# IoT4Bees-Ctrl_1V0.net
KiCad netlist of a schematic drawn in EAGLE
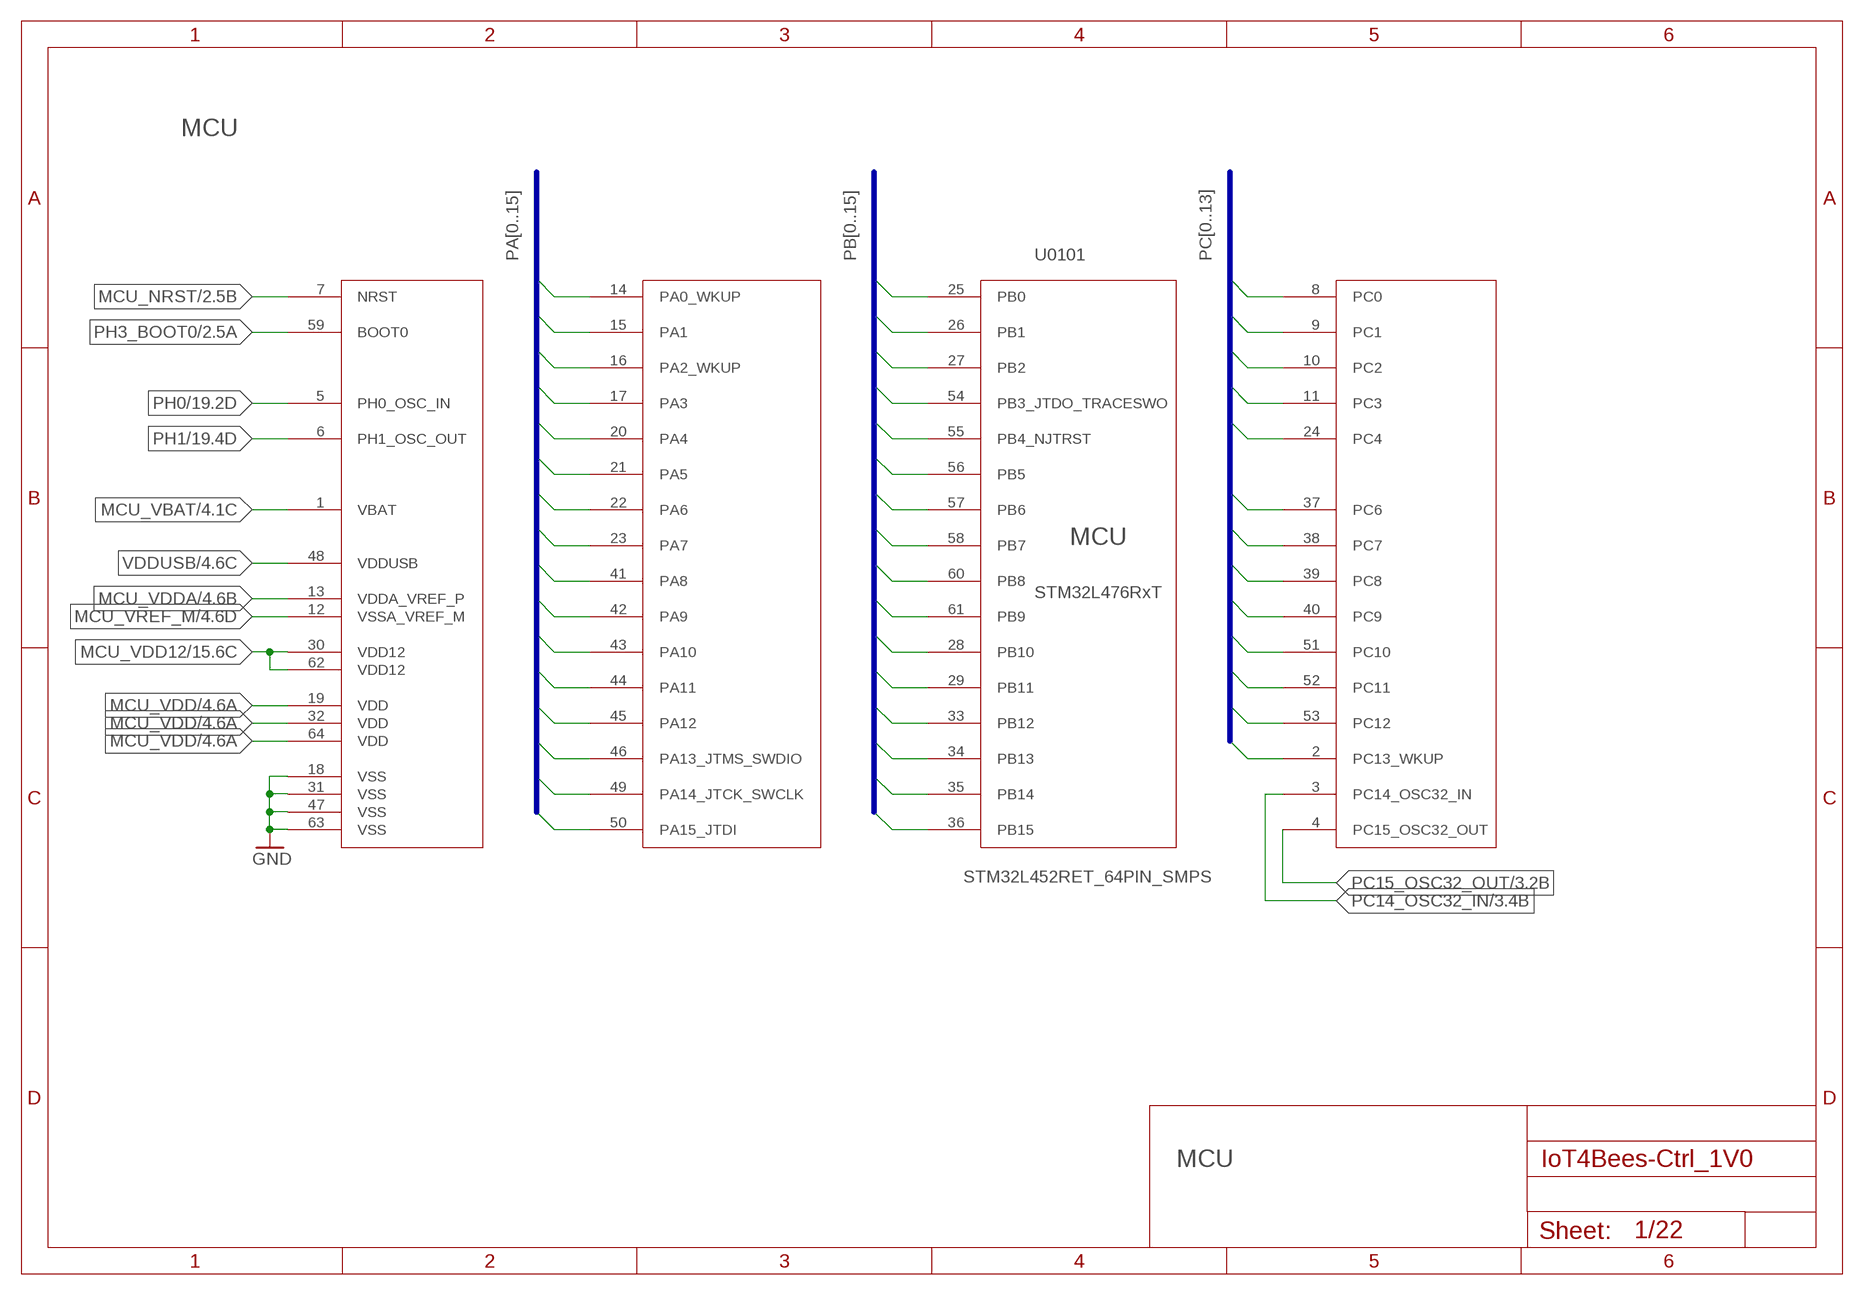
[diagram p0: schematic, sheet 1]
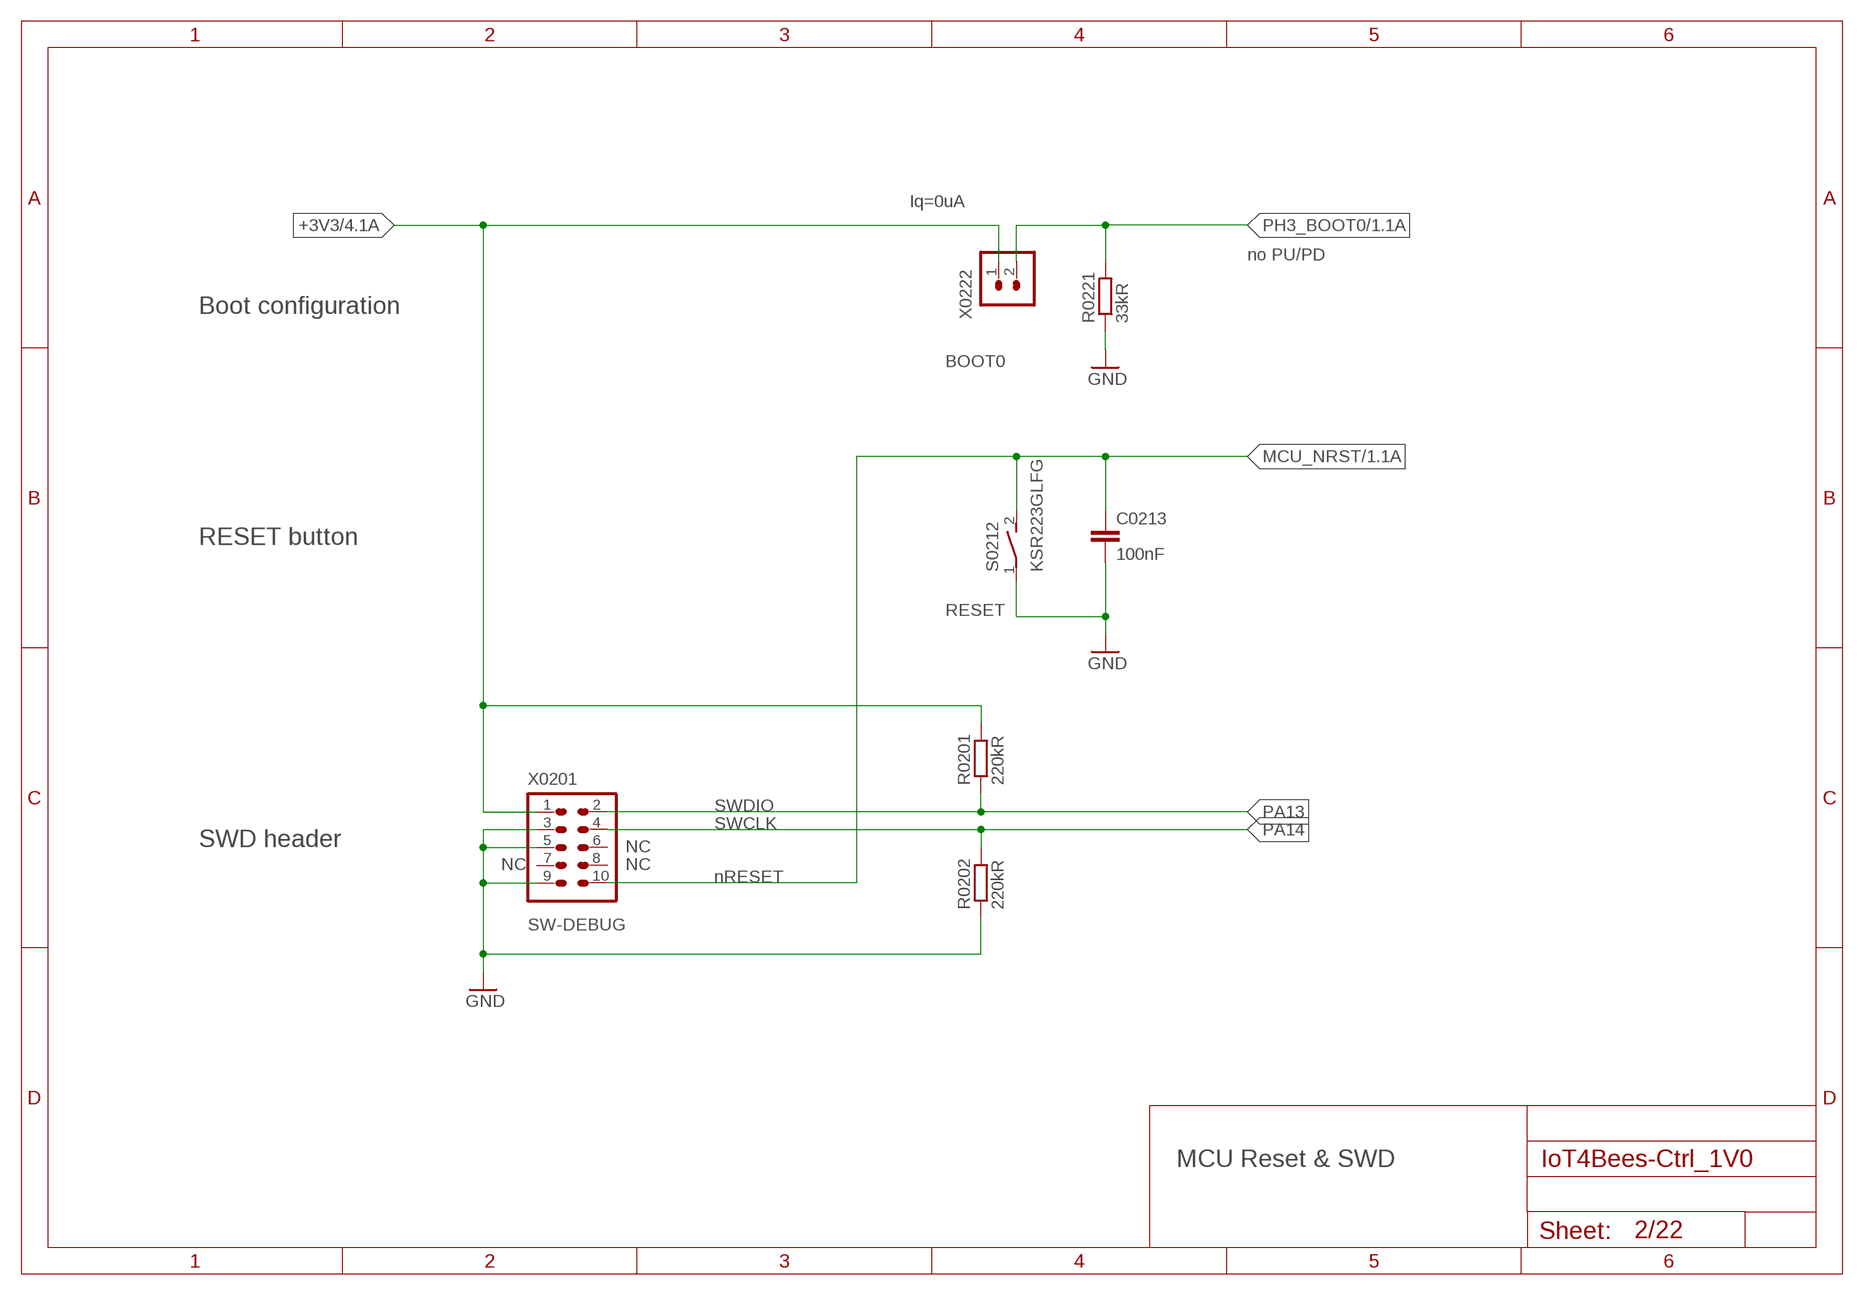
[diagram p1: schematic, sheet 2]
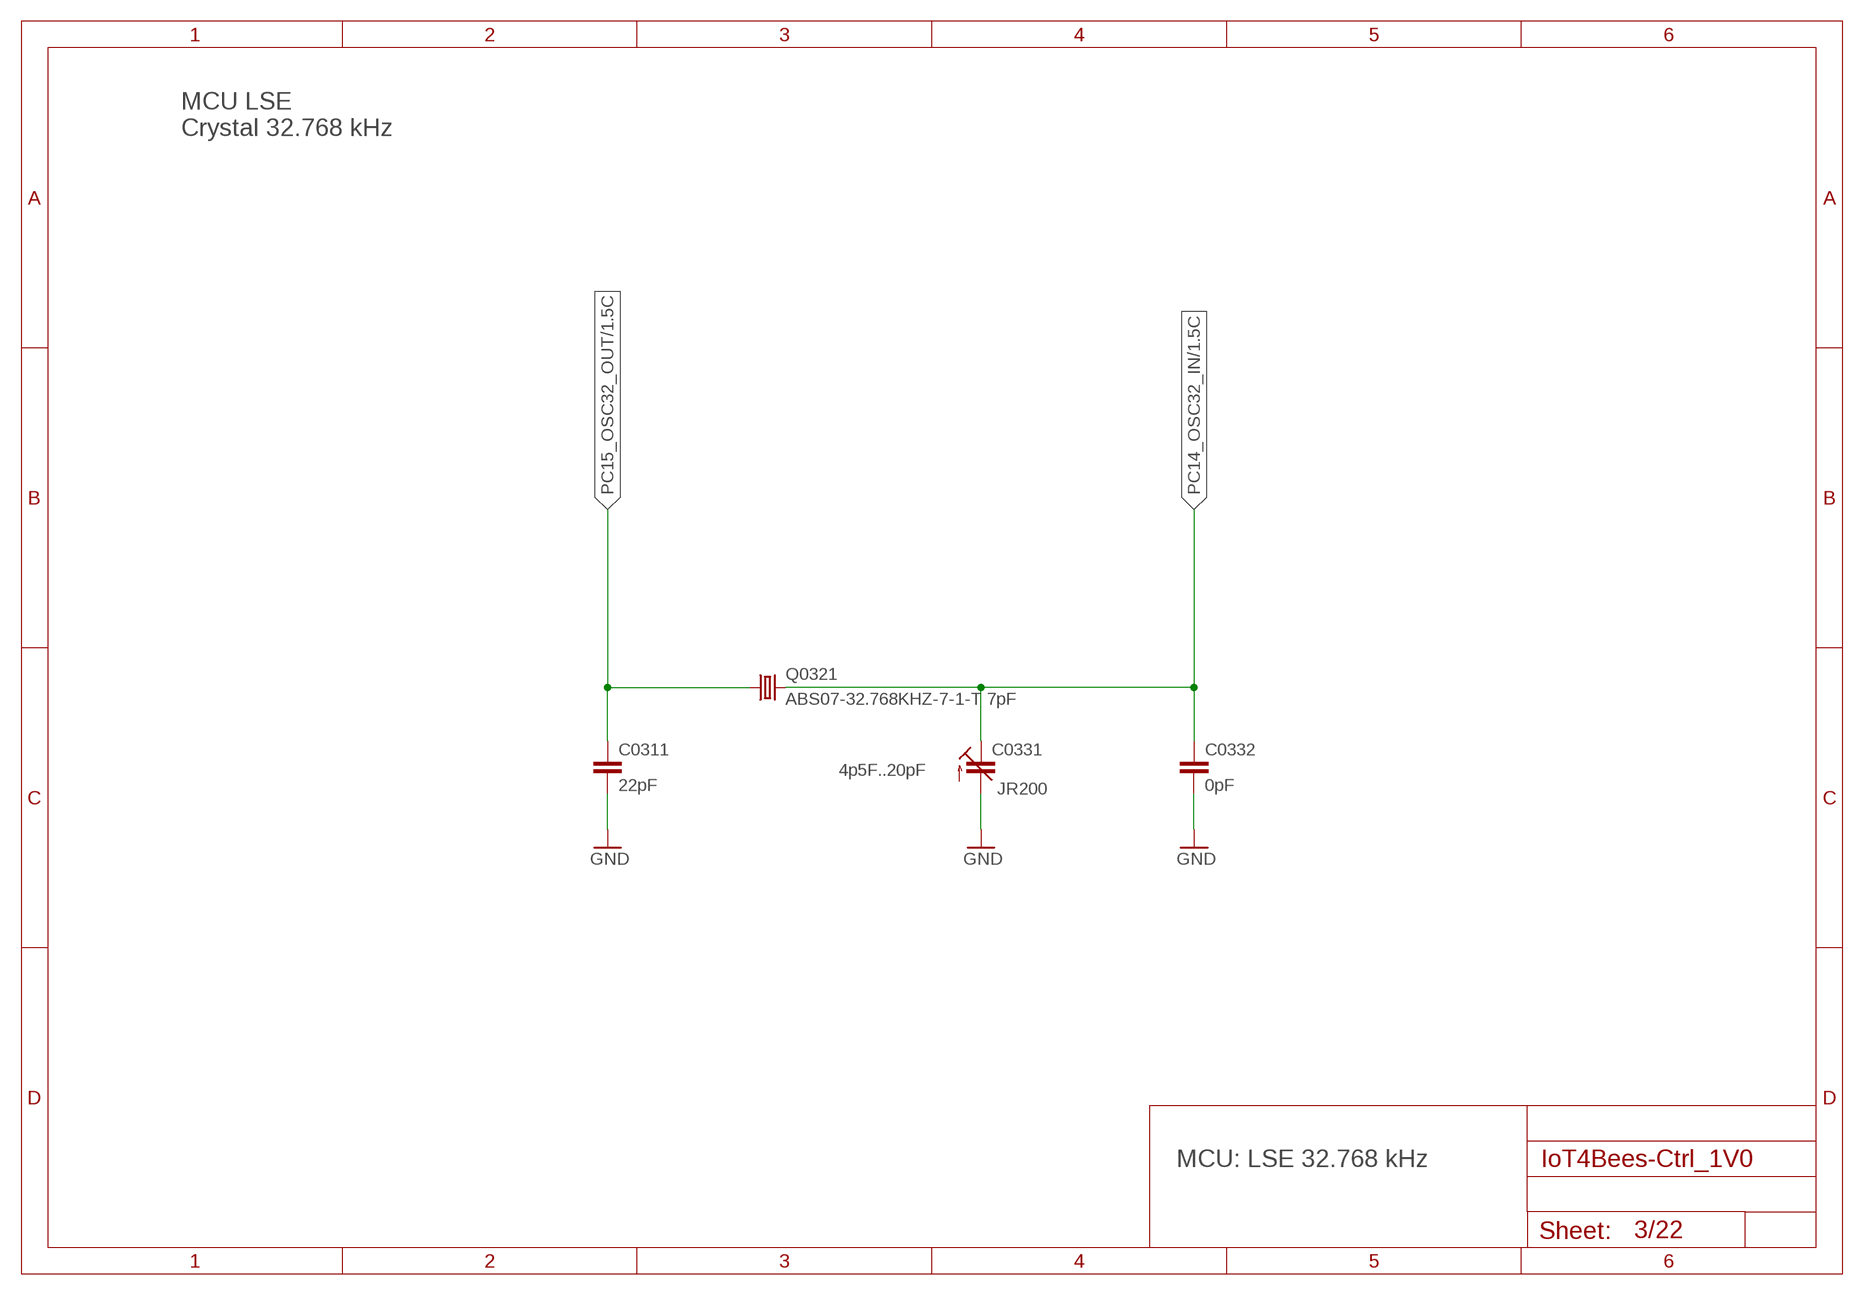
[diagram p2: schematic, sheet 3]
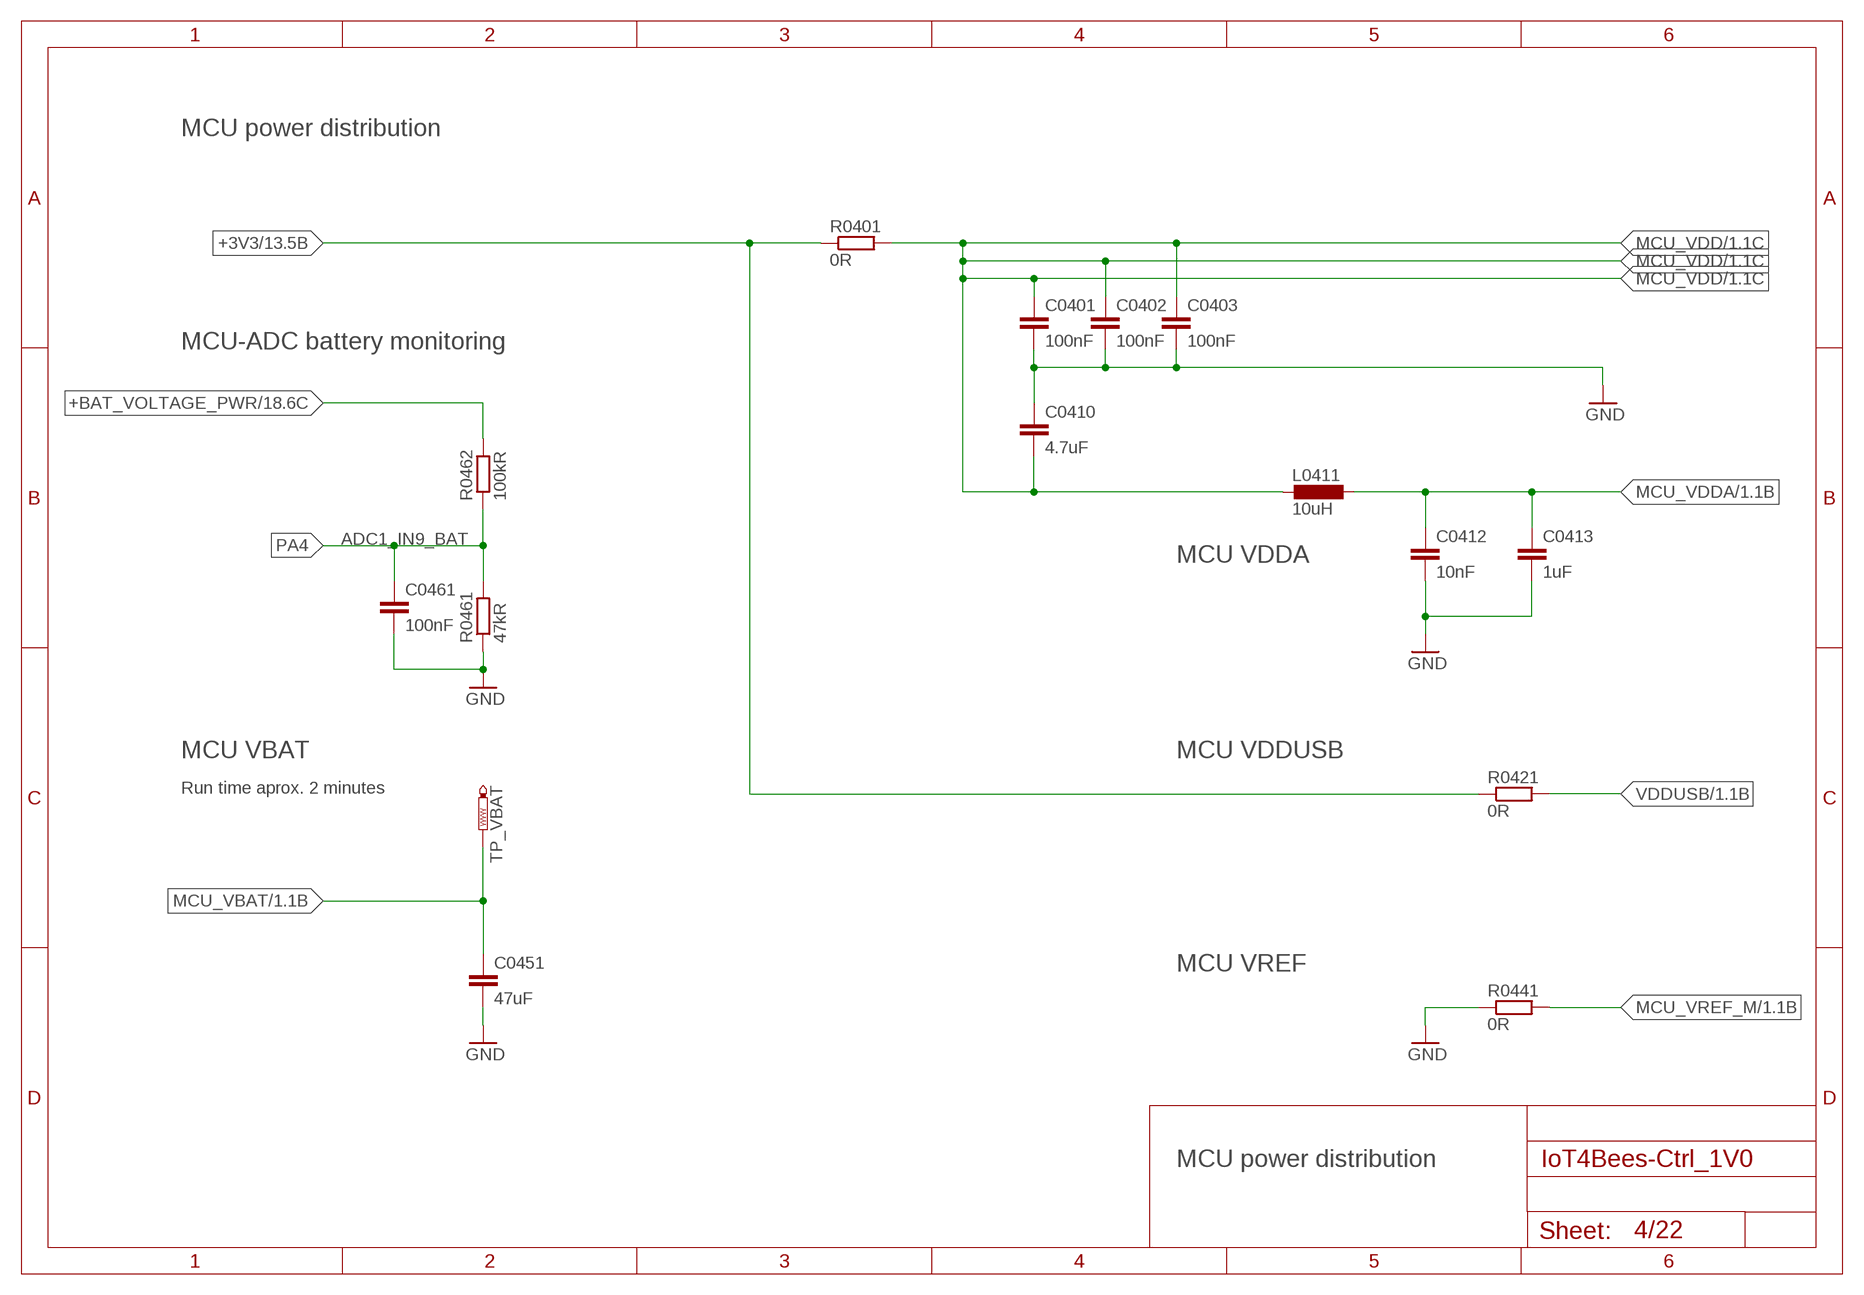
[diagram p3: schematic, sheet 4]
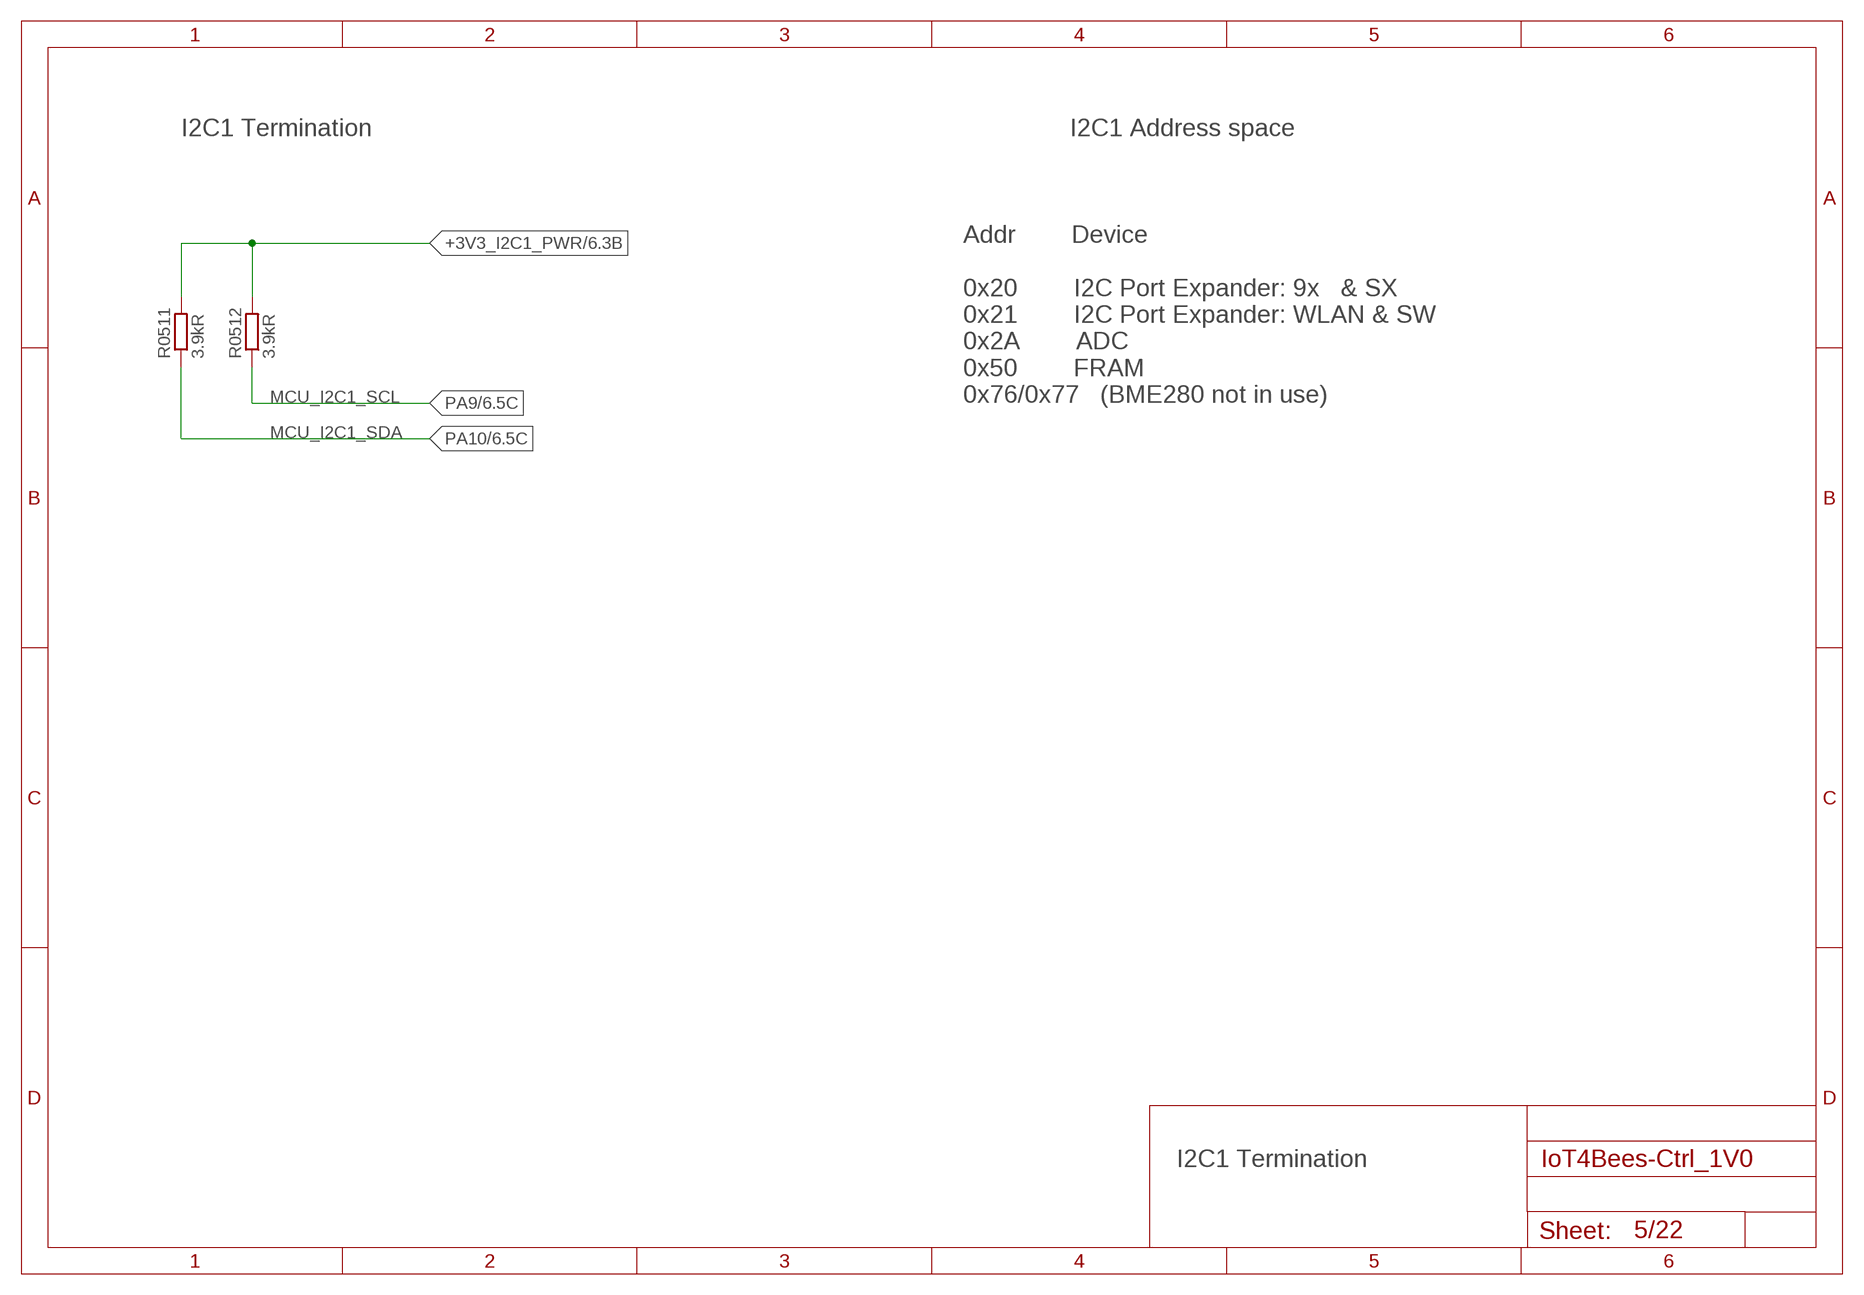
[diagram p4: schematic, sheet 5]
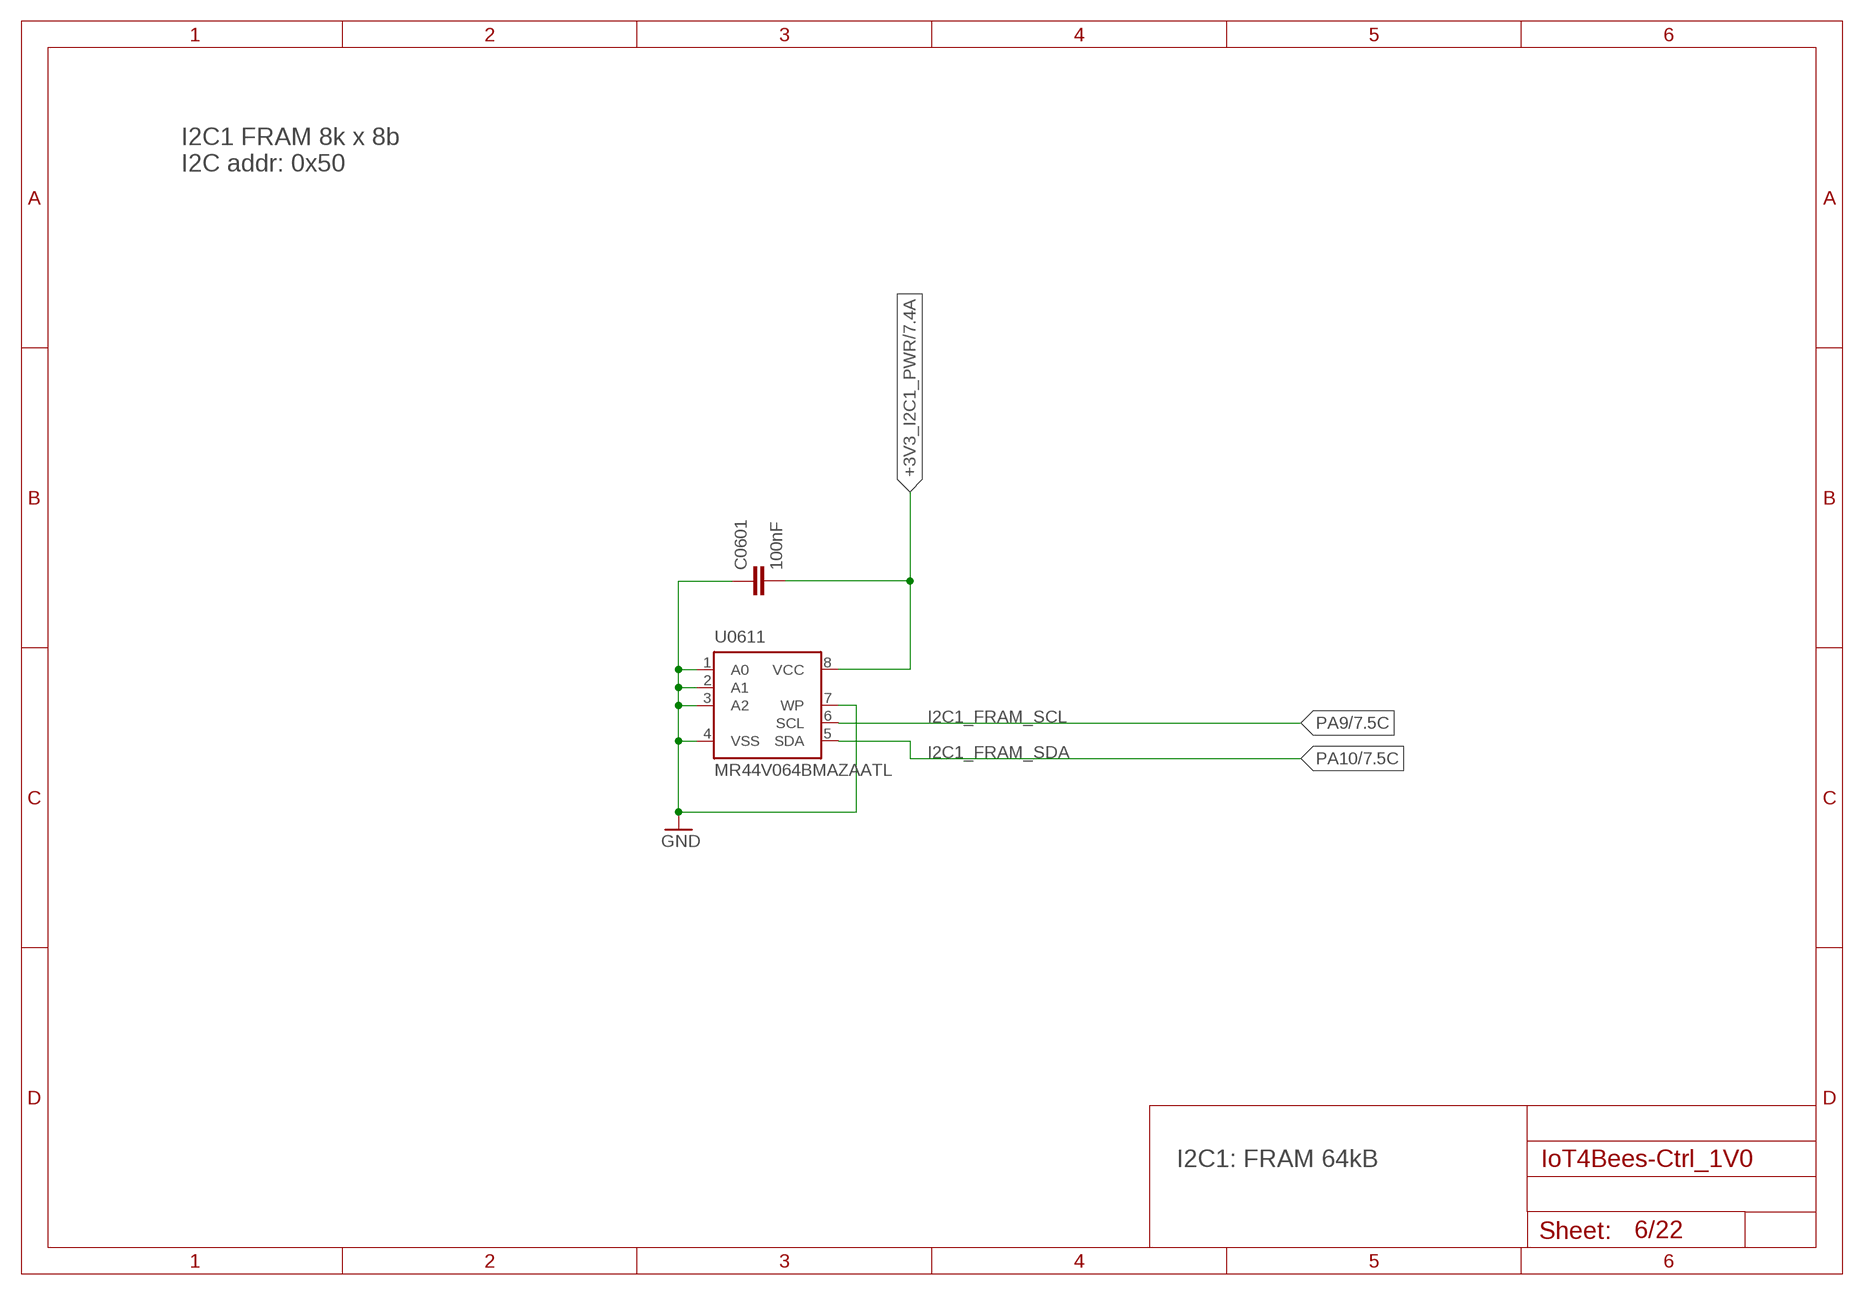
[diagram p5: schematic, sheet 6]
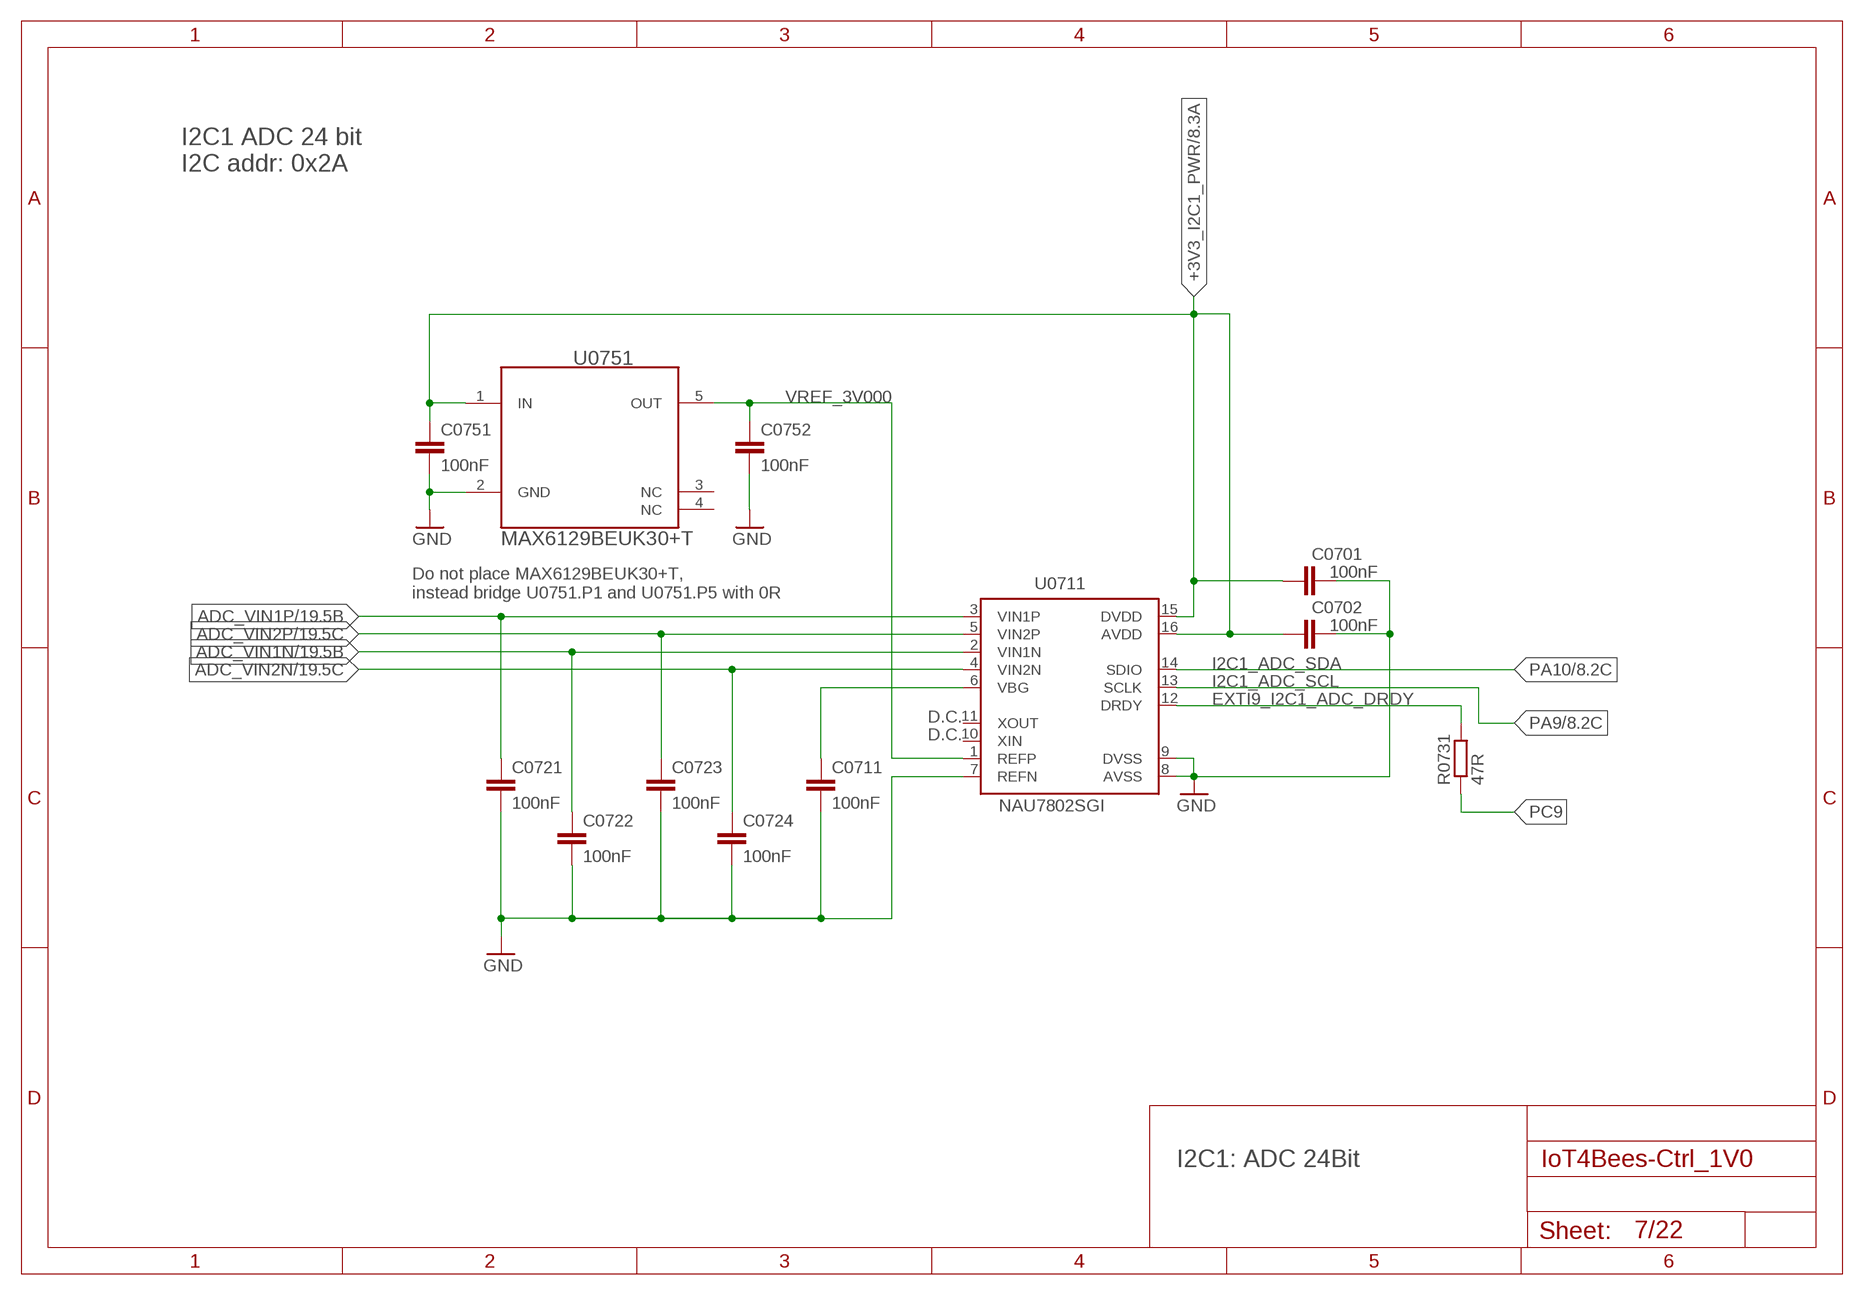
[diagram p6: schematic, sheet 7]
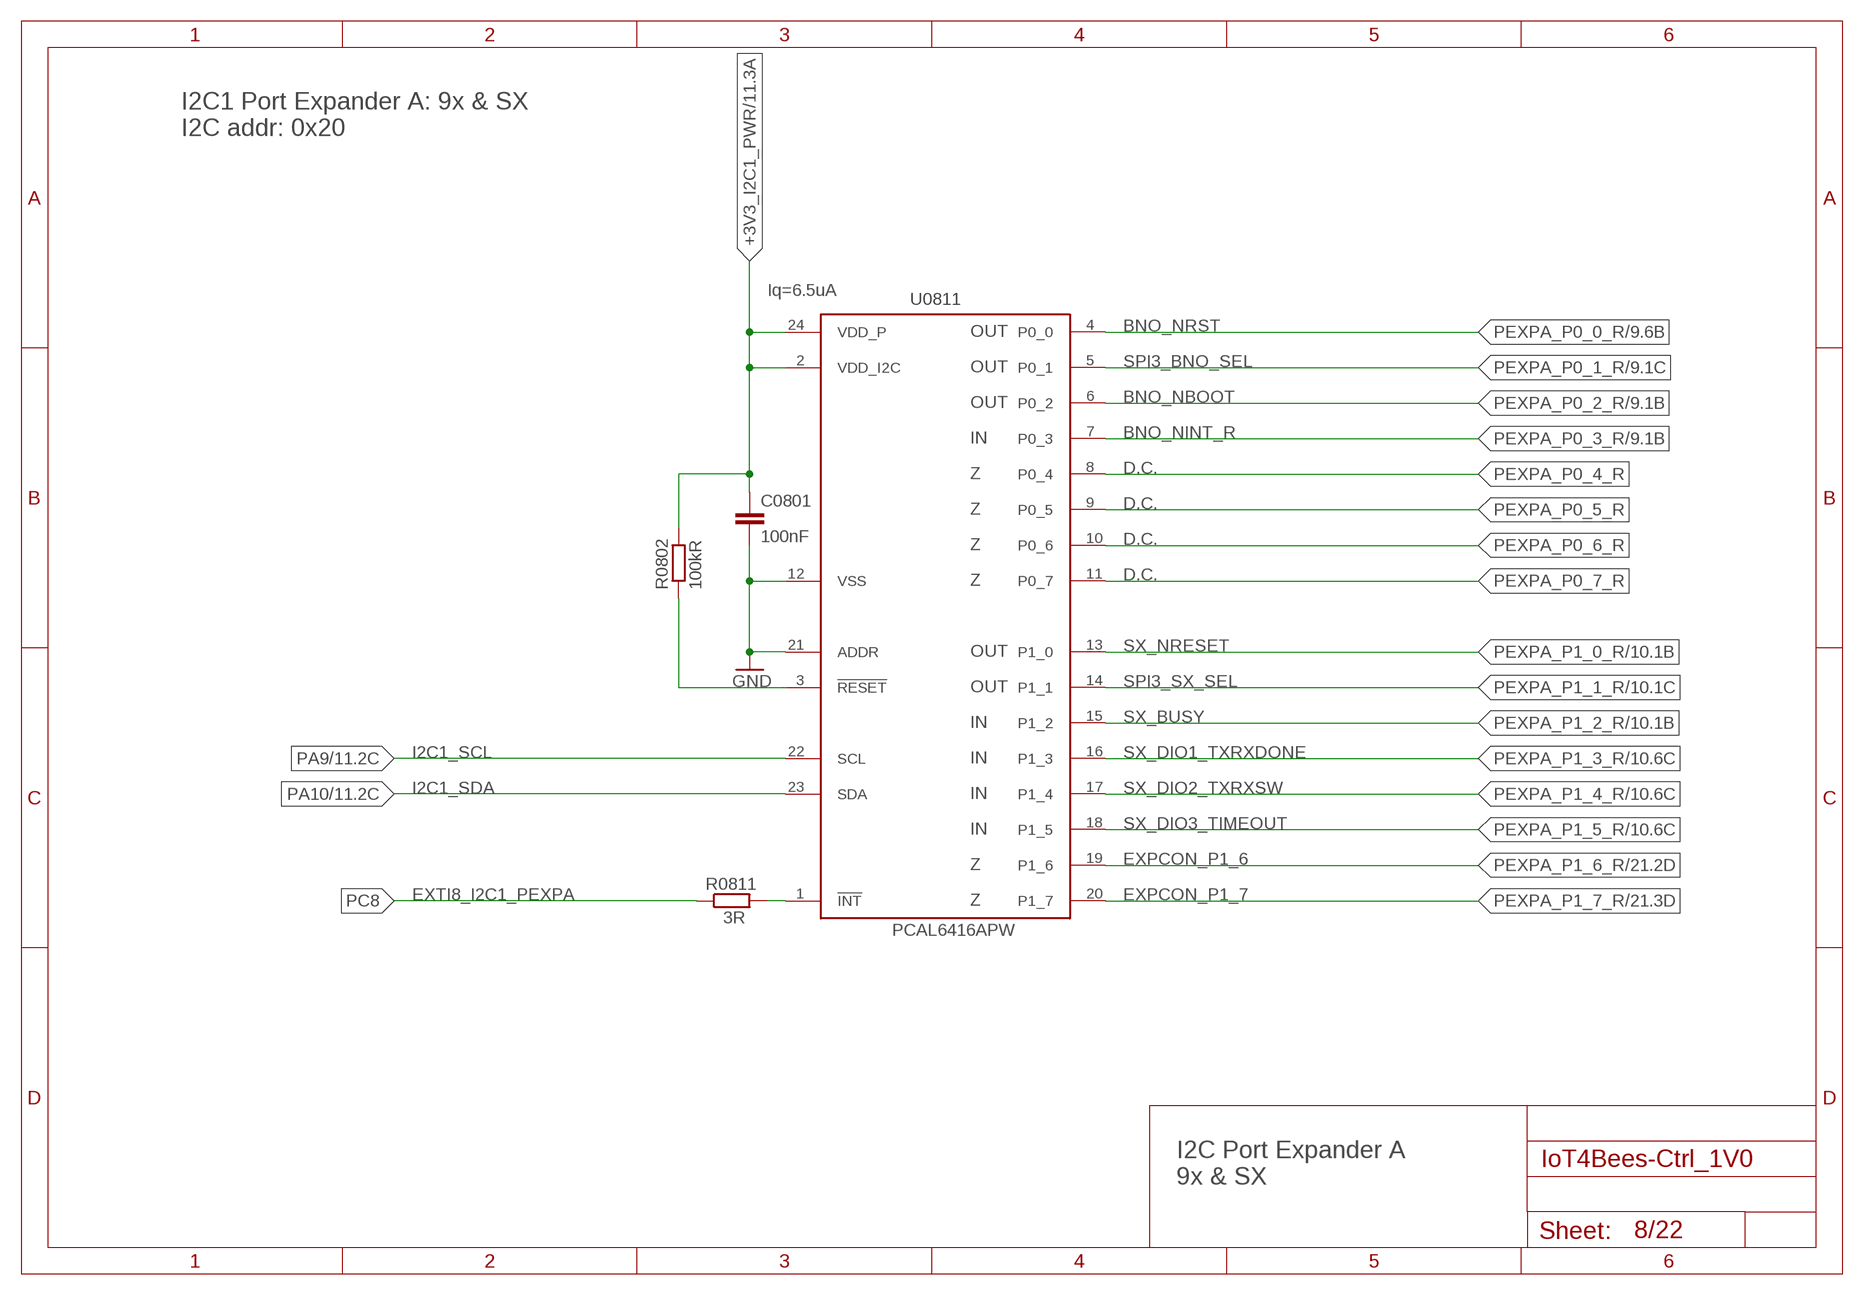
[diagram p7: schematic, sheet 8]
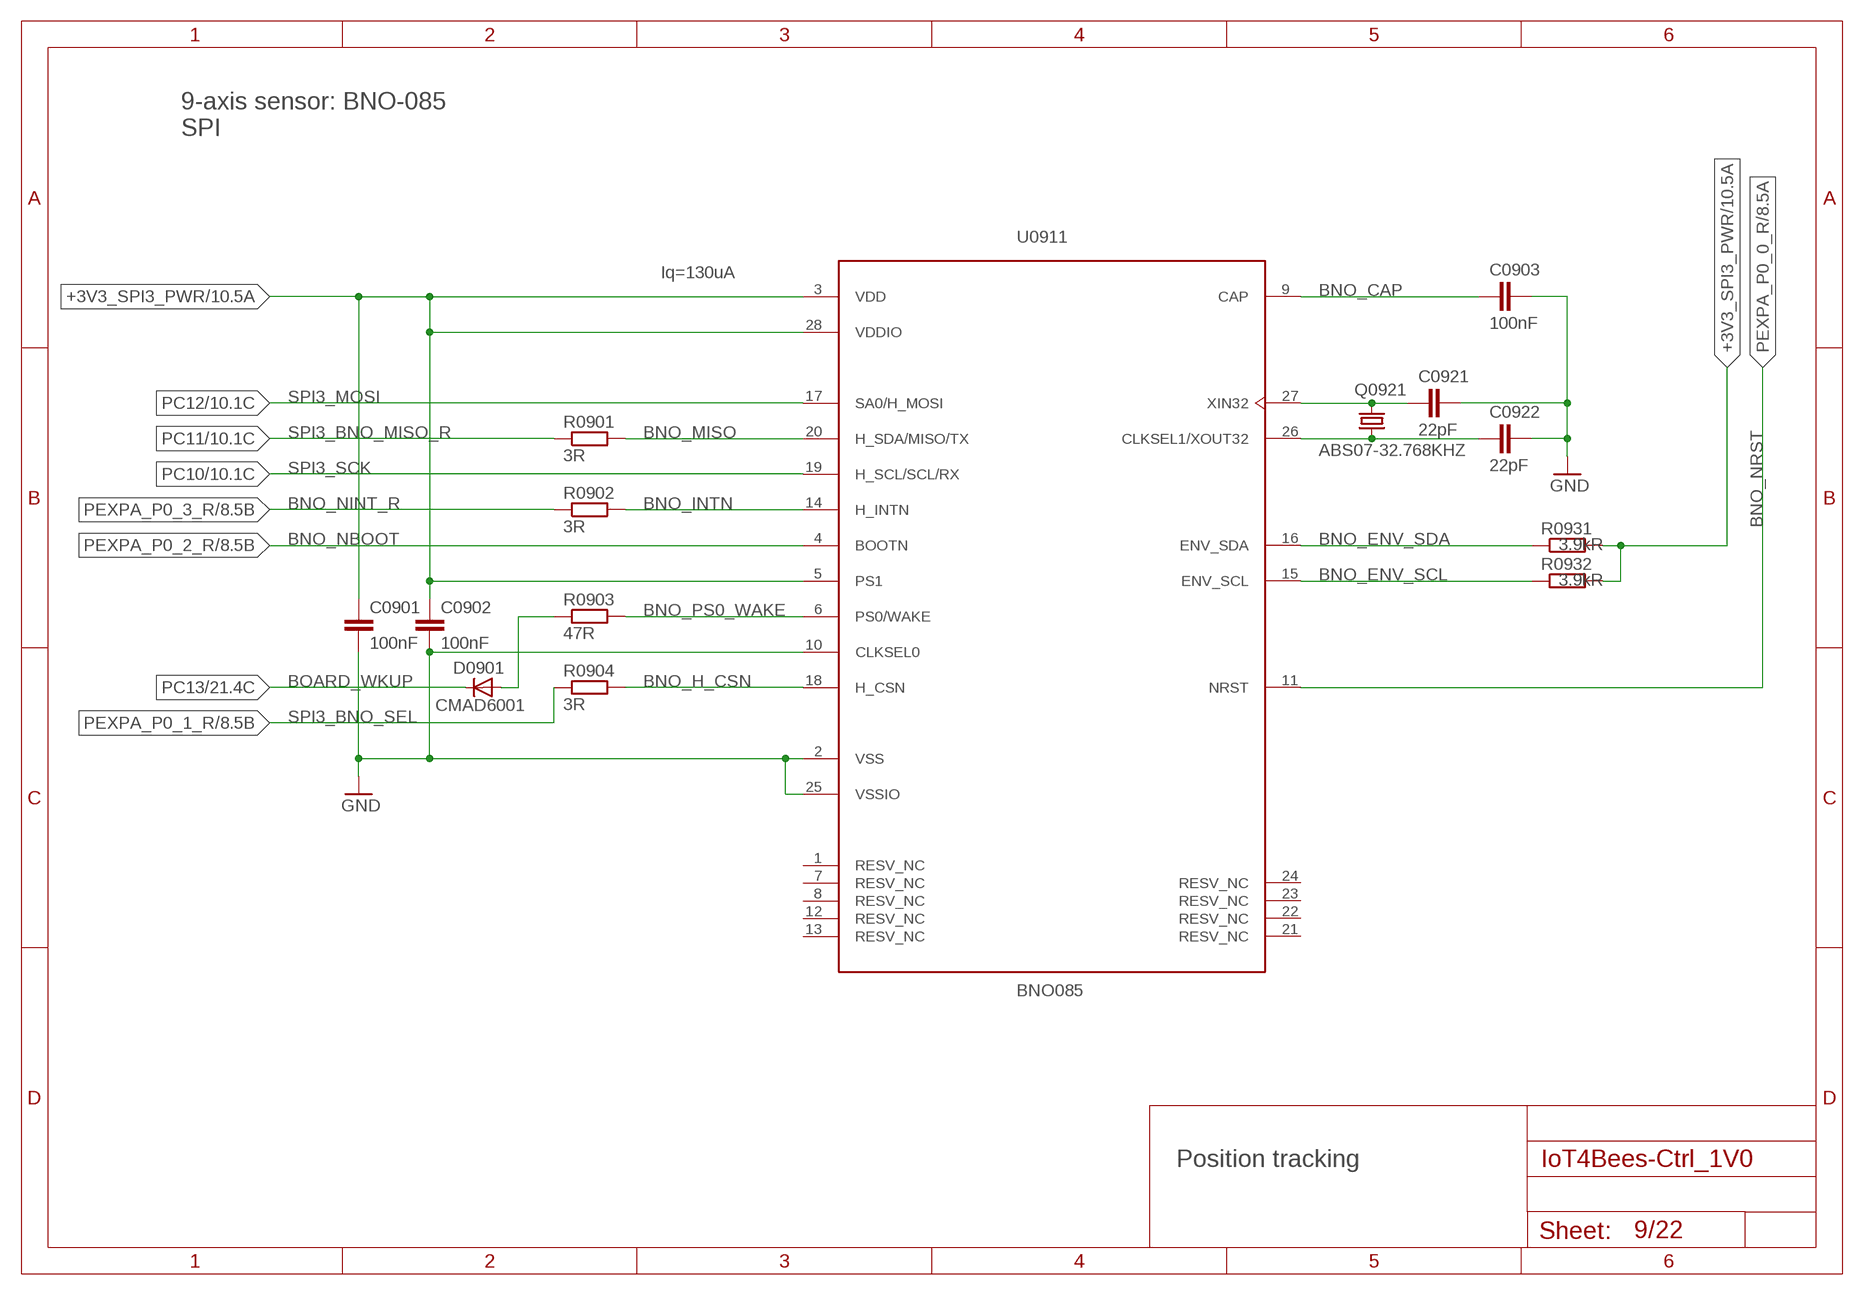
[diagram p8: schematic, sheet 9]
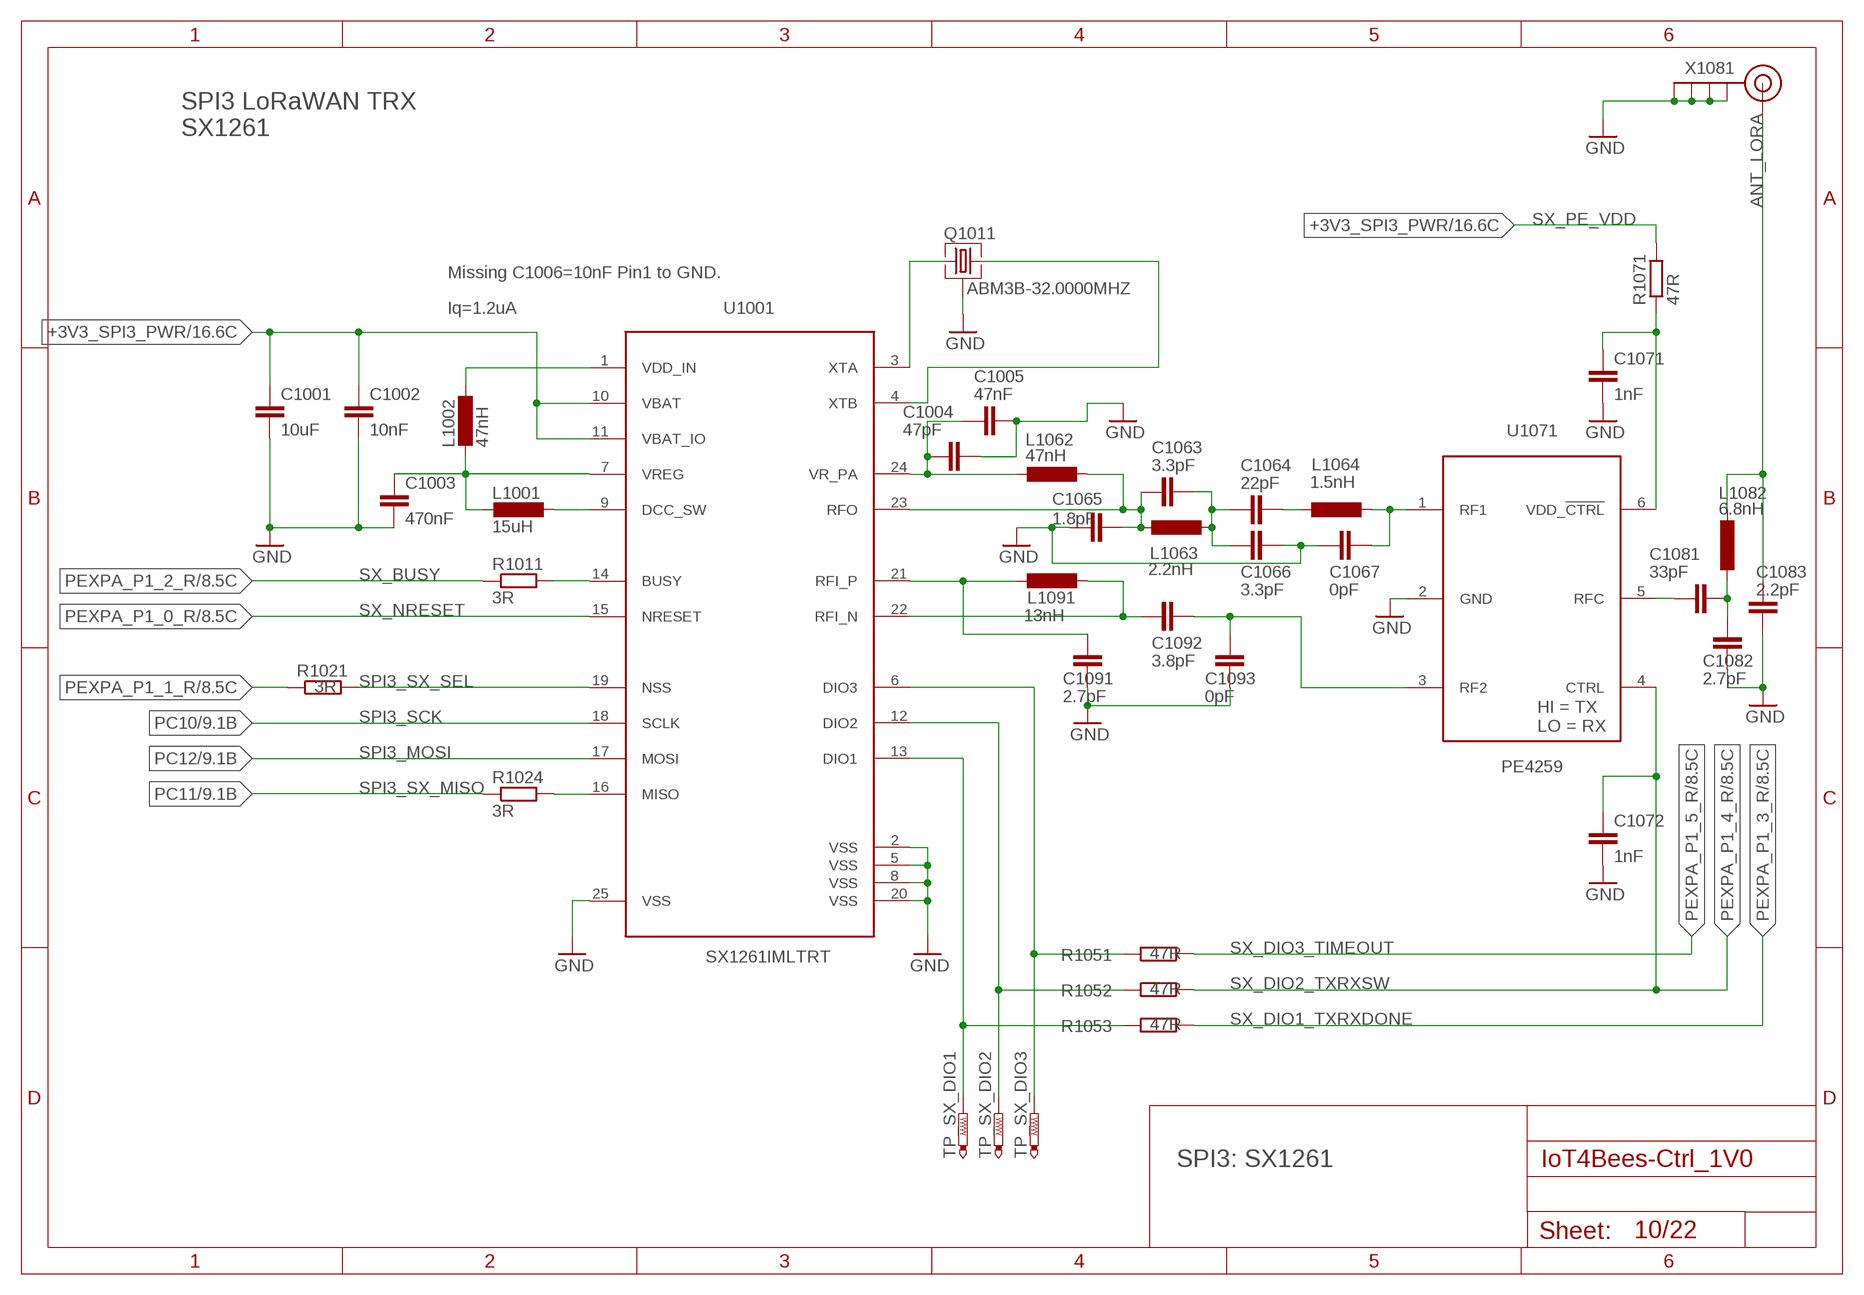
[diagram p9: schematic, sheet 10]
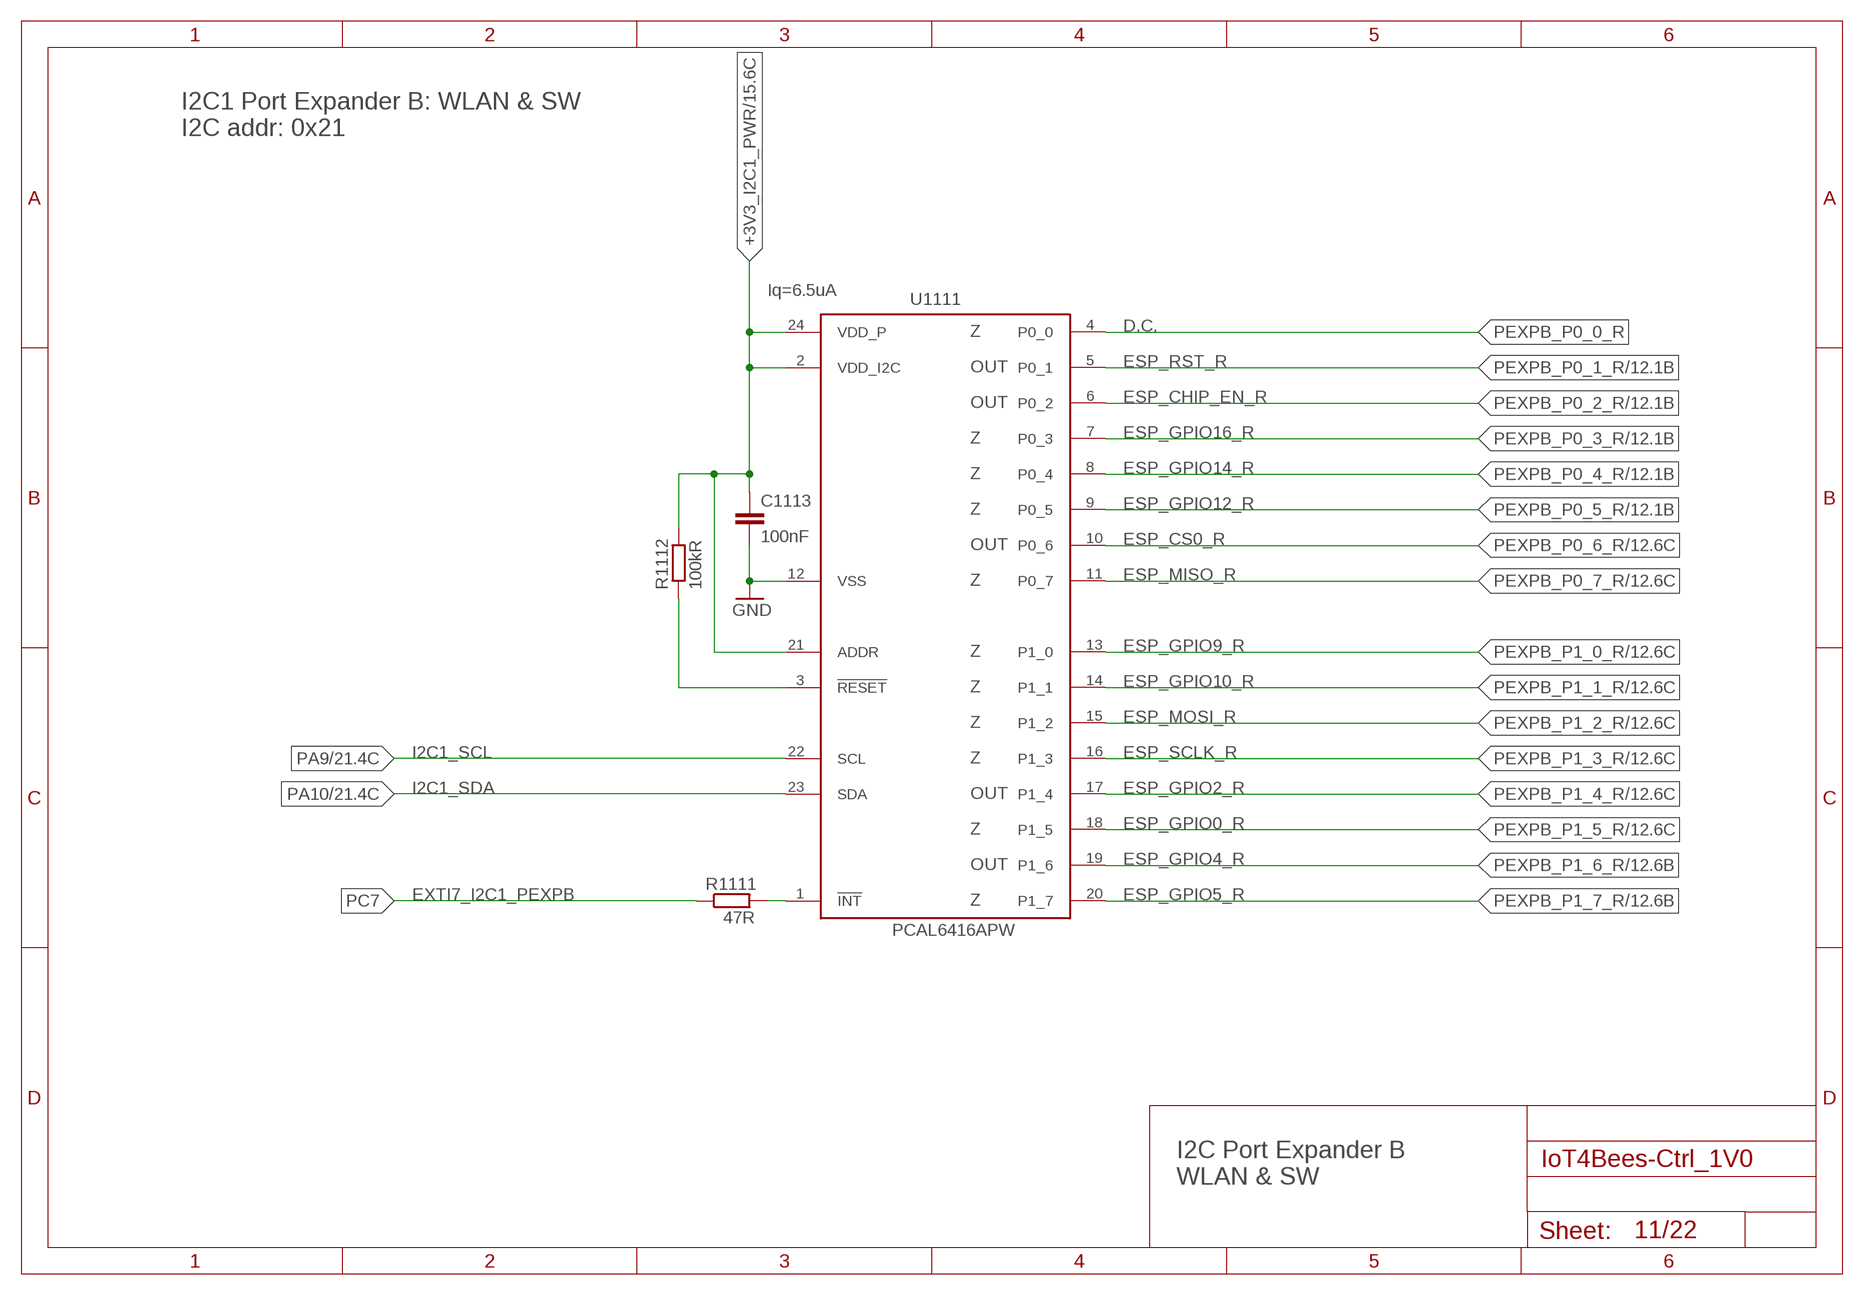
[diagram p10: schematic, sheet 11]
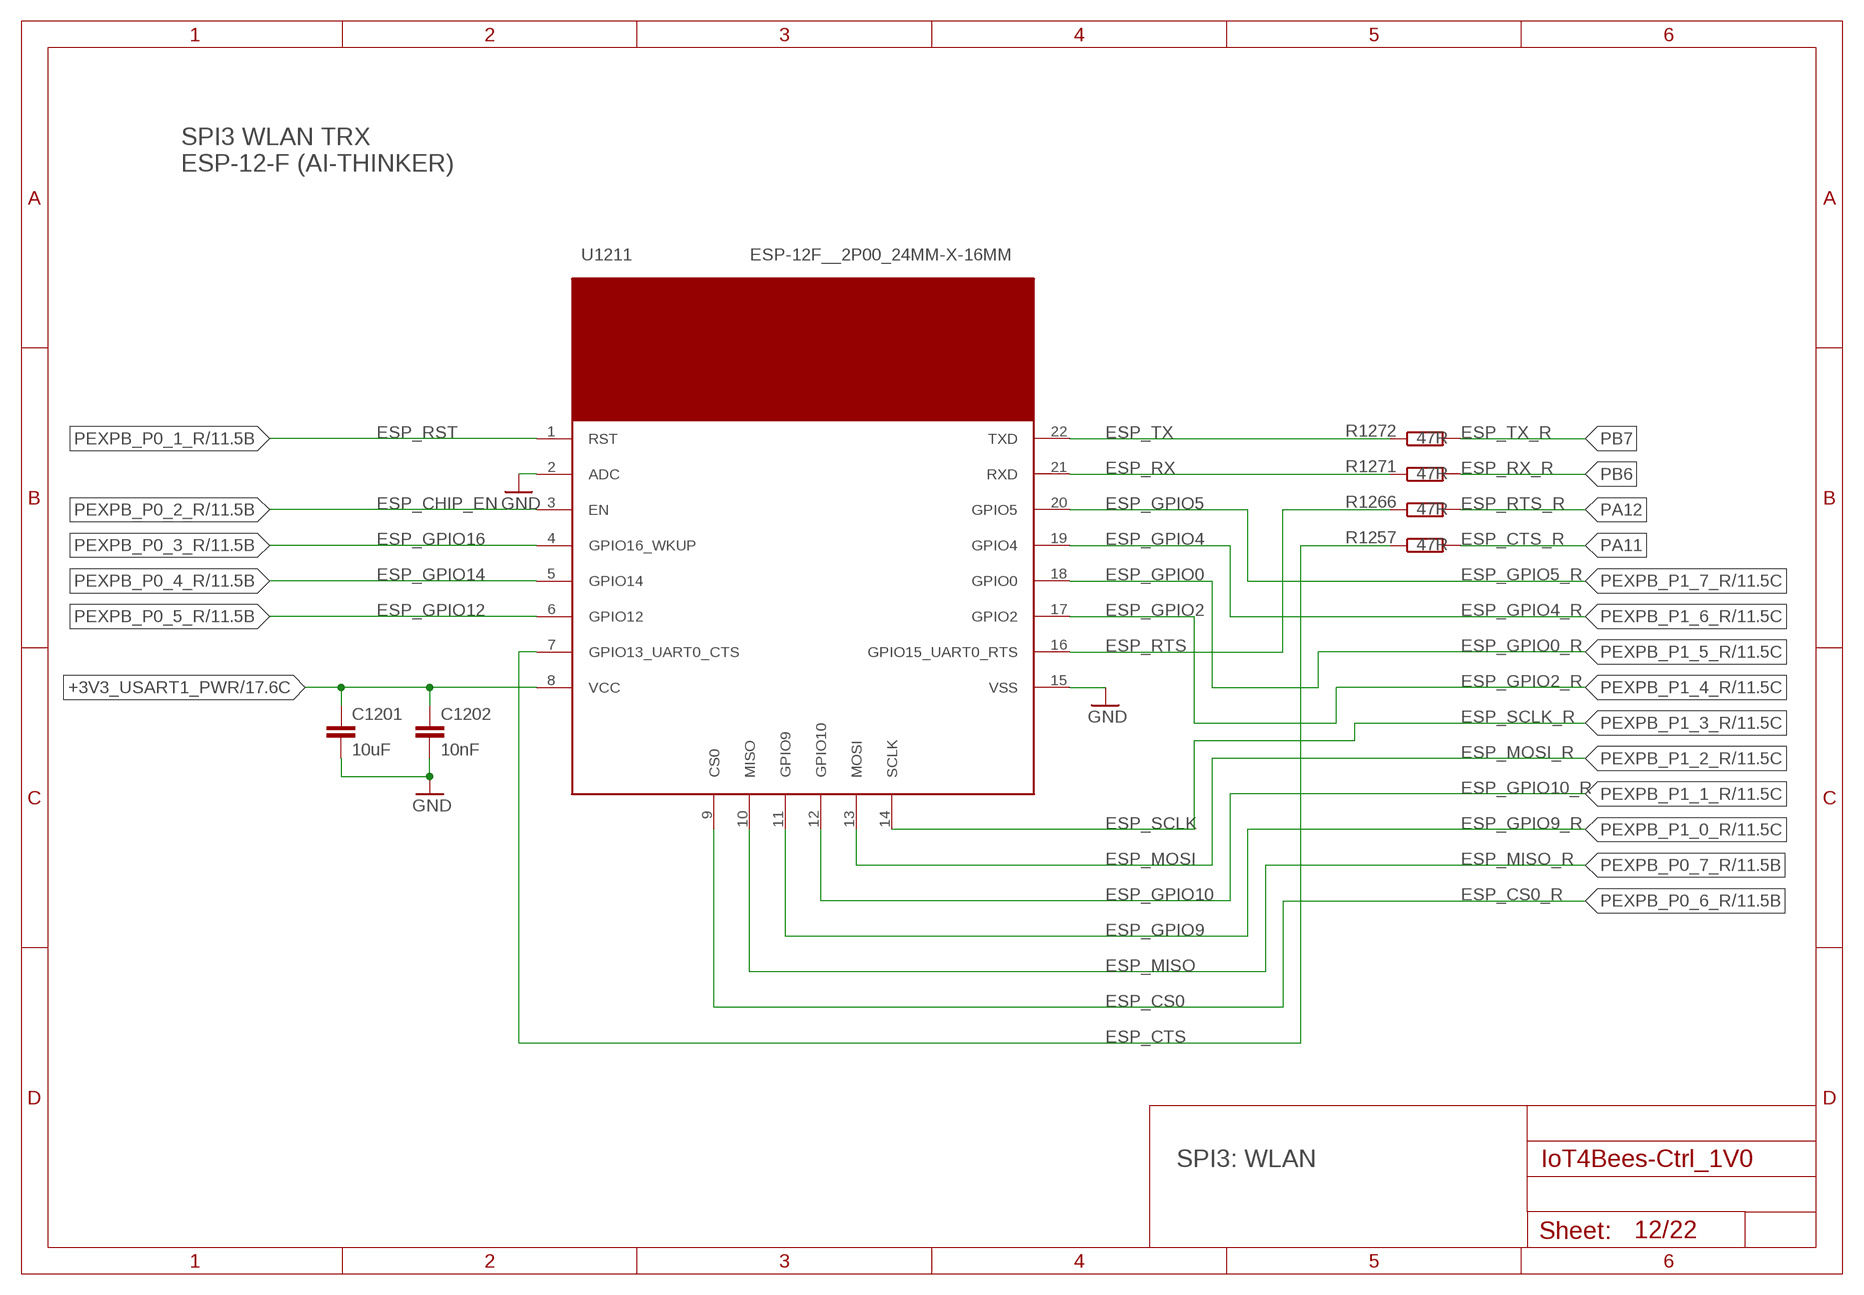
[diagram p11: schematic, sheet 12]
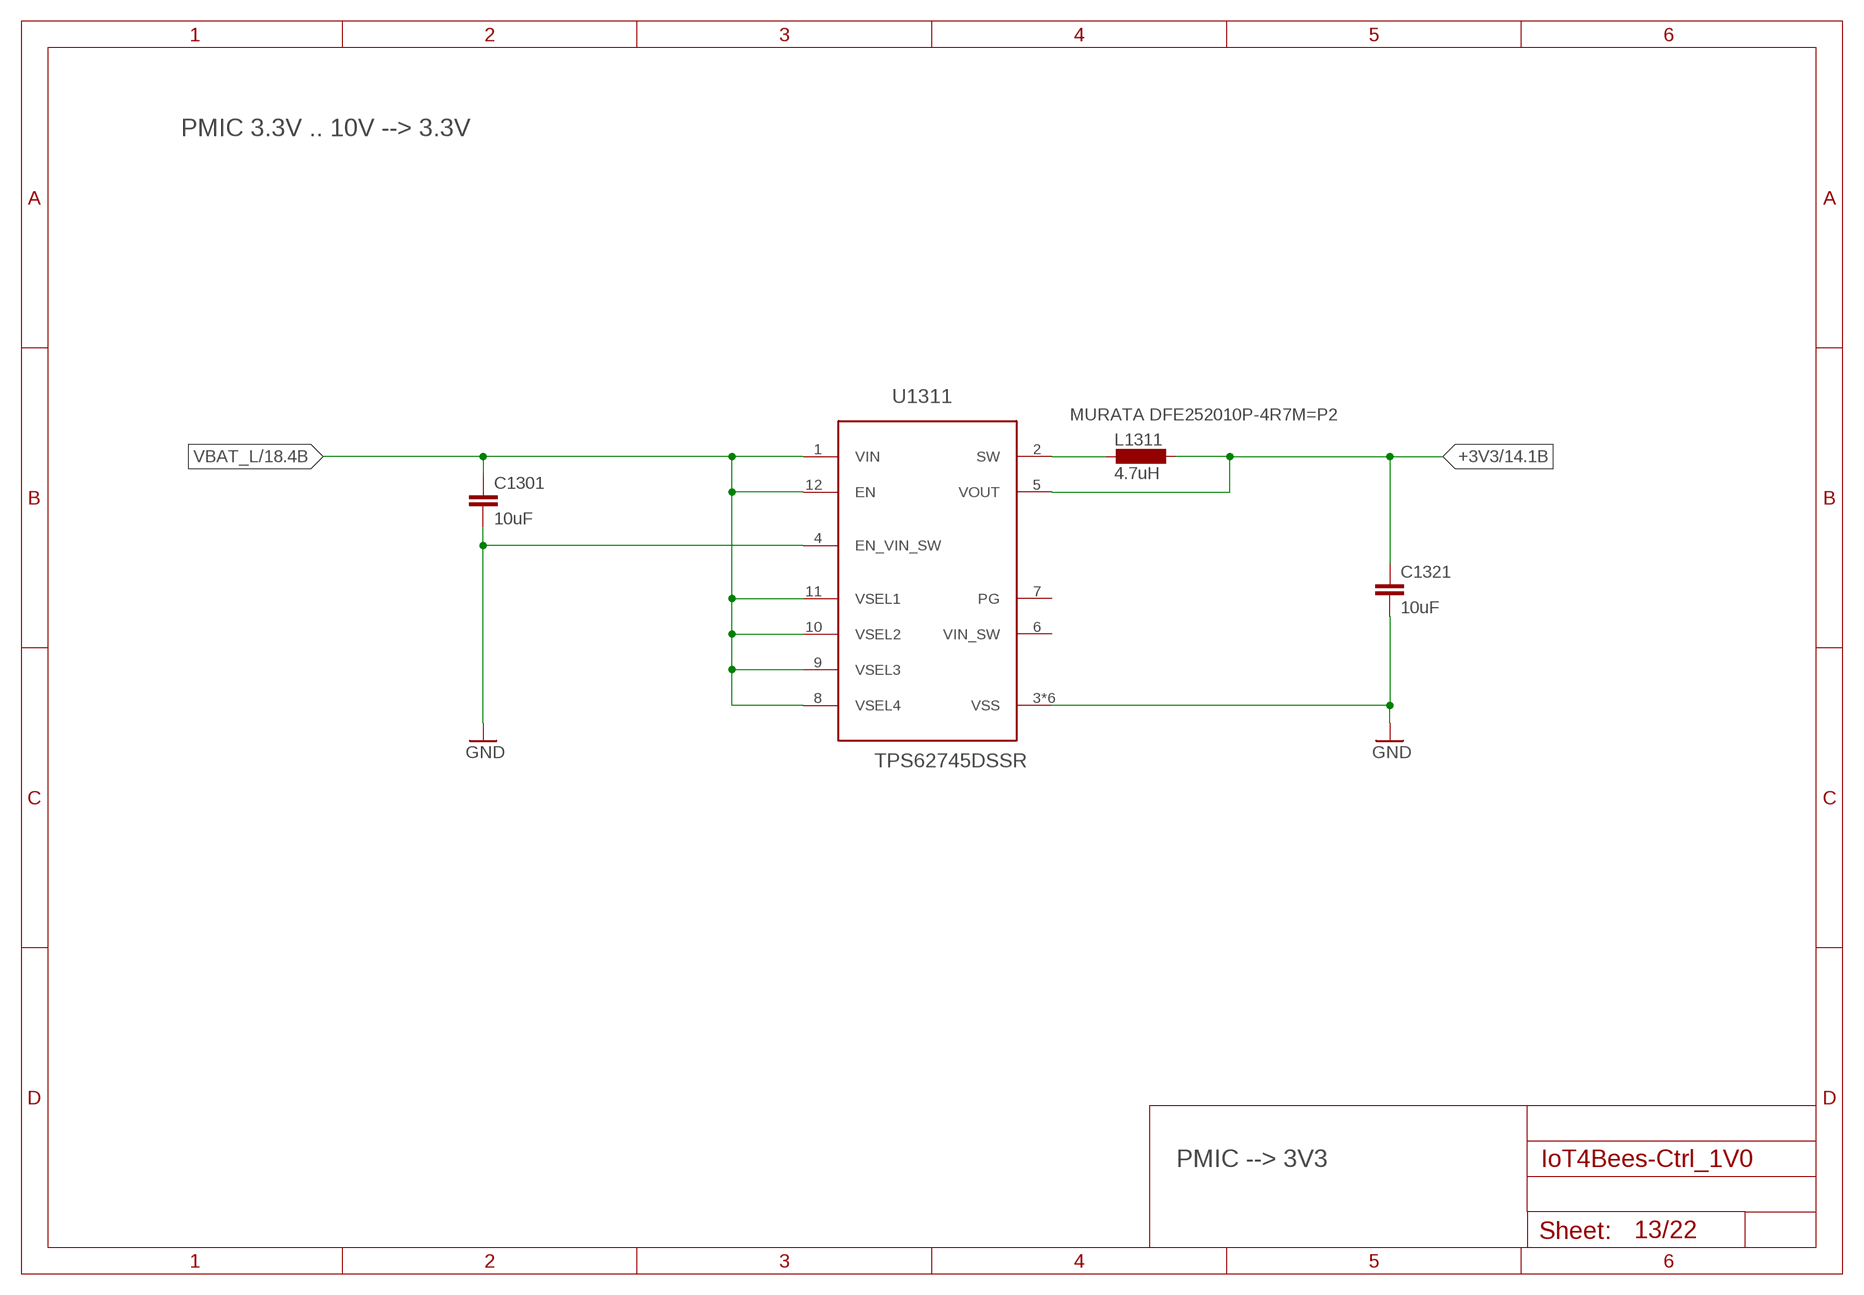
[diagram p12: schematic, sheet 13]
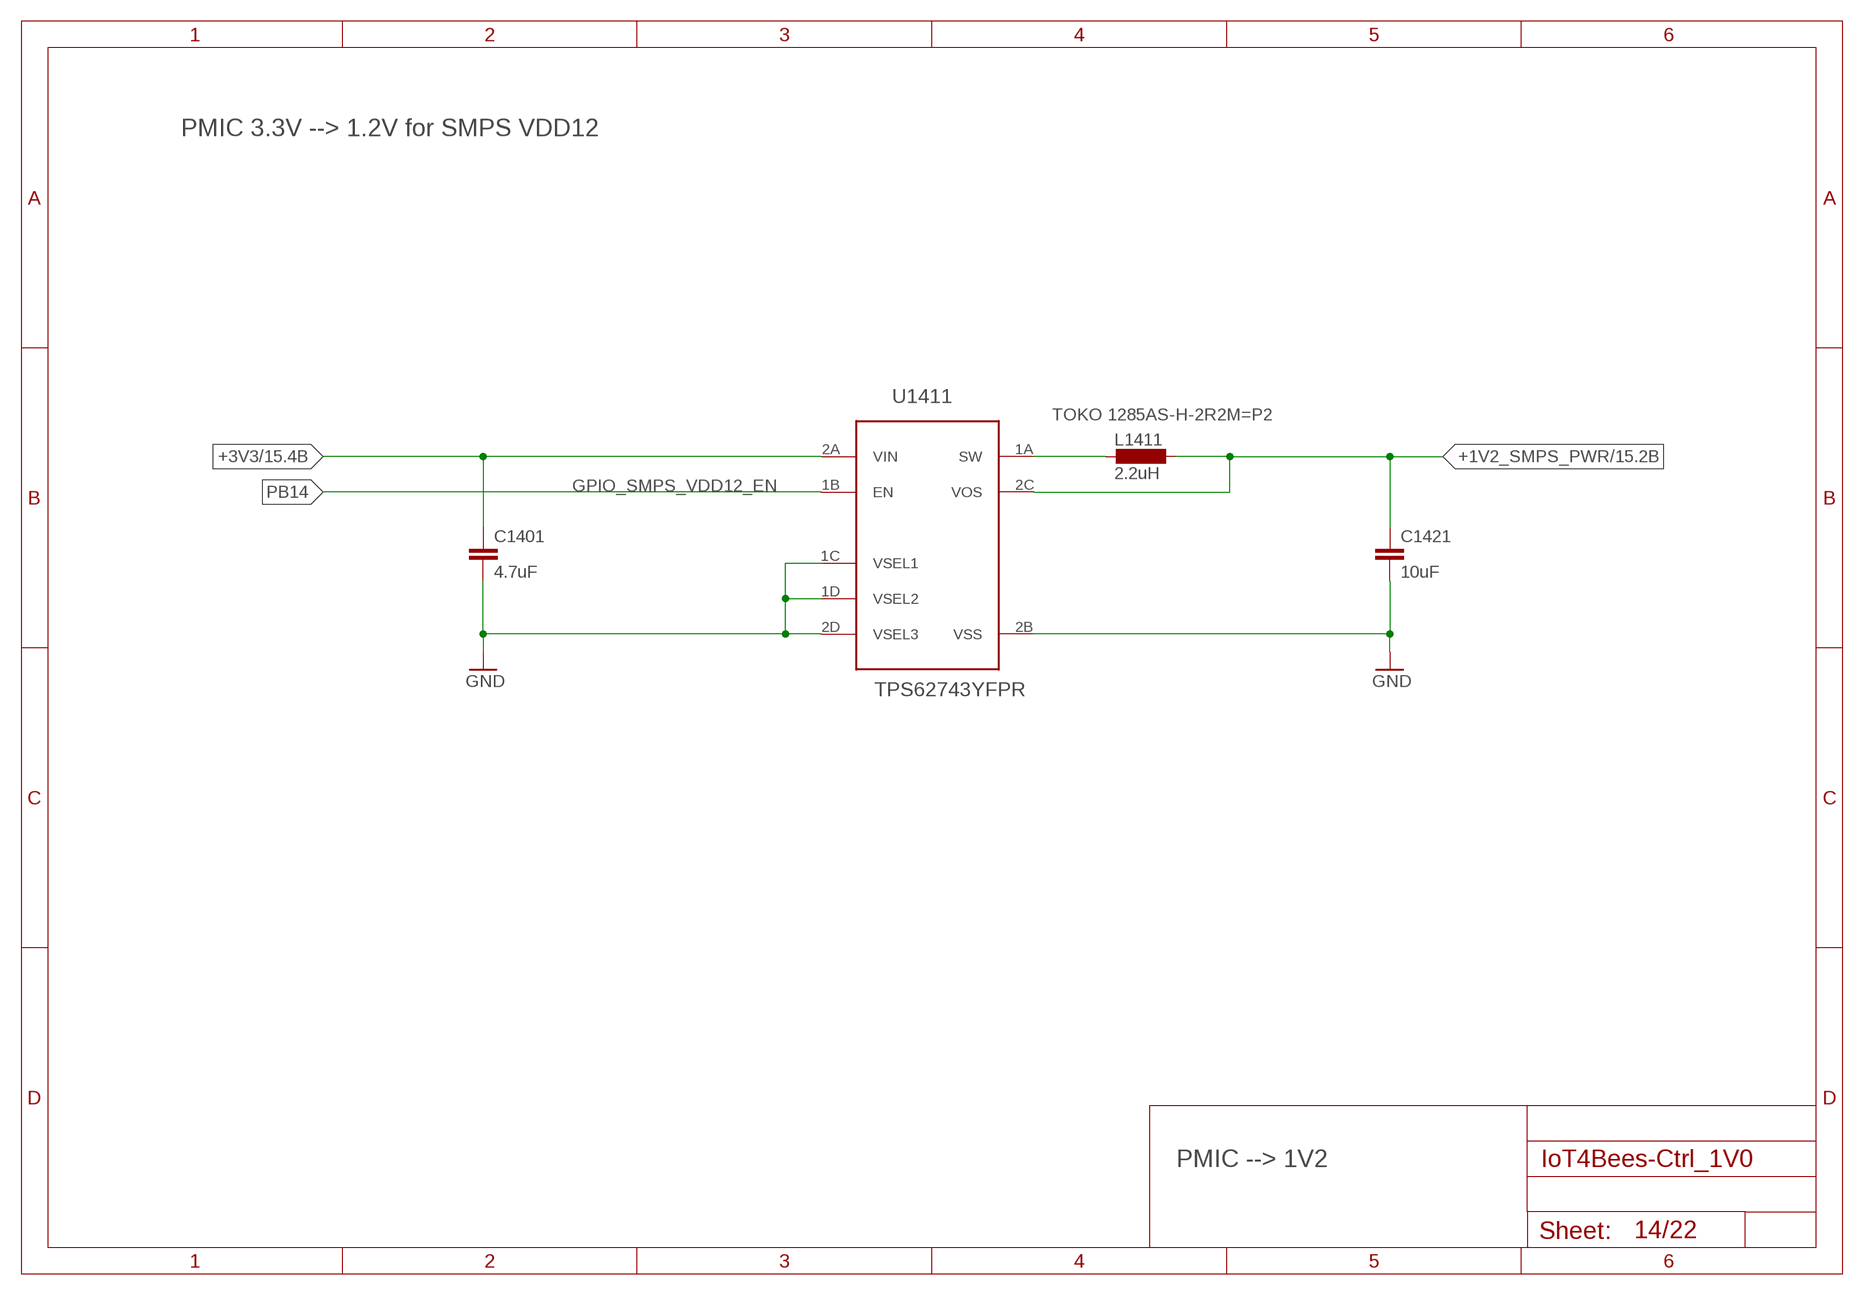
[diagram p13: schematic, sheet 14]
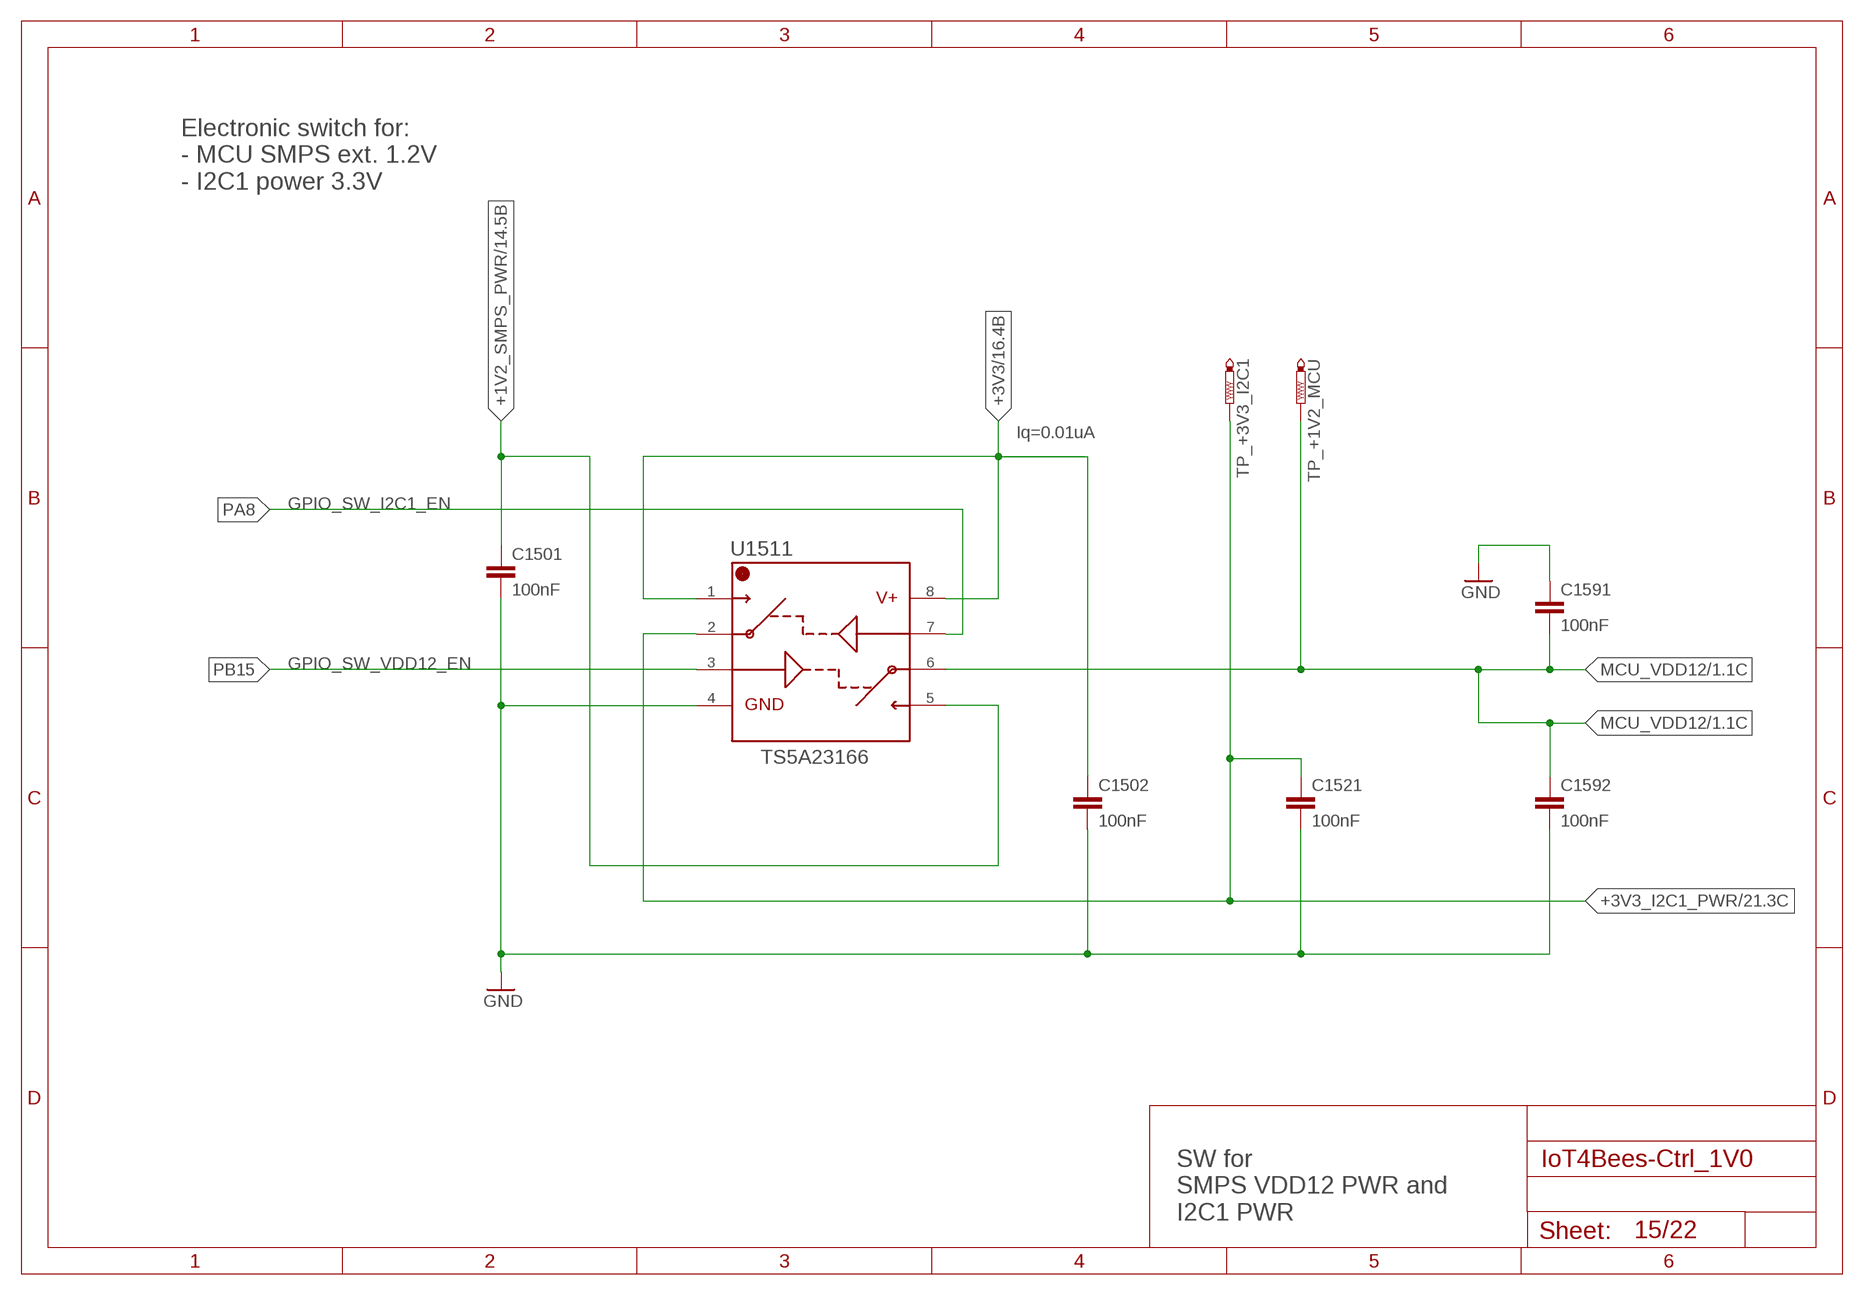
[diagram p14: schematic, sheet 15]
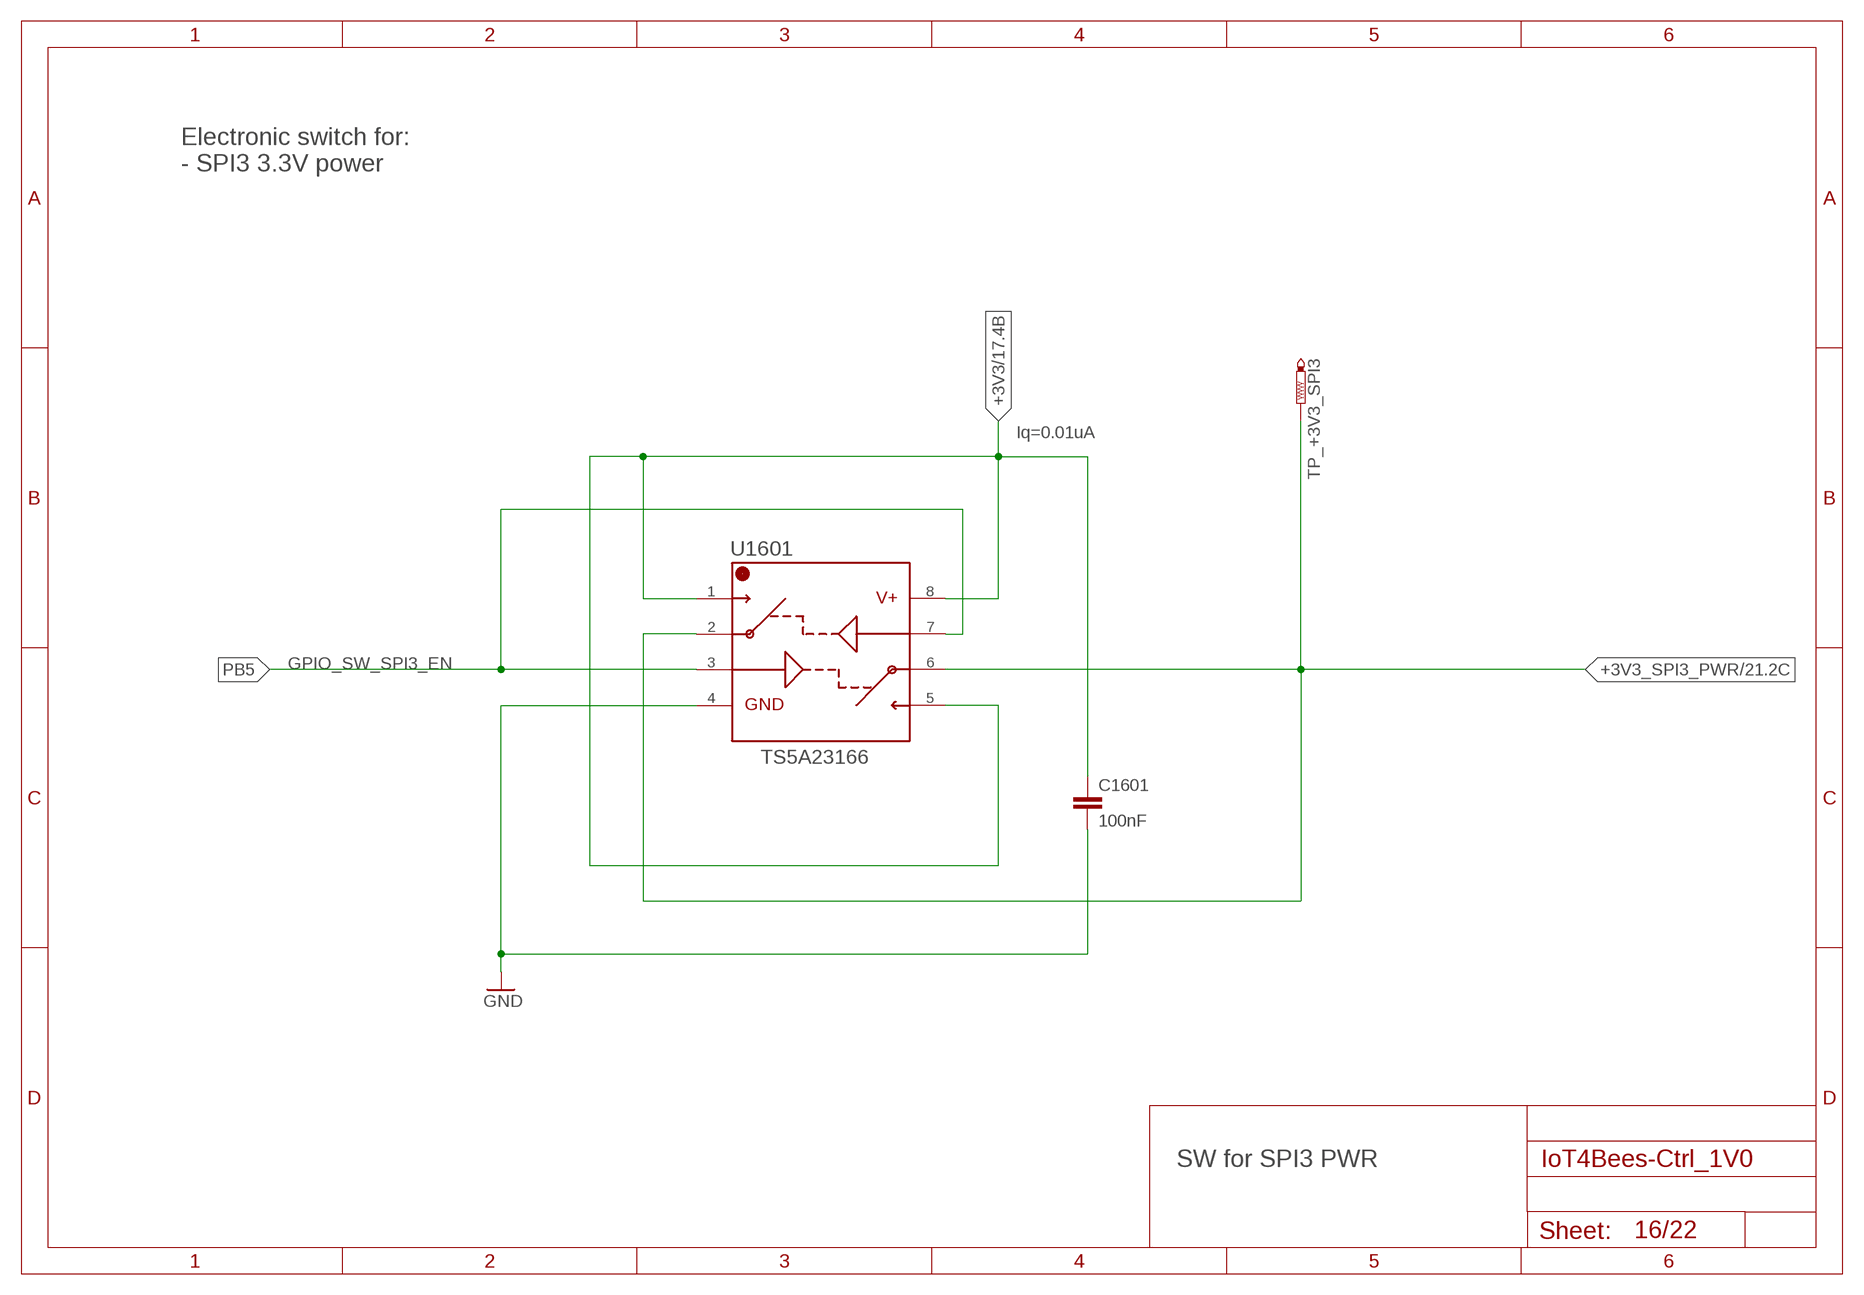
[diagram p15: schematic, sheet 16]
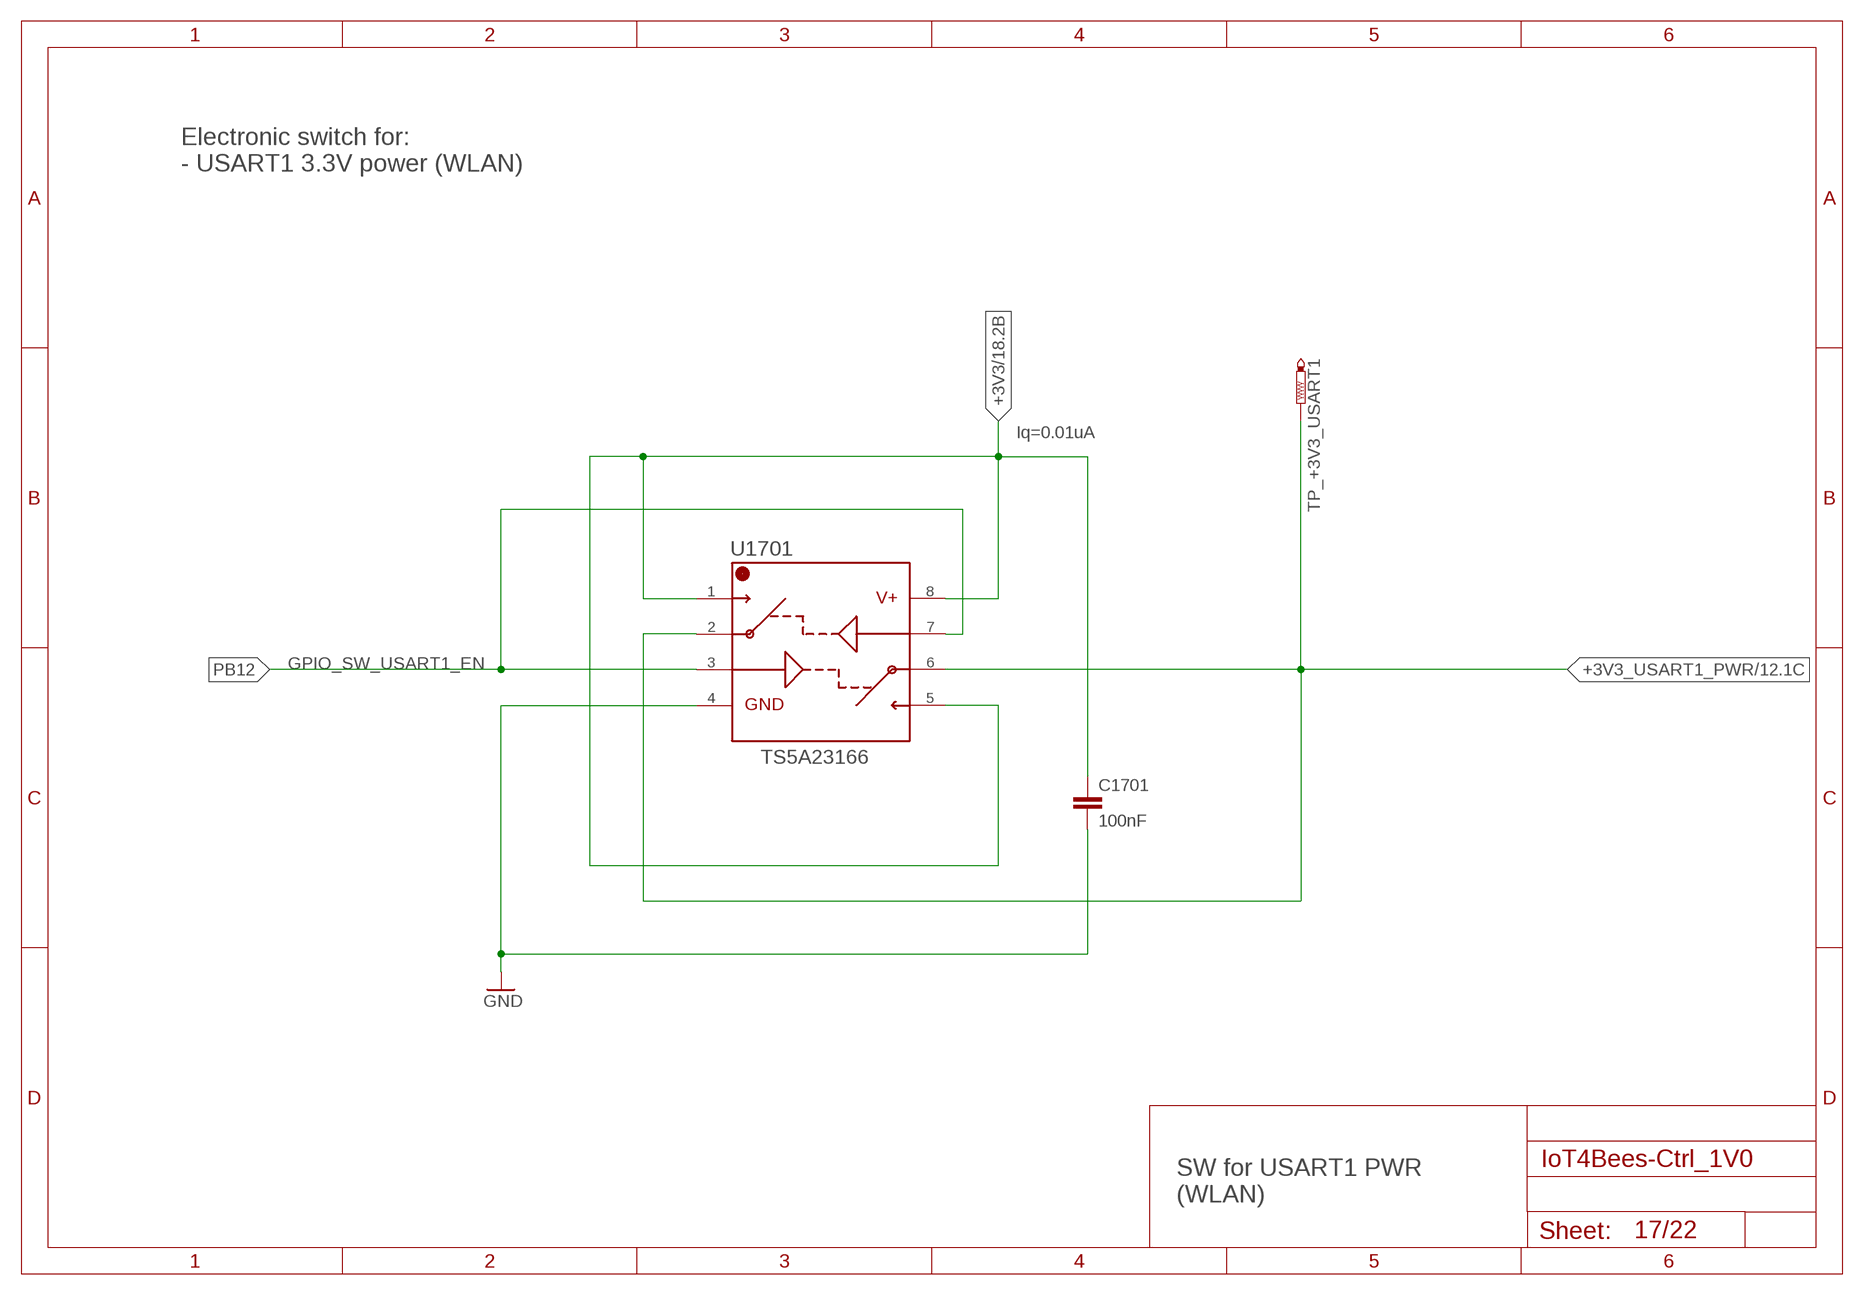
[diagram p16: schematic, sheet 17]
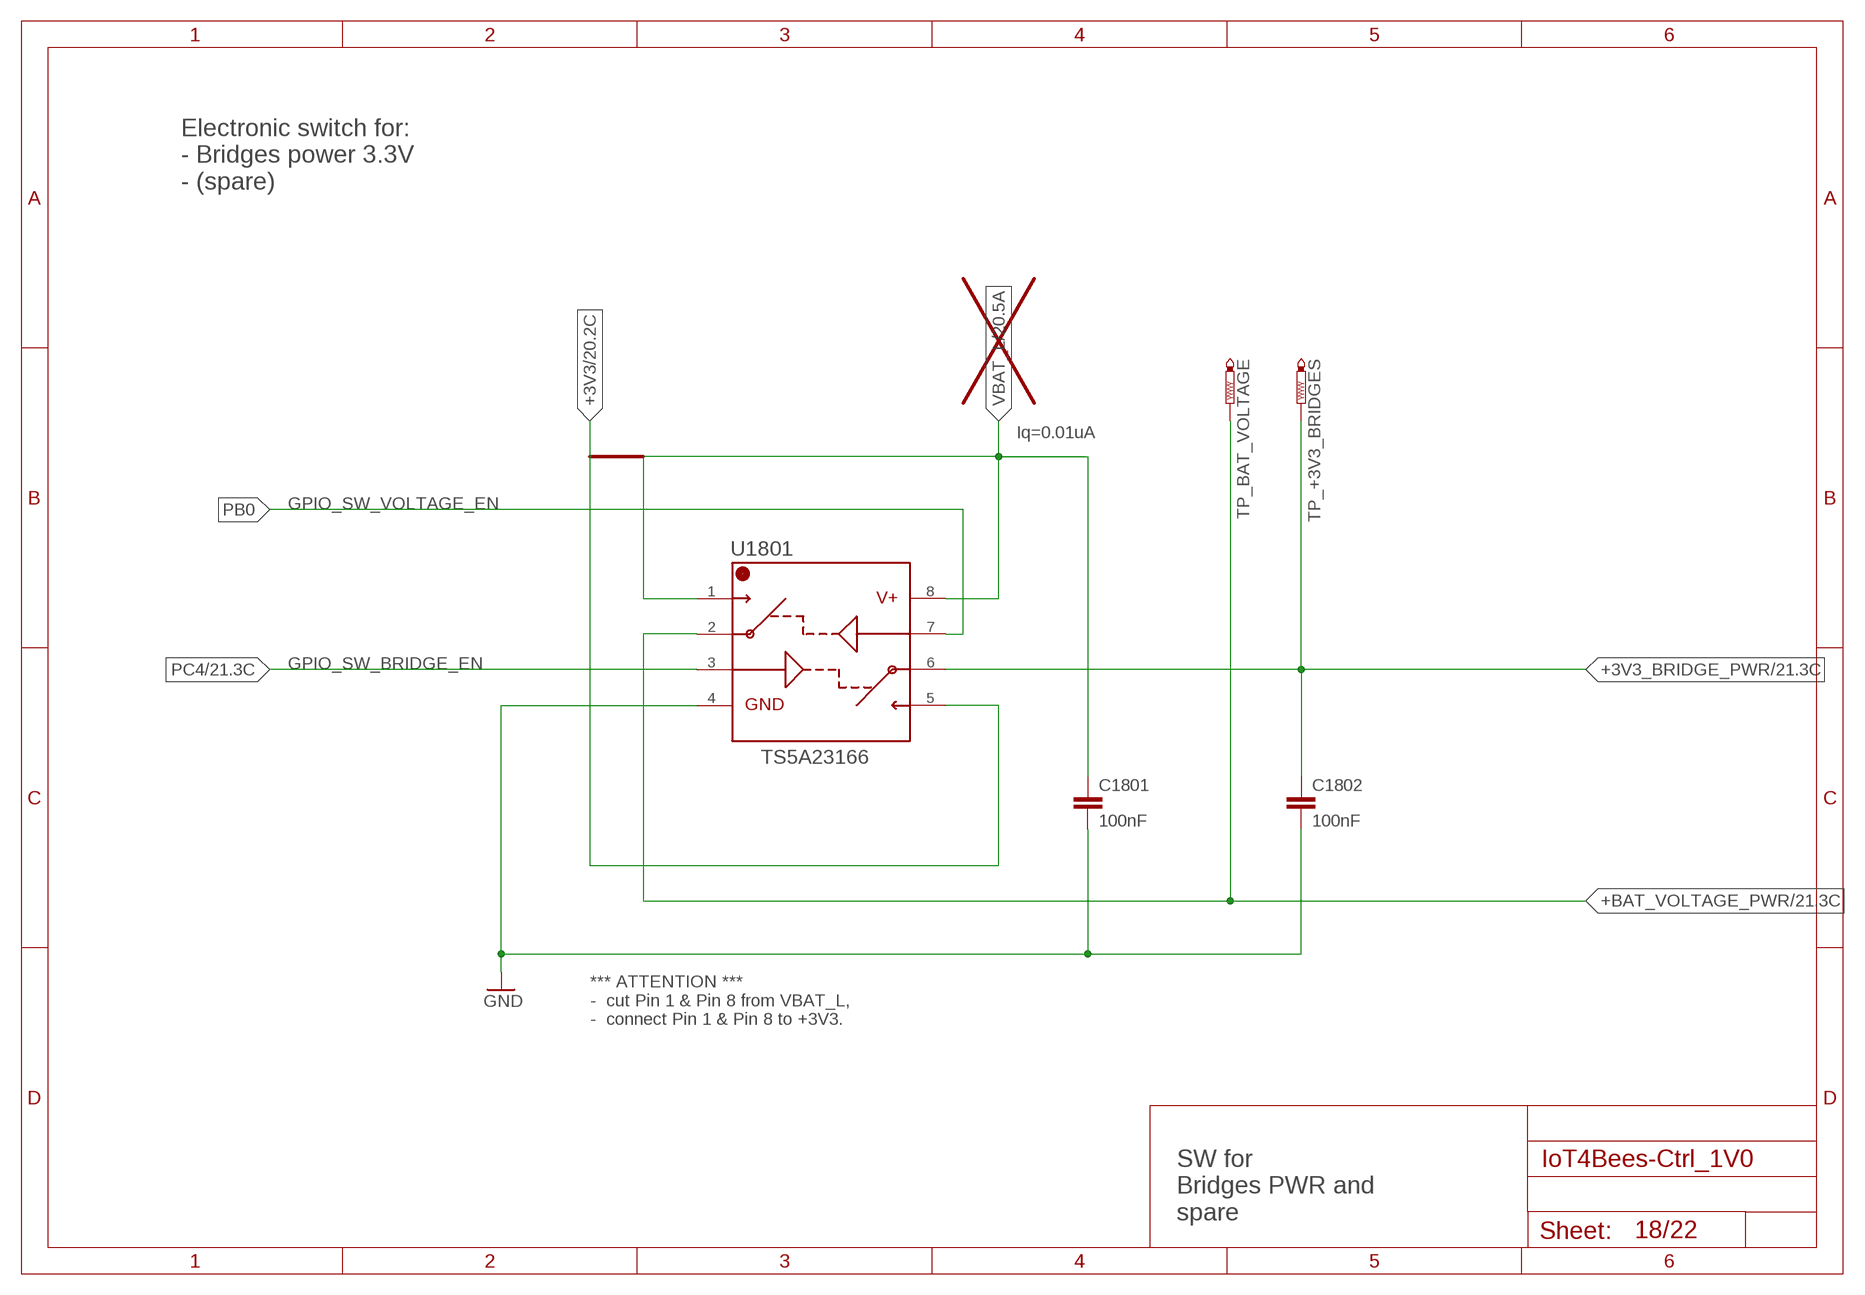
[diagram p17: schematic, sheet 18]
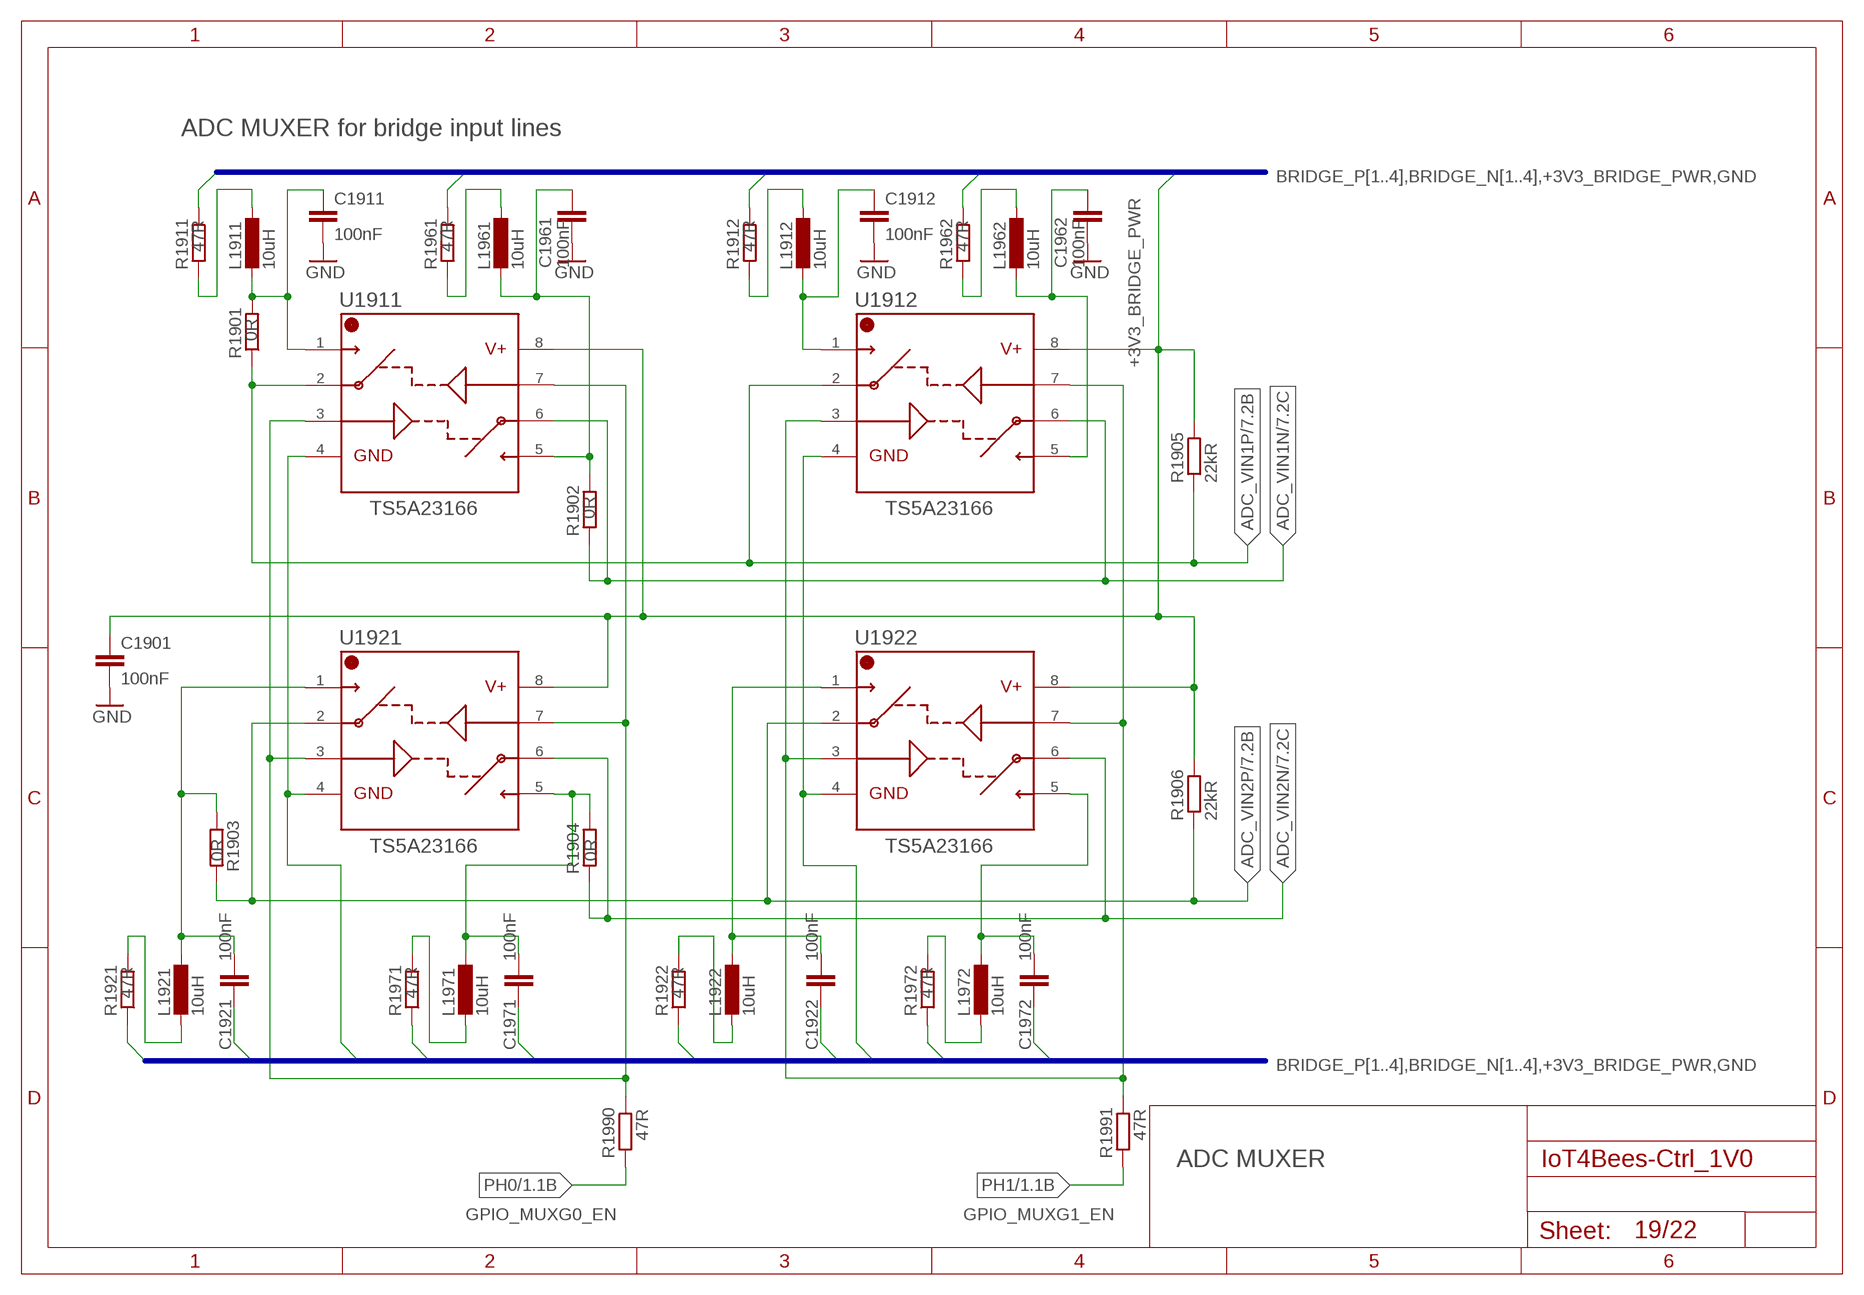
[diagram p18: schematic, sheet 19]
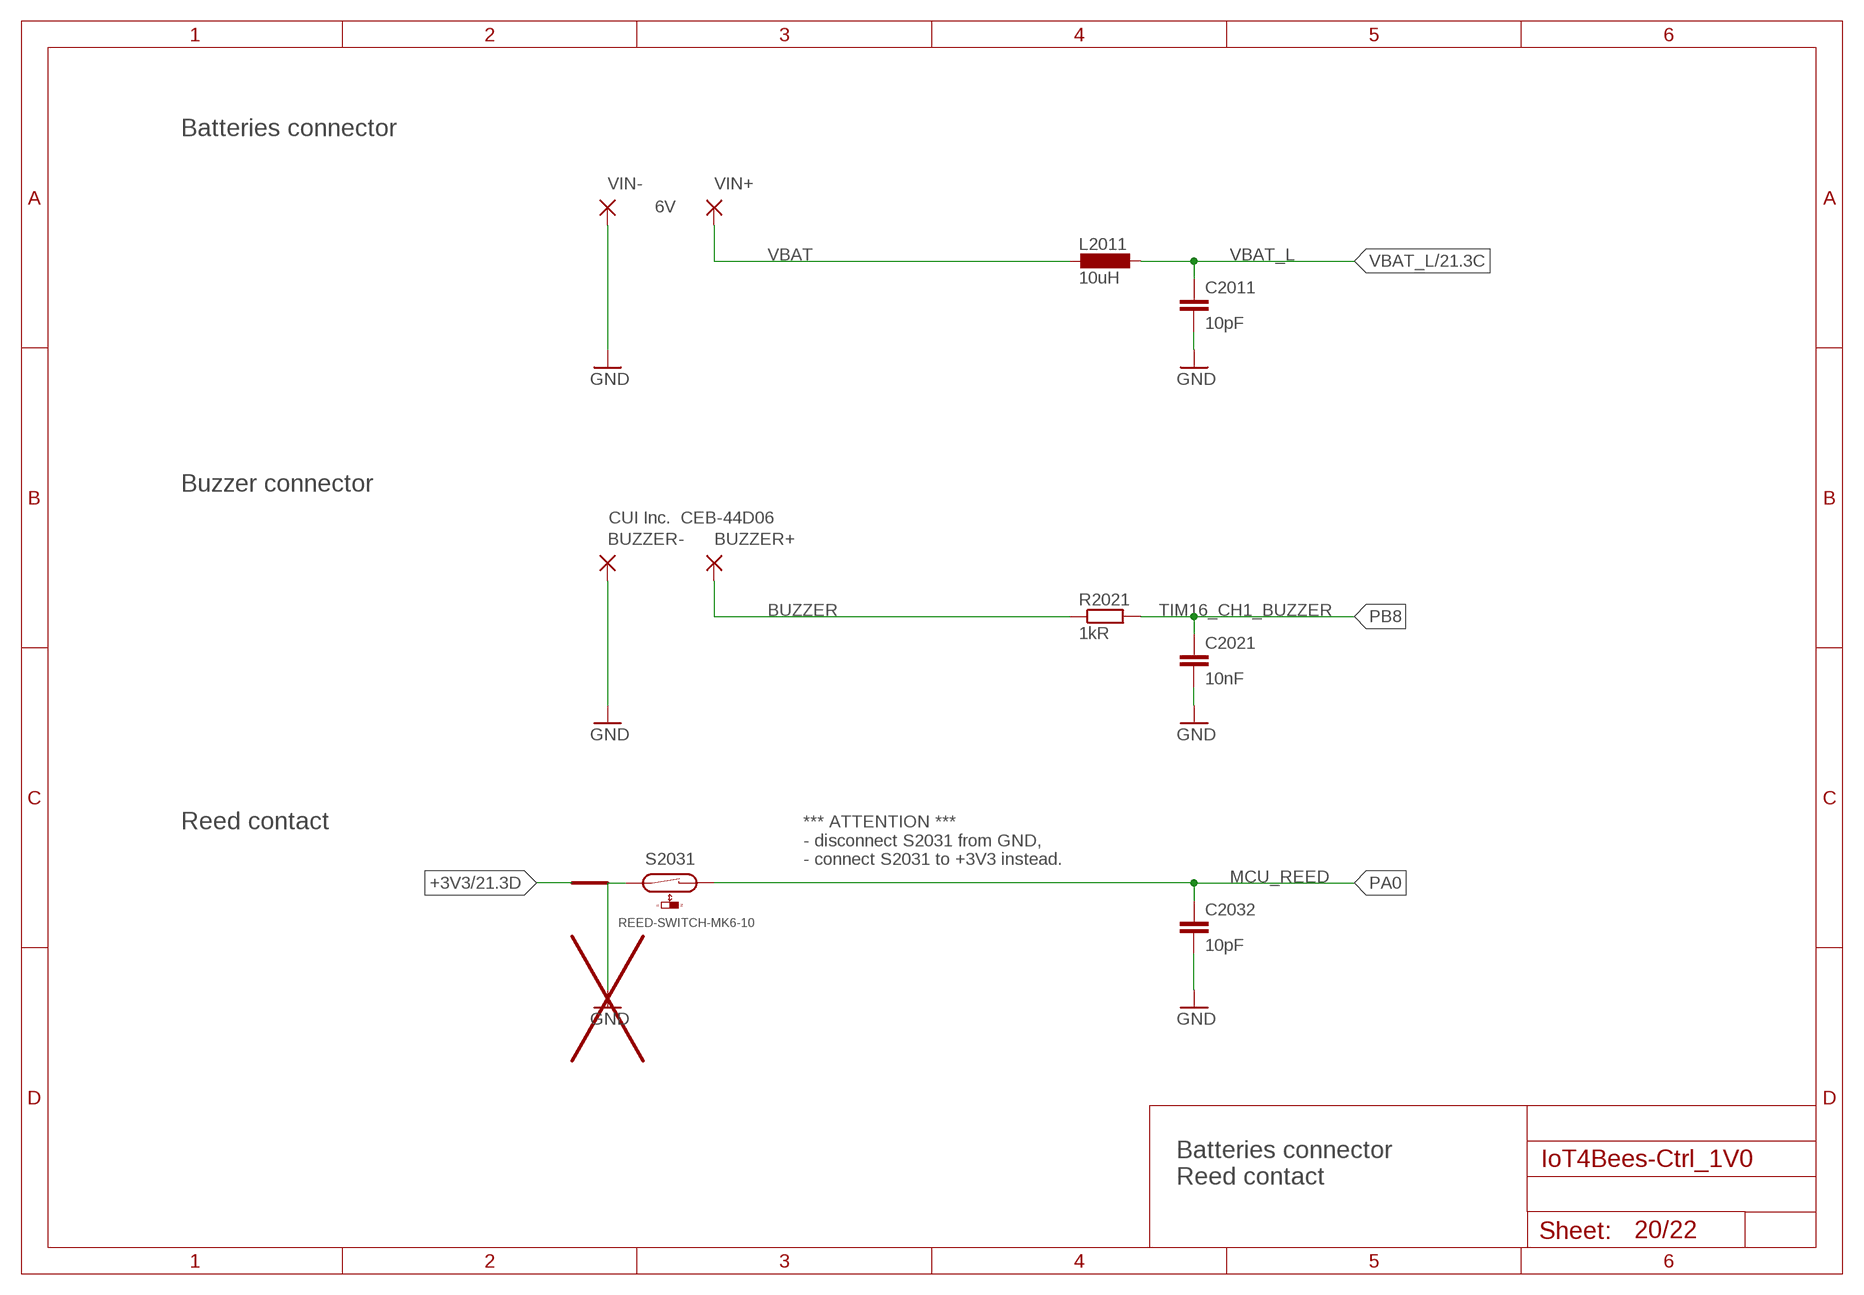
[diagram p19: schematic, sheet 20]
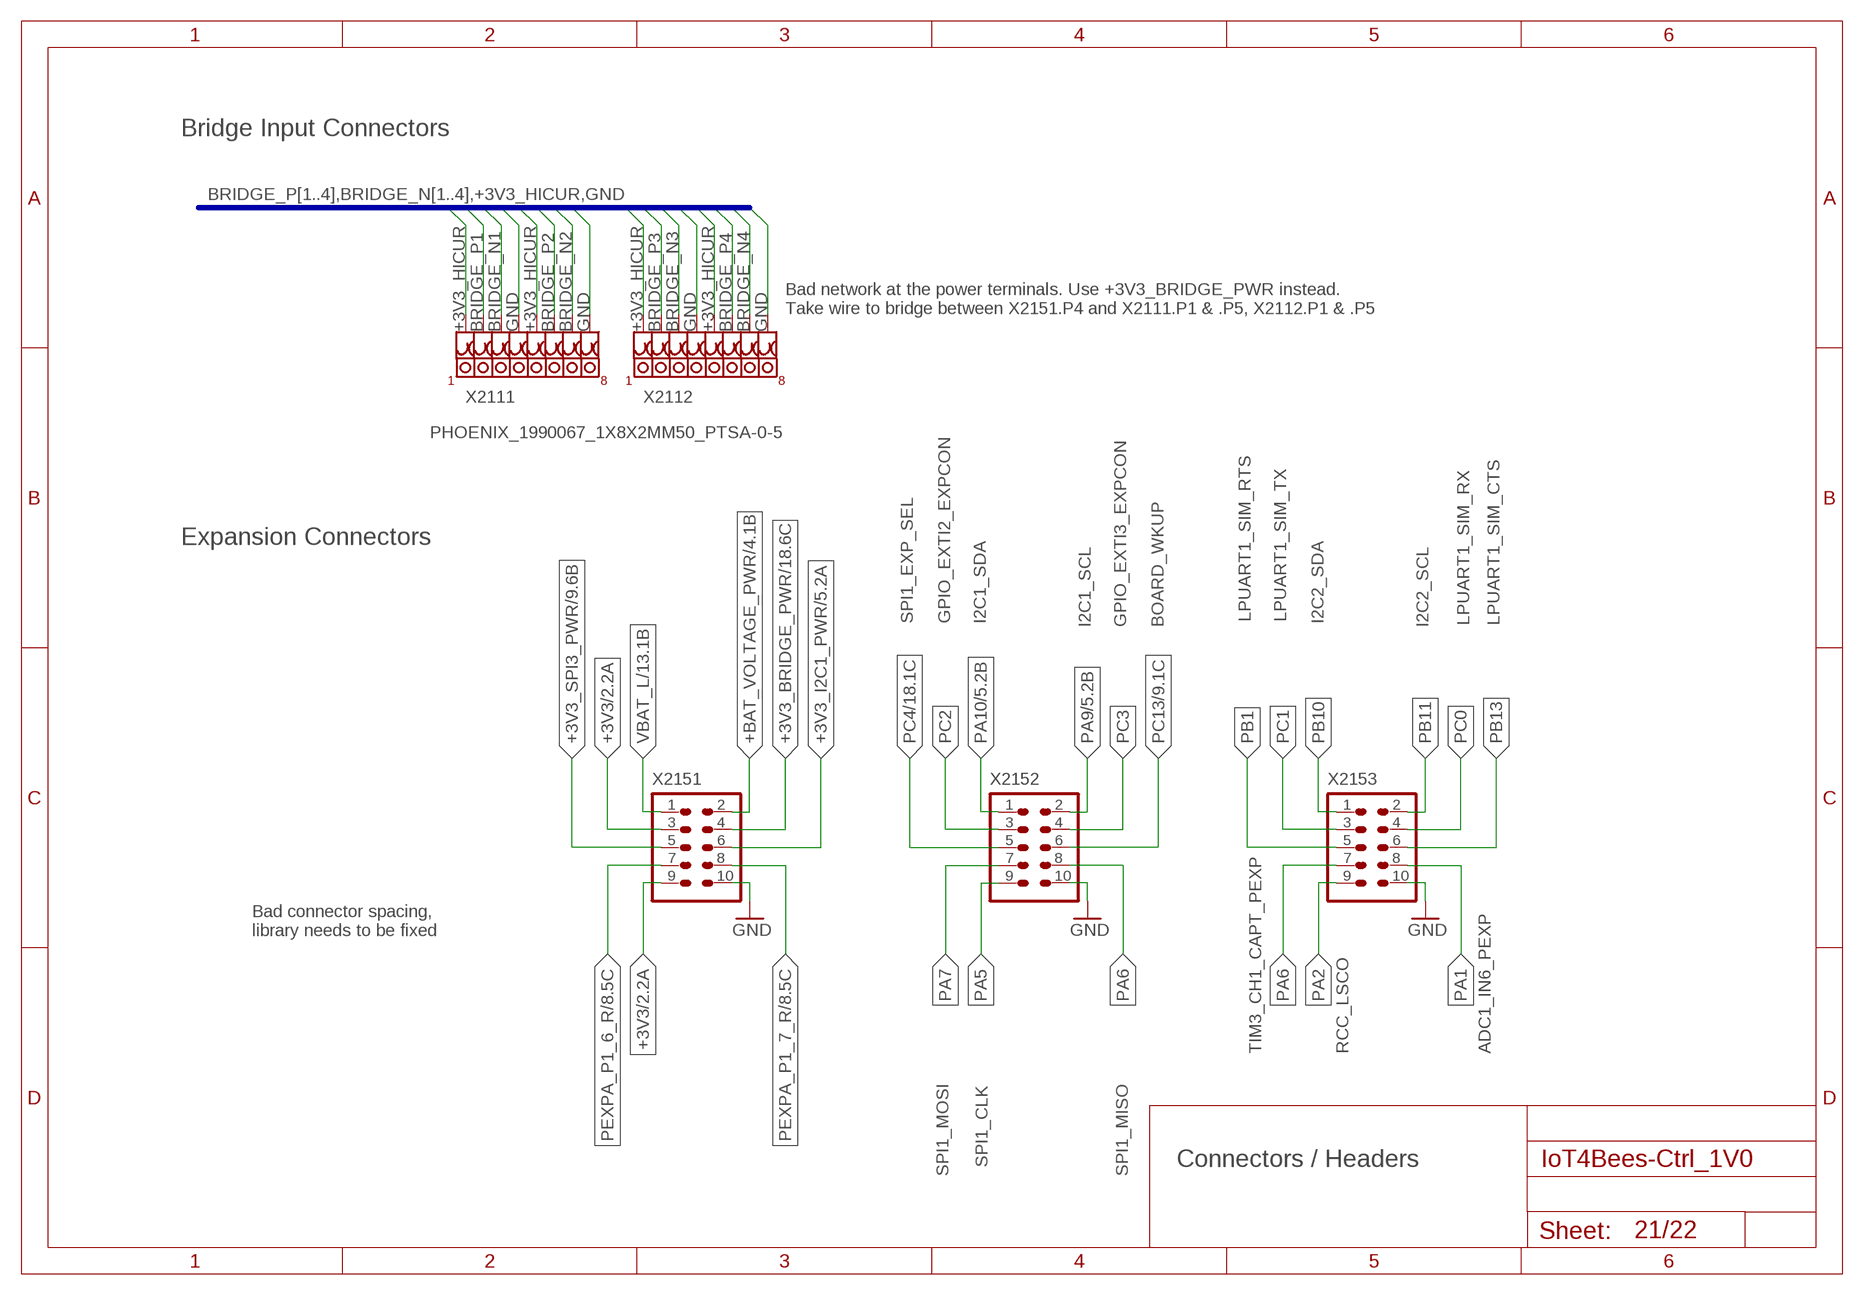
[diagram p20: schematic, sheet 21]
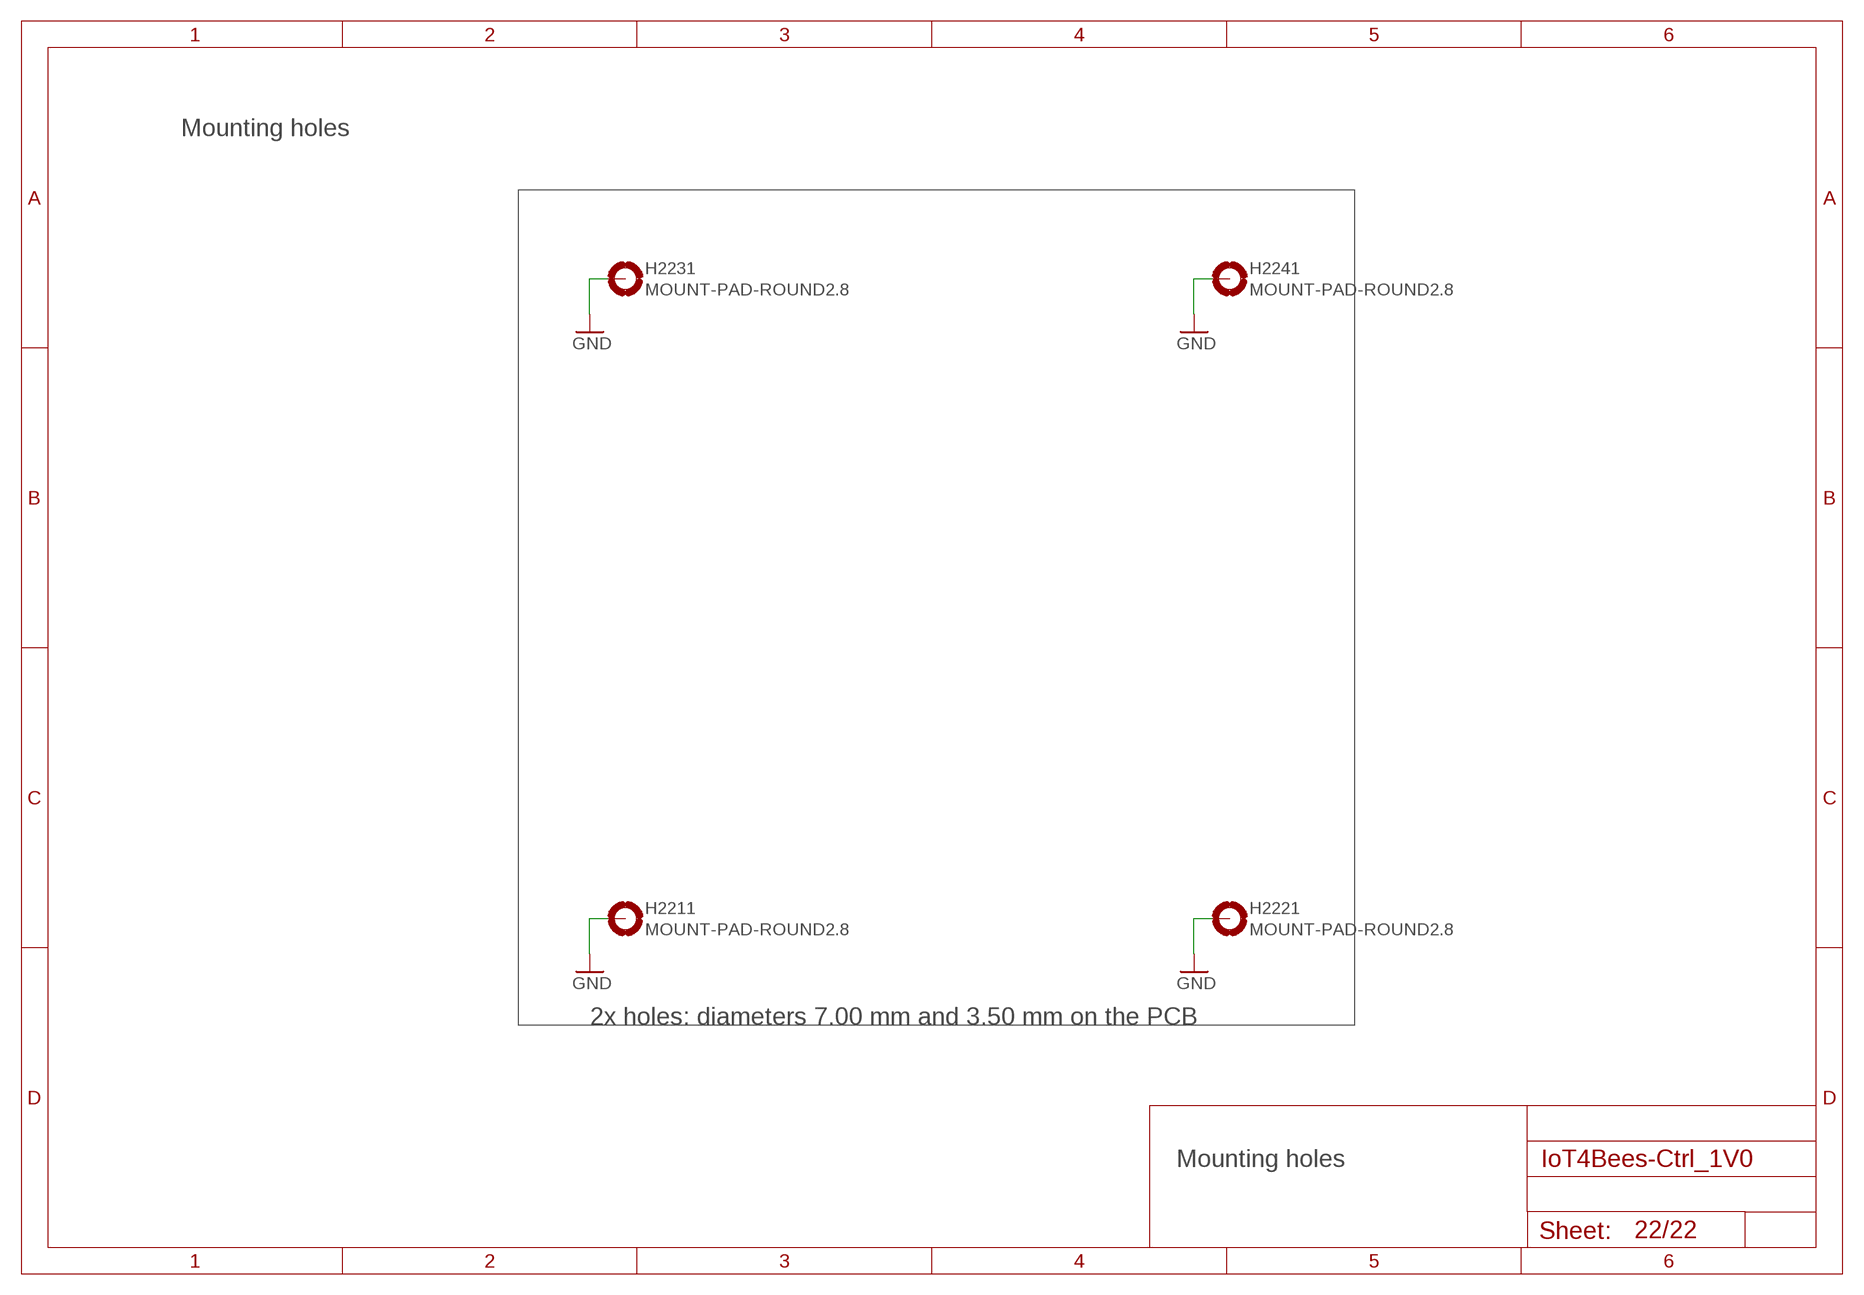
[diagram p21: schematic, sheet 22]

(export (version "E")
  (design (tool "Eeschema 10.0.6"))
  (components
    (comp (ref "C1401")
      (value "4.7uF")
      (footprint "eagle-import:C0603")
      (libsource (lib "eagle-import") (part "C-EUC0603"))
    )
    (comp (ref "C1421")
      (value "10uF")
      (footprint "eagle-import:C0603")
      (libsource (lib "eagle-import") (part "C-EUC0603"))
    )
    (comp (ref "L1411")
      (value "2.2uH")
      (footprint "eagle-import:L2016")
      (libsource (lib "eagle-import") (part "L-EUL2016"))
    )
    (comp (ref "U1411")
      (value "TPS62743YFPR")
      (footprint "eagle-import:WCSP-8")
      (libsource (lib "eagle-import") (part "TPS62743"))
    )
    (comp (ref "C0213")
      (value "100nF")
      (footprint "eagle-import:C0402")
      (libsource (lib "eagle-import") (part "C-EUC0402"))
    )
    (comp (ref "R0201")
      (value "220kR")
      (footprint "eagle-import:R0402")
      (libsource (lib "eagle-import") (part "R-EU_R0402"))
    )
    (comp (ref "R0202")
      (value "220kR")
      (footprint "eagle-import:R0402")
      (libsource (lib "eagle-import") (part "R-EU_R0402"))
    )
    (comp (ref "R0221")
      (value "33kR")
      (footprint "eagle-import:R0402")
      (libsource (lib "eagle-import") (part "R-EU_R0402"))
    )
    (comp (ref "S0212")
      (value "KSR223GLFG")
      (footprint "eagle-import:KSR223G_SMD_1POL")
      (libsource (lib "eagle-import") (part "KSR223G_SMD_1POL"))
    )
    (comp (ref "X0201")
      (value "FTSH-105-01-F-D-K")
      (footprint "eagle-import:2X05_1MM27_SHROUDED_CORTEX_JTAG_SWD")
      (libsource (lib "eagle-import") (part "2X05_1MM27_SHROUDED_CORTEX_JTAG_SWD{dblquote}"))
    )
    (comp (ref "X0222")
      (value "HEADER-1X2")
      (footprint "eagle-import:1X02")
      (libsource (lib "eagle-import") (part "HEADER-1X2"))
    )
    (comp (ref "R0511")
      (value "3.9kR")
      (footprint "eagle-import:R0402")
      (libsource (lib "eagle-import") (part "R-EU_R0402"))
    )
    (comp (ref "R0512")
      (value "3.9kR")
      (footprint "eagle-import:R0402")
      (libsource (lib "eagle-import") (part "R-EU_R0402"))
    )
    (comp (ref "C1201")
      (value "10uF")
      (footprint "eagle-import:C0603")
      (libsource (lib "eagle-import") (part "C-EUC0603"))
    )
    (comp (ref "C1202")
      (value "10nF")
      (footprint "eagle-import:C0402")
      (libsource (lib "eagle-import") (part "C-EUC0402"))
    )
    (comp (ref "R1257")
      (value "47R")
      (footprint "eagle-import:R0402")
      (libsource (lib "eagle-import") (part "R-EU_R0402"))
    )
    (comp (ref "R1266")
      (value "47R")
      (footprint "eagle-import:R0402")
      (libsource (lib "eagle-import") (part "R-EU_R0402"))
    )
    (comp (ref "R1271")
      (value "47R")
      (footprint "eagle-import:R0402")
      (libsource (lib "eagle-import") (part "R-EU_R0402"))
    )
    (comp (ref "R1272")
      (value "47R")
      (footprint "eagle-import:R0402")
      (libsource (lib "eagle-import") (part "R-EU_R0402"))
    )
    (comp (ref "U1211")
      (value "ESP-12F__2P00_24MM-X-16MM")
      (footprint "eagle-import:ESP-12F__2P00_24MM-X-16MM")
      (libsource (lib "eagle-import") (part "ESP-12F__2P00_24MM-X-16MM"))
    )
    (comp (ref "H2211")
      (value "MOUNT-PAD-ROUND2.8")
      (footprint "eagle-import:2,8-PAD")
      (libsource (lib "eagle-import") (part "MOUNT-PAD-ROUND2.8"))
    )
    (comp (ref "H2221")
      (value "MOUNT-PAD-ROUND2.8")
      (footprint "eagle-import:2,8-PAD")
      (libsource (lib "eagle-import") (part "MOUNT-PAD-ROUND2.8"))
    )
    (comp (ref "H2231")
      (value "MOUNT-PAD-ROUND2.8")
      (footprint "eagle-import:2,8-PAD")
      (libsource (lib "eagle-import") (part "MOUNT-PAD-ROUND2.8"))
    )
    (comp (ref "H2241")
      (value "MOUNT-PAD-ROUND2.8")
      (footprint "eagle-import:2,8-PAD")
      (libsource (lib "eagle-import") (part "MOUNT-PAD-ROUND2.8"))
    )
    (comp (ref "C1113")
      (value "100nF")
      (footprint "eagle-import:C0402")
      (libsource (lib "eagle-import") (part "C-EUC0402"))
    )
    (comp (ref "R1111")
      (value "47R")
      (footprint "eagle-import:R0402")
      (libsource (lib "eagle-import") (part "R-EU_R0402"))
    )
    (comp (ref "R1112")
      (value "100kR")
      (footprint "eagle-import:R0402")
      (libsource (lib "eagle-import") (part "R-EU_R0402"))
    )
    (comp (ref "U1111")
      (value "PCAL6416APW")
      (footprint "eagle-import:TSSOP24_SOT355-1")
      (libsource (lib "eagle-import") (part "PCAL6416APW"))
    )
    (comp (ref "U0101")
      (value "STM32L452RET_64PIN_SMPS")
      (footprint "eagle-import:LQFP64")
      (libsource (lib "eagle-import") (part "STM32L452RET_64PIN_SMPS"))
    )
    (comp (ref "C0311")
      (value "22pF")
      (footprint "eagle-import:C0402")
      (libsource (lib "eagle-import") (part "C-EUC0402"))
    )
    (comp (ref "C0331")
      (value "JR200")
      (footprint "eagle-import:3MM2_X_2MM5")
      (libsource (lib "eagle-import") (part "C-TRIMM3MM2_2MM5"))
    )
    (comp (ref "C0332")
      (value "0pF")
      (footprint "eagle-import:C0402")
      (libsource (lib "eagle-import") (part "C-EUC0402"))
    )
    (comp (ref "Q0321")
      (value "ABS07-32.768KHZ-7-1-T 7pF")
      (footprint "eagle-import:ABS07")
      (fields (field (name "MANUFACTURER") "ABS07-32.768KHZ-1-T"))
      (libsource (lib "eagle-import") (part "ABS07-32.768KHZ"))
    )
    (comp (ref "C0701")
      (value "100nF")
      (footprint "eagle-import:C0402")
      (libsource (lib "eagle-import") (part "C-EUC0402"))
    )
    (comp (ref "C0702")
      (value "100nF")
      (footprint "eagle-import:C0402")
      (libsource (lib "eagle-import") (part "C-EUC0402"))
    )
    (comp (ref "C0711")
      (value "100nF")
      (footprint "eagle-import:C0402")
      (libsource (lib "eagle-import") (part "C-EUC0402"))
    )
    (comp (ref "C0721")
      (value "100nF")
      (footprint "eagle-import:C0402")
      (libsource (lib "eagle-import") (part "C-EUC0402"))
    )
    (comp (ref "C0722")
      (value "100nF")
      (footprint "eagle-import:C0402")
      (libsource (lib "eagle-import") (part "C-EUC0402"))
    )
    (comp (ref "C0723")
      (value "100nF")
      (footprint "eagle-import:C0402")
      (libsource (lib "eagle-import") (part "C-EUC0402"))
    )
    (comp (ref "C0724")
      (value "100nF")
      (footprint "eagle-import:C0402")
      (libsource (lib "eagle-import") (part "C-EUC0402"))
    )
    (comp (ref "C0751")
      (value "100nF")
      (footprint "eagle-import:C0402")
      (libsource (lib "eagle-import") (part "C-EUC0402"))
    )
    (comp (ref "C0752")
      (value "100nF")
      (footprint "eagle-import:C0402")
      (libsource (lib "eagle-import") (part "C-EUC0402"))
    )
    (comp (ref "R0731")
      (value "47R")
      (footprint "eagle-import:R0402")
      (libsource (lib "eagle-import") (part "R-EU_R0402"))
    )
    (comp (ref "U0711")
      (value "NAU7802SGI")
      (footprint "eagle-import:LSOP16")
      (libsource (lib "eagle-import") (part "NAU7802_24BIT_I2C"))
    )
    (comp (ref "U0751")
      (value "MAX6129BEUK30+T")
      (footprint "eagle-import:SOT23P290X160-5N")
      (libsource (lib "eagle-import") (part "MAX6129_VREF"))
    )
    (comp (ref "C1901")
      (value "100nF")
      (footprint "eagle-import:C0402")
      (libsource (lib "eagle-import") (part "C-EUC0402"))
    )
    (comp (ref "C1911")
      (value "100nF")
      (footprint "eagle-import:C0402")
      (libsource (lib "eagle-import") (part "C-EUC0402"))
    )
    (comp (ref "C1912")
      (value "100nF")
      (footprint "eagle-import:C0402")
      (libsource (lib "eagle-import") (part "C-EUC0402"))
    )
    (comp (ref "C1921")
      (value "100nF")
      (footprint "eagle-import:C0402")
      (libsource (lib "eagle-import") (part "C-EUC0402"))
    )
    (comp (ref "C1922")
      (value "100nF")
      (footprint "eagle-import:C0402")
      (libsource (lib "eagle-import") (part "C-EUC0402"))
    )
    (comp (ref "C1961")
      (value "100nF")
      (footprint "eagle-import:C0402")
      (libsource (lib "eagle-import") (part "C-EUC0402"))
    )
    (comp (ref "C1962")
      (value "100nF")
      (footprint "eagle-import:C0402")
      (libsource (lib "eagle-import") (part "C-EUC0402"))
    )
    (comp (ref "C1971")
      (value "100nF")
      (footprint "eagle-import:C0402")
      (libsource (lib "eagle-import") (part "C-EUC0402"))
    )
    (comp (ref "C1972")
      (value "100nF")
      (footprint "eagle-import:C0402")
      (libsource (lib "eagle-import") (part "C-EUC0402"))
    )
    (comp (ref "L1911")
      (value "10uH")
      (footprint "eagle-import:L0603")
      (libsource (lib "eagle-import") (part "L-EUL0603"))
    )
    (comp (ref "L1912")
      (value "10uH")
      (footprint "eagle-import:L0603")
      (libsource (lib "eagle-import") (part "L-EUL0603"))
    )
    (comp (ref "L1921")
      (value "10uH")
      (footprint "eagle-import:L0603")
      (libsource (lib "eagle-import") (part "L-EUL0603"))
    )
    (comp (ref "L1922")
      (value "10uH")
      (footprint "eagle-import:L0603")
      (libsource (lib "eagle-import") (part "L-EUL0603"))
    )
    (comp (ref "L1961")
      (value "10uH")
      (footprint "eagle-import:L0603")
      (libsource (lib "eagle-import") (part "L-EUL0603"))
    )
    (comp (ref "L1962")
      (value "10uH")
      (footprint "eagle-import:L0603")
      (libsource (lib "eagle-import") (part "L-EUL0603"))
    )
    (comp (ref "L1971")
      (value "10uH")
      (footprint "eagle-import:L0603")
      (libsource (lib "eagle-import") (part "L-EUL0603"))
    )
    (comp (ref "L1972")
      (value "10uH")
      (footprint "eagle-import:L0603")
      (libsource (lib "eagle-import") (part "L-EUL0603"))
    )
    (comp (ref "R1901")
      (value "0R")
      (footprint "eagle-import:R0402")
      (libsource (lib "eagle-import") (part "R-EU_R0402"))
    )
    (comp (ref "R1902")
      (value "0R")
      (footprint "eagle-import:R0402")
      (libsource (lib "eagle-import") (part "R-EU_R0402"))
    )
    (comp (ref "R1903")
      (value "0R")
      (footprint "eagle-import:R0402")
      (libsource (lib "eagle-import") (part "R-EU_R0402"))
    )
    (comp (ref "R1904")
      (value "0R")
      (footprint "eagle-import:R0402")
      (libsource (lib "eagle-import") (part "R-EU_R0402"))
    )
    (comp (ref "R1905")
      (value "22kR")
      (footprint "eagle-import:R0402")
      (libsource (lib "eagle-import") (part "R-EU_R0402"))
    )
    (comp (ref "R1906")
      (value "22kR")
      (footprint "eagle-import:R0402")
      (libsource (lib "eagle-import") (part "R-EU_R0402"))
    )
    (comp (ref "R1911")
      (value "47R")
      (footprint "eagle-import:R0402")
      (libsource (lib "eagle-import") (part "R-EU_R0402"))
    )
    (comp (ref "R1912")
      (value "47R")
      (footprint "eagle-import:R0402")
      (libsource (lib "eagle-import") (part "R-EU_R0402"))
    )
    (comp (ref "R1921")
      (value "47R")
      (footprint "eagle-import:R0402")
      (libsource (lib "eagle-import") (part "R-EU_R0402"))
    )
    (comp (ref "R1922")
      (value "47R")
      (footprint "eagle-import:R0402")
      (libsource (lib "eagle-import") (part "R-EU_R0402"))
    )
    (comp (ref "R1961")
      (value "47R")
      (footprint "eagle-import:R0402")
      (libsource (lib "eagle-import") (part "R-EU_R0402"))
    )
    (comp (ref "R1962")
      (value "47R")
      (footprint "eagle-import:R0402")
      (libsource (lib "eagle-import") (part "R-EU_R0402"))
    )
    (comp (ref "R1971")
      (value "47R")
      (footprint "eagle-import:R0402")
      (libsource (lib "eagle-import") (part "R-EU_R0402"))
    )
    (comp (ref "R1972")
      (value "47R")
      (footprint "eagle-import:R0402")
      (libsource (lib "eagle-import") (part "R-EU_R0402"))
    )
    (comp (ref "R1990")
      (value "47R")
      (footprint "eagle-import:R0402")
      (libsource (lib "eagle-import") (part "R-EU_R0402"))
    )
    (comp (ref "R1991")
      (value "47R")
      (footprint "eagle-import:R0402")
      (libsource (lib "eagle-import") (part "R-EU_R0402"))
    )
    (comp (ref "U1911")
      (value "TS5A23166")
      (footprint "eagle-import:R-PDSO-G8")
      (libsource (lib "eagle-import") (part "TS5A23166"))
    )
    (comp (ref "U1912")
      (value "TS5A23166")
      (footprint "eagle-import:R-PDSO-G8")
      (libsource (lib "eagle-import") (part "TS5A23166"))
    )
    (comp (ref "U1921")
      (value "TS5A23166")
      (footprint "eagle-import:R-PDSO-G8")
      (libsource (lib "eagle-import") (part "TS5A23166"))
    )
    (comp (ref "U1922")
      (value "TS5A23166")
      (footprint "eagle-import:R-PDSO-G8")
      (libsource (lib "eagle-import") (part "TS5A23166"))
    )
    (comp (ref "C0901")
      (value "100nF")
      (footprint "eagle-import:C0402")
      (libsource (lib "eagle-import") (part "C-EUC0402"))
    )
    (comp (ref "C0902")
      (value "100nF")
      (footprint "eagle-import:C0402")
      (libsource (lib "eagle-import") (part "C-EUC0402"))
    )
    (comp (ref "C0903")
      (value "100nF")
      (footprint "eagle-import:C0402")
      (libsource (lib "eagle-import") (part "C-EUC0402"))
    )
    (comp (ref "C0921")
      (value "22pF")
      (footprint "eagle-import:C0402")
      (libsource (lib "eagle-import") (part "C-EUC0402"))
    )
    (comp (ref "C0922")
      (value "22pF")
      (footprint "eagle-import:C0402")
      (libsource (lib "eagle-import") (part "C-EUC0402"))
    )
    (comp (ref "D0901")
      (value "CMAD6001")
      (footprint "eagle-import:SOD923")
      (libsource (lib "eagle-import") (part "D_SOD923"))
    )
    (comp (ref "Q0921")
      (value "ABS07-32.768KHZ")
      (footprint "eagle-import:ABS07")
      (fields (field (name "MANUFACTURER") "ABS07-32.768KHZ-1-T"))
      (libsource (lib "eagle-import") (part "ABS07-32.768KHZ"))
    )
    (comp (ref "R0901")
      (value "3R")
      (footprint "eagle-import:R0402")
      (libsource (lib "eagle-import") (part "R-EU_R0402"))
    )
    (comp (ref "R0902")
      (value "3R")
      (footprint "eagle-import:R0402")
      (libsource (lib "eagle-import") (part "R-EU_R0402"))
    )
    (comp (ref "R0903")
      (value "47R")
      (footprint "eagle-import:R0402")
      (libsource (lib "eagle-import") (part "R-EU_R0402"))
    )
    (comp (ref "R0904")
      (value "3R")
      (footprint "eagle-import:R0402")
      (libsource (lib "eagle-import") (part "R-EU_R0402"))
    )
    (comp (ref "R0931")
      (value "3.9kR")
      (footprint "eagle-import:R0402")
      (libsource (lib "eagle-import") (part "R-EU_R0402"))
    )
    (comp (ref "R0932")
      (value "3.9kR")
      (footprint "eagle-import:R0402")
      (libsource (lib "eagle-import") (part "R-EU_R0402"))
    )
    (comp (ref "U0911")
      (value "BNO085")
      (footprint "eagle-import:BNO085_LGA28")
      (libsource (lib "eagle-import") (part "BNO085"))
    )
    (comp (ref "C1701")
      (value "100nF")
      (footprint "eagle-import:C0402")
      (libsource (lib "eagle-import") (part "C-EUC0402"))
    )
    (comp (ref "TP_+3V3_USART1")
      (value "PTR1TP06R")
      (footprint "eagle-import:TP06R")
      (libsource (lib "eagle-import") (part "PTR1TP06R"))
    )
    (comp (ref "U1701")
      (value "TS5A23166")
      (footprint "eagle-import:R-PDSO-G8")
      (libsource (lib "eagle-import") (part "TS5A23166"))
    )
    (comp (ref "C1501")
      (value "100nF")
      (footprint "eagle-import:C0402")
      (libsource (lib "eagle-import") (part "C-EUC0402"))
    )
    (comp (ref "C1502")
      (value "100nF")
      (footprint "eagle-import:C0402")
      (libsource (lib "eagle-import") (part "C-EUC0402"))
    )
    (comp (ref "C1521")
      (value "100nF")
      (footprint "eagle-import:C0402")
      (libsource (lib "eagle-import") (part "C-EUC0402"))
    )
    (comp (ref "C1591")
      (value "100nF")
      (footprint "eagle-import:C0402")
      (libsource (lib "eagle-import") (part "C-EUC0402"))
    )
    (comp (ref "C1592")
      (value "100nF")
      (footprint "eagle-import:C0402")
      (libsource (lib "eagle-import") (part "C-EUC0402"))
    )
    (comp (ref "TP_+1V2_MCU")
      (value "PTR1TP06R")
      (footprint "eagle-import:TP06R")
      (libsource (lib "eagle-import") (part "PTR1TP06R"))
    )
    (comp (ref "TP_+3V3_I2C1")
      (value "PTR1TP06R")
      (footprint "eagle-import:TP06R")
      (libsource (lib "eagle-import") (part "PTR1TP06R"))
    )
    (comp (ref "U1511")
      (value "TS5A23166")
      (footprint "eagle-import:R-PDSO-G8")
      (libsource (lib "eagle-import") (part "TS5A23166"))
    )
    (comp (ref "C0401")
      (value "100nF")
      (footprint "eagle-import:C0402")
      (libsource (lib "eagle-import") (part "C-EUC0402"))
    )
    (comp (ref "C0402")
      (value "100nF")
      (footprint "eagle-import:C0402")
      (libsource (lib "eagle-import") (part "C-EUC0402"))
    )
    (comp (ref "C0403")
      (value "100nF")
      (footprint "eagle-import:C0402")
      (libsource (lib "eagle-import") (part "C-EUC0402"))
    )
    (comp (ref "C0410")
      (value "4.7uF")
      (footprint "eagle-import:C0603")
      (libsource (lib "eagle-import") (part "C-EUC0603"))
    )
    (comp (ref "C0412")
      (value "10nF")
      (footprint "eagle-import:C0402")
      (libsource (lib "eagle-import") (part "C-EUC0402"))
    )
    (comp (ref "C0413")
      (value "1uF")
      (footprint "eagle-import:C0402")
      (libsource (lib "eagle-import") (part "C-EUC0402"))
    )
    (comp (ref "C0451")
      (value "47uF")
      (footprint "eagle-import:C0805")
      (libsource (lib "eagle-import") (part "C-EUC0805"))
    )
    (comp (ref "C0461")
      (value "100nF")
      (footprint "eagle-import:C0402")
      (libsource (lib "eagle-import") (part "C-EUC0402"))
    )
    (comp (ref "L0411")
      (value "10uH")
      (footprint "eagle-import:L0603")
      (libsource (lib "eagle-import") (part "L-EUL0603"))
    )
    (comp (ref "R0401")
      (value "0R")
      (footprint "eagle-import:R0402")
      (libsource (lib "eagle-import") (part "R-EU_R0402"))
    )
    (comp (ref "R0421")
      (value "0R")
      (footprint "eagle-import:R0402")
      (libsource (lib "eagle-import") (part "R-EU_R0402"))
    )
    (comp (ref "R0441")
      (value "0R")
      (footprint "eagle-import:R0402")
      (libsource (lib "eagle-import") (part "R-EU_R0402"))
    )
    (comp (ref "R0461")
      (value "47kR")
      (footprint "eagle-import:R0402")
      (libsource (lib "eagle-import") (part "R-EU_R0402"))
    )
    (comp (ref "R0462")
      (value "100kR")
      (footprint "eagle-import:R0402")
      (libsource (lib "eagle-import") (part "R-EU_R0402"))
    )
    (comp (ref "TP_VBAT")
      (value "PTR1TP06R")
      (footprint "eagle-import:TP06R")
      (libsource (lib "eagle-import") (part "PTR1TP06R"))
    )
    (comp (ref "C0801")
      (value "100nF")
      (footprint "eagle-import:C0402")
      (libsource (lib "eagle-import") (part "C-EUC0402"))
    )
    (comp (ref "R0802")
      (value "100kR")
      (footprint "eagle-import:R0402")
      (libsource (lib "eagle-import") (part "R-EU_R0402"))
    )
    (comp (ref "R0811")
      (value "3R")
      (footprint "eagle-import:R0402")
      (libsource (lib "eagle-import") (part "R-EU_R0402"))
    )
    (comp (ref "U0811")
      (value "PCAL6416APW")
      (footprint "eagle-import:TSSOP24_SOT355-1")
      (libsource (lib "eagle-import") (part "PCAL6416APW"))
    )
    (comp (ref "BUZZER+")
      (value "CUI Inc. CEB-44D06")
      (footprint "eagle-import:SMD2,54-5,08")
      (libsource (lib "eagle-import") (part "SMD5"))
    )
    (comp (ref "BUZZER-")
      (value "CUI Inc. CEB-44D06")
      (footprint "eagle-import:SMD2,54-5,08")
      (libsource (lib "eagle-import") (part "SMD5"))
    )
    (comp (ref "C2011")
      (value "10pF")
      (footprint "eagle-import:C0402")
      (libsource (lib "eagle-import") (part "C-EUC0402"))
    )
    (comp (ref "C2021")
      (value "10nF")
      (footprint "eagle-import:C0402")
      (libsource (lib "eagle-import") (part "C-EUC0402"))
    )
    (comp (ref "C2032")
      (value "10pF")
      (footprint "eagle-import:C0402")
      (libsource (lib "eagle-import") (part "C-EUC0402"))
    )
    (comp (ref "L2011")
      (value "10uH")
      (footprint "eagle-import:L0603")
      (libsource (lib "eagle-import") (part "L-EUL0603"))
    )
    (comp (ref "R2021")
      (value "1kR")
      (footprint "eagle-import:R0402")
      (libsource (lib "eagle-import") (part "R-EU_R0402"))
    )
    (comp (ref "S2031")
      (value "REED-SWITCH-MK6-10")
      (footprint "eagle-import:MK6-10")
      (libsource (lib "eagle-import") (part "REED-SWITCH-MK6-10"))
    )
    (comp (ref "VIN+")
      (value "6V")
      (footprint "eagle-import:SMD2,54-5,08")
      (libsource (lib "eagle-import") (part "SMD5"))
    )
    (comp (ref "VIN-")
      (value "6V")
      (footprint "eagle-import:SMD2,54-5,08")
      (libsource (lib "eagle-import") (part "SMD5"))
    )
    (comp (ref "C0601")
      (value "100nF")
      (footprint "eagle-import:C0402")
      (libsource (lib "eagle-import") (part "C-EUC0402"))
    )
    (comp (ref "U0611")
      (value "MR44V064BMAZAATL")
      (footprint "eagle-import:SOIC8_150MIL")
      (libsource (lib "eagle-import") (part "FEDR44V064B-02_FRAM_8K-8_I2C"))
    )
    (comp (ref "C1301")
      (value "10uF")
      (footprint "eagle-import:C0603")
      (libsource (lib "eagle-import") (part "C-EUC0603"))
    )
    (comp (ref "C1321")
      (value "10uF")
      (footprint "eagle-import:C0603")
      (libsource (lib "eagle-import") (part "C-EUC0603"))
    )
    (comp (ref "L1311")
      (value "4.7uH")
      (footprint "eagle-import:L2520")
      (libsource (lib "eagle-import") (part "L-EUL2520"))
    )
    (comp (ref "U1311")
      (value "TPS62745DSSR")
      (footprint "eagle-import:WSON-12")
      (libsource (lib "eagle-import") (part "TPS62745"))
    )
    (comp (ref "C1601")
      (value "100nF")
      (footprint "eagle-import:C0402")
      (libsource (lib "eagle-import") (part "C-EUC0402"))
    )
    (comp (ref "TP_+3V3_SPI3")
      (value "PTR1TP06R")
      (footprint "eagle-import:TP06R")
      (libsource (lib "eagle-import") (part "PTR1TP06R"))
    )
    (comp (ref "U1601")
      (value "TS5A23166")
      (footprint "eagle-import:R-PDSO-G8")
      (libsource (lib "eagle-import") (part "TS5A23166"))
    )
    (comp (ref "C1801")
      (value "100nF")
      (footprint "eagle-import:C0402")
      (libsource (lib "eagle-import") (part "C-EUC0402"))
    )
    (comp (ref "C1802")
      (value "100nF")
      (footprint "eagle-import:C0402")
      (libsource (lib "eagle-import") (part "C-EUC0402"))
    )
    (comp (ref "TP_+3V3_BRIDGES")
      (value "PTR1TP06R")
      (footprint "eagle-import:TP06R")
      (libsource (lib "eagle-import") (part "PTR1TP06R"))
    )
    (comp (ref "TP_BAT_VOLTAGE")
      (value "PTR1TP06R")
      (footprint "eagle-import:TP06R")
      (libsource (lib "eagle-import") (part "PTR1TP06R"))
    )
    (comp (ref "U1801")
      (value "TS5A23166")
      (footprint "eagle-import:R-PDSO-G8")
      (libsource (lib "eagle-import") (part "TS5A23166"))
    )
    (comp (ref "X2111")
      (value "PHOENIX_1990067_1X8X2MM50_PTSA-0-5")
      (footprint "eagle-import:PHOENIX_1990067_1X8X2MM50_PTSA-0-5")
      (libsource (lib "eagle-import") (part "PHOENIX_1990067_1X8X2MM50_PTSA-0-5"))
    )
    (comp (ref "X2112")
      (value "PHOENIX_1990067_1X8X2MM50_PTSA-0-5")
      (footprint "eagle-import:PHOENIX_1990067_1X8X2MM50_PTSA-0-5")
      (libsource (lib "eagle-import") (part "PHOENIX_1990067_1X8X2MM50_PTSA-0-5"))
    )
    (comp (ref "X2151")
      (value "HEADER-2X5_1MM27_BAD")
      (footprint "eagle-import:2X05_1MM27_BAD")
      (libsource (lib "eagle-import") (part "HEADER-2X5_1MM27_BAD"))
    )
    (comp (ref "X2152")
      (value "HEADER-2X5_1MM27_BAD")
      (footprint "eagle-import:2X05_1MM27_BAD")
      (libsource (lib "eagle-import") (part "HEADER-2X5_1MM27_BAD"))
    )
    (comp (ref "X2153")
      (value "HEADER-2X5_1MM27_BAD")
      (footprint "eagle-import:2X05_1MM27_BAD")
      (libsource (lib "eagle-import") (part "HEADER-2X5_1MM27_BAD"))
    )
    (comp (ref "C1001")
      (value "10uF")
      (footprint "eagle-import:C0603")
      (libsource (lib "eagle-import") (part "C-EUC0603"))
    )
    (comp (ref "C1002")
      (value "10nF")
      (footprint "eagle-import:C0402")
      (libsource (lib "eagle-import") (part "C-EUC0402"))
    )
    (comp (ref "C1003")
      (value "470nF")
      (footprint "eagle-import:C0402")
      (libsource (lib "eagle-import") (part "C-EUC0402"))
    )
    (comp (ref "C1004")
      (value "47pF")
      (footprint "eagle-import:C0402")
      (libsource (lib "eagle-import") (part "C-EUC0402"))
    )
    (comp (ref "C1005")
      (value "47nF")
      (footprint "eagle-import:C0402")
      (libsource (lib "eagle-import") (part "C-EUC0402"))
    )
    (comp (ref "C1063")
      (value "3.3pF")
      (footprint "eagle-import:C0402")
      (libsource (lib "eagle-import") (part "C-EUC0402"))
    )
    (comp (ref "C1064")
      (value "22pF")
      (footprint "eagle-import:C0402")
      (libsource (lib "eagle-import") (part "C-EUC0402"))
    )
    (comp (ref "C1065")
      (value "1.8pF")
      (footprint "eagle-import:C0402")
      (libsource (lib "eagle-import") (part "C-EUC0402"))
    )
    (comp (ref "C1066")
      (value "3.3pF")
      (footprint "eagle-import:C0402")
      (libsource (lib "eagle-import") (part "C-EUC0402"))
    )
    (comp (ref "C1067")
      (value "0pF")
      (footprint "eagle-import:C0402")
      (libsource (lib "eagle-import") (part "C-EUC0402"))
    )
    (comp (ref "C1071")
      (value "1nF")
      (footprint "eagle-import:C0402")
      (libsource (lib "eagle-import") (part "C-EUC0402"))
    )
    (comp (ref "C1072")
      (value "1nF")
      (footprint "eagle-import:C0402")
      (libsource (lib "eagle-import") (part "C-EUC0402"))
    )
    (comp (ref "C1081")
      (value "33pF")
      (footprint "eagle-import:C0402")
      (libsource (lib "eagle-import") (part "C-EUC0402"))
    )
    (comp (ref "C1082")
      (value "2.7pF")
      (footprint "eagle-import:C0402")
      (libsource (lib "eagle-import") (part "C-EUC0402"))
    )
    (comp (ref "C1083")
      (value "2.2pF")
      (footprint "eagle-import:C0402")
      (libsource (lib "eagle-import") (part "C-EUC0402"))
    )
    (comp (ref "C1091")
      (value "2.7pF")
      (footprint "eagle-import:C0402")
      (libsource (lib "eagle-import") (part "C-EUC0402"))
    )
    (comp (ref "C1092")
      (value "3.8pF")
      (footprint "eagle-import:C0402")
      (libsource (lib "eagle-import") (part "C-EUC0402"))
    )
    (comp (ref "C1093")
      (value "0pF")
      (footprint "eagle-import:C0402")
      (libsource (lib "eagle-import") (part "C-EUC0402"))
    )
    (comp (ref "L1001")
      (value "15uH")
      (footprint "eagle-import:L0805")
      (libsource (lib "eagle-import") (part "L-EUL0805"))
    )
    (comp (ref "L1002")
      (value "47nH")
      (footprint "eagle-import:L0603")
      (libsource (lib "eagle-import") (part "L-EUL0603"))
    )
    (comp (ref "L1062")
      (value "47nH")
      (footprint "eagle-import:L0603")
      (libsource (lib "eagle-import") (part "L-EUL0603"))
    )
    (comp (ref "L1063")
      (value "2.2nH")
      (footprint "eagle-import:L0603")
      (libsource (lib "eagle-import") (part "L-EUL0603"))
    )
    (comp (ref "L1064")
      (value "1.5nH")
      (footprint "eagle-import:L0603")
      (libsource (lib "eagle-import") (part "L-EUL0603"))
    )
    (comp (ref "L1082")
      (value "6.8nH")
      (footprint "eagle-import:L0603")
      (libsource (lib "eagle-import") (part "L-EUL0603"))
    )
    (comp (ref "L1091")
      (value "13nH")
      (footprint "eagle-import:L0603")
      (libsource (lib "eagle-import") (part "L-EUL0603"))
    )
    (comp (ref "Q1011")
      (value "ABM3B-32.0000MHZ")
      (footprint "eagle-import:ABM3B")
      (libsource (lib "eagle-import") (part "ABM3B-32.0000MHZ"))
    )
    (comp (ref "R1011")
      (value "3R")
      (footprint "eagle-import:R0402")
      (libsource (lib "eagle-import") (part "R-EU_R0402"))
    )
    (comp (ref "R1021")
      (value "3R")
      (footprint "eagle-import:R0402")
      (libsource (lib "eagle-import") (part "R-EU_R0402"))
    )
    (comp (ref "R1024")
      (value "3R")
      (footprint "eagle-import:R0402")
      (libsource (lib "eagle-import") (part "R-EU_R0402"))
    )
    (comp (ref "R1051")
      (value "47R")
      (footprint "eagle-import:R0402")
      (libsource (lib "eagle-import") (part "R-EU_R0402"))
    )
    (comp (ref "R1052")
      (value "47R")
      (footprint "eagle-import:R0402")
      (libsource (lib "eagle-import") (part "R-EU_R0402"))
    )
    (comp (ref "R1053")
      (value "47R")
      (footprint "eagle-import:R0402")
      (libsource (lib "eagle-import") (part "R-EU_R0402"))
    )
    (comp (ref "R1071")
      (value "47R")
      (footprint "eagle-import:R0402")
      (libsource (lib "eagle-import") (part "R-EU_R0402"))
    )
    (comp (ref "TP_SX_DIO1")
      (value "PTR1TP06R")
      (footprint "eagle-import:TP06R")
      (libsource (lib "eagle-import") (part "PTR1TP06R"))
    )
    (comp (ref "TP_SX_DIO2")
      (value "PTR1TP06R")
      (footprint "eagle-import:TP06R")
      (libsource (lib "eagle-import") (part "PTR1TP06R"))
    )
    (comp (ref "TP_SX_DIO3")
      (value "PTR1TP06R")
      (footprint "eagle-import:TP06R")
      (libsource (lib "eagle-import") (part "PTR1TP06R"))
    )
    (comp (ref "U1001")
      (value "SX1261IMLTRT")
      (footprint "eagle-import:QFN24-4X4-0P5-PAD")
      (libsource (lib "eagle-import") (part "SX1261"))
    )
    (comp (ref "U1071")
      (value "PE4259")
      (footprint "eagle-import:SC-70_6-LEAD_2X1MM25_0P65")
      (libsource (lib "eagle-import") (part "PE4259"))
    )
    (comp (ref "X1081")
      (value "ANTENNATINY")
      (footprint "eagle-import:SMA_UFL_PAD_TINY")
      (libsource (lib "eagle-import") (part "ANTENNATINY"))
    )
  )
  (nets
    (net (code "9") (name "+1V2_SMPS_PWR") (class "Default")
      (node (ref "C1421") (pin "1") (pinfunction "1_1") (pintype "passive"))
      (node (ref "C1501") (pin "1") (pinfunction "1_1") (pintype "passive"))
      (node (ref "L1411") (pin "1") (pinfunction "1_1") (pintype "passive"))
      (node (ref "U1411") (pin "2C") (pinfunction "VOS_2C") (pintype "passive"))
      (node (ref "U1511") (pin "5") (pinfunction "5_5") (pintype "passive"))
    )
    (net (code "10") (name "+3V3") (class "Default")
      (node (ref "C1321") (pin "1") (pinfunction "1_1") (pintype "passive"))
      (node (ref "C1401") (pin "1") (pinfunction "1_1") (pintype "passive"))
      (node (ref "C1502") (pin "1") (pinfunction "1_1") (pintype "passive"))
      (node (ref "C1601") (pin "1") (pinfunction "1_1") (pintype "passive"))
      (node (ref "C1701") (pin "1") (pinfunction "1_1") (pintype "passive"))
      (node (ref "L1311") (pin "1") (pinfunction "1_1") (pintype "passive"))
      (node (ref "R0201") (pin "2") (pinfunction "2_2") (pintype "passive"))
      (node (ref "R0401") (pin "1") (pinfunction "1_1") (pintype "passive"))
      (node (ref "R0421") (pin "1") (pinfunction "1_1") (pintype "passive"))
      (node (ref "U1311") (pin "5") (pinfunction "VOUT_5") (pintype "passive"))
      (node (ref "U1411") (pin "2A") (pinfunction "VIN_2A") (pintype "power_in"))
      (node (ref "U1511") (pin "1") (pinfunction "1_1") (pintype "passive"))
      (node (ref "U1511") (pin "8") (pinfunction "8_8") (pintype "power_in"))
      (node (ref "U1601") (pin "1") (pinfunction "1_1") (pintype "passive"))
      (node (ref "U1601") (pin "5") (pinfunction "5_5") (pintype "passive"))
      (node (ref "U1601") (pin "8") (pinfunction "8_8") (pintype "power_in"))
      (node (ref "U1701") (pin "1") (pinfunction "1_1") (pintype "passive"))
      (node (ref "U1701") (pin "5") (pinfunction "5_5") (pintype "passive"))
      (node (ref "U1701") (pin "8") (pinfunction "8_8") (pintype "power_in"))
      (node (ref "U1801") (pin "5") (pinfunction "5_5") (pintype "passive"))
      (node (ref "X0201") (pin "1") (pinfunction "1_1") (pintype "passive"))
      (node (ref "X0222") (pin "1") (pinfunction "1_1") (pintype "passive"))
      (node (ref "X2151") (pin "3") (pinfunction "3_3") (pintype "passive"))
      (node (ref "X2151") (pin "9") (pinfunction "9_9") (pintype "passive"))
    )
    (net (code "11") (name "+3V3_BRIDGE_PWR") (class "Default")
      (node (ref "C1802") (pin "1") (pinfunction "1_1") (pintype "passive"))
      (node (ref "C1901") (pin "1") (pinfunction "1_1") (pintype "passive"))
      (node (ref "R1905") (pin "2") (pinfunction "2_2") (pintype "passive"))
      (node (ref "R1906") (pin "2") (pinfunction "2_2") (pintype "passive"))
      (node (ref "TP_+3V3_BRIDGES") (pin "TP") (pinfunction "TP_TP") (pintype "input"))
      (node (ref "U1801") (pin "6") (pinfunction "6_6") (pintype "passive"))
      (node (ref "U1911") (pin "8") (pinfunction "8_8") (pintype "power_in"))
      (node (ref "U1912") (pin "8") (pinfunction "8_8") (pintype "power_in"))
      (node (ref "U1921") (pin "8") (pinfunction "8_8") (pintype "power_in"))
      (node (ref "U1922") (pin "8") (pinfunction "8_8") (pintype "power_in"))
      (node (ref "X2151") (pin "4") (pinfunction "4_4") (pintype "passive"))
    )
    (net (code "12") (name "+3V3_HICUR") (class "Default")
      (node (ref "X2111") (pin "1") (pinfunction "1_1") (pintype "passive"))
      (node (ref "X2111") (pin "5") (pinfunction "5_5") (pintype "passive"))
      (node (ref "X2112") (pin "1") (pinfunction "1_1") (pintype "passive"))
      (node (ref "X2112") (pin "5") (pinfunction "5_5") (pintype "passive"))
    )
    (net (code "13") (name "+3V3_I2C1_PWR") (class "Default")
      (node (ref "C0601") (pin "2") (pinfunction "2_2") (pintype "passive"))
      (node (ref "C0701") (pin "1") (pinfunction "1_1") (pintype "passive"))
      (node (ref "C0702") (pin "1") (pinfunction "1_1") (pintype "passive"))
      (node (ref "C0751") (pin "1") (pinfunction "1_1") (pintype "passive"))
      (node (ref "C0801") (pin "1") (pinfunction "1_1") (pintype "passive"))
      (node (ref "C1113") (pin "1") (pinfunction "1_1") (pintype "passive"))
      (node (ref "C1521") (pin "1") (pinfunction "1_1") (pintype "passive"))
      (node (ref "R0511") (pin "2") (pinfunction "2_2") (pintype "passive"))
      (node (ref "R0512") (pin "2") (pinfunction "2_2") (pintype "passive"))
      (node (ref "R0802") (pin "2") (pinfunction "2_2") (pintype "passive"))
      (node (ref "R1112") (pin "2") (pinfunction "2_2") (pintype "passive"))
      (node (ref "TP_+3V3_I2C1") (pin "TP") (pinfunction "TP_TP") (pintype "input"))
      (node (ref "U0611") (pin "8") (pinfunction "VCC_8") (pintype "power_in"))
      (node (ref "U0711") (pin "15") (pinfunction "DVDD_15") (pintype "power_in"))
      (node (ref "U0711") (pin "16") (pinfunction "AVDD_16") (pintype "power_in"))
      (node (ref "U0751") (pin "1") (pinfunction "IN_1") (pintype "power_in"))
      (node (ref "U0811") (pin "2") (pinfunction "VDD_I2C_2") (pintype "power_in"))
      (node (ref "U0811") (pin "24") (pinfunction "VDD_P_24") (pintype "power_in"))
      (node (ref "U1111") (pin "2") (pinfunction "VDD_I2C_2") (pintype "power_in"))
      (node (ref "U1111") (pin "21") (pinfunction "ADDR_21") (pintype "input"))
      (node (ref "U1111") (pin "24") (pinfunction "VDD_P_24") (pintype "power_in"))
      (node (ref "U1511") (pin "2") (pinfunction "2_2") (pintype "passive"))
      (node (ref "X2151") (pin "6") (pinfunction "6_6") (pintype "passive"))
    )
    (net (code "14") (name "+3V3_SPI3_PWR") (class "Default")
      (node (ref "C0901") (pin "1") (pinfunction "1_1") (pintype "passive"))
      (node (ref "C0902") (pin "1") (pinfunction "1_1") (pintype "passive"))
      (node (ref "C1001") (pin "1") (pinfunction "1_1") (pintype "passive"))
      (node (ref "C1002") (pin "1") (pinfunction "1_1") (pintype "passive"))
      (node (ref "R0931") (pin "2") (pinfunction "2_2") (pintype "passive"))
      (node (ref "R0932") (pin "2") (pinfunction "2_2") (pintype "passive"))
      (node (ref "R1071") (pin "2") (pinfunction "2_2") (pintype "passive"))
      (node (ref "TP_+3V3_SPI3") (pin "TP") (pinfunction "TP_TP") (pintype "input"))
      (node (ref "U0911") (pin "28") (pinfunction "VDDIO_28") (pintype "power_in"))
      (node (ref "U0911") (pin "3") (pinfunction "VDD_3") (pintype "power_in"))
      (node (ref "U0911") (pin "5") (pinfunction "PS1_5") (pintype "input"))
      (node (ref "U1001") (pin "10") (pinfunction "VBAT_10") (pintype "power_in"))
      (node (ref "U1001") (pin "11") (pinfunction "VBAT_IO_11") (pintype "power_in"))
      (node (ref "U1601") (pin "2") (pinfunction "2_2") (pintype "passive"))
      (node (ref "U1601") (pin "6") (pinfunction "6_6") (pintype "passive"))
      (node (ref "X2151") (pin "5") (pinfunction "5_5") (pintype "passive"))
    )
    (net (code "15") (name "+3V3_USART1_PWR") (class "Default")
      (node (ref "C1201") (pin "1") (pinfunction "1_1") (pintype "passive"))
      (node (ref "C1202") (pin "1") (pinfunction "1_1") (pintype "passive"))
      (node (ref "TP_+3V3_USART1") (pin "TP") (pinfunction "TP_TP") (pintype "input"))
      (node (ref "U1211") (pin "8") (pinfunction "VCC_8") (pintype "power_in"))
      (node (ref "U1701") (pin "2") (pinfunction "2_2") (pintype "passive"))
      (node (ref "U1701") (pin "6") (pinfunction "6_6") (pintype "passive"))
    )
    (net (code "16") (name "+BAT_VOLTAGE_PWR") (class "Default")
      (node (ref "R0462") (pin "2") (pinfunction "2_2") (pintype "passive"))
      (node (ref "TP_BAT_VOLTAGE") (pin "TP") (pinfunction "TP_TP") (pintype "input"))
      (node (ref "U1801") (pin "2") (pinfunction "2_2") (pintype "passive"))
      (node (ref "X2151") (pin "2") (pinfunction "2_2") (pintype "passive"))
    )
    (net (code "22") (name "ADC_VIN1N") (class "Default")
      (node (ref "C0722") (pin "1") (pinfunction "1_1") (pintype "passive"))
      (node (ref "R1902") (pin "1") (pinfunction "1_1") (pintype "passive"))
      (node (ref "U0711") (pin "2") (pinfunction "VIN1N_2") (pintype "passive"))
      (node (ref "U1911") (pin "6") (pinfunction "6_6") (pintype "passive"))
      (node (ref "U1912") (pin "6") (pinfunction "6_6") (pintype "passive"))
    )
    (net (code "23") (name "ADC_VIN1P") (class "Default")
      (node (ref "C0721") (pin "1") (pinfunction "1_1") (pintype "passive"))
      (node (ref "R1901") (pin "1") (pinfunction "1_1") (pintype "passive"))
      (node (ref "R1905") (pin "1") (pinfunction "1_1") (pintype "passive"))
      (node (ref "U0711") (pin "3") (pinfunction "VIN1P_3") (pintype "passive"))
      (node (ref "U1911") (pin "2") (pinfunction "2_2") (pintype "passive"))
      (node (ref "U1912") (pin "2") (pinfunction "2_2") (pintype "passive"))
    )
    (net (code "24") (name "ADC_VIN2N") (class "Default")
      (node (ref "C0724") (pin "1") (pinfunction "1_1") (pintype "passive"))
      (node (ref "R1904") (pin "2") (pinfunction "2_2") (pintype "passive"))
      (node (ref "U0711") (pin "4") (pinfunction "VIN2N_4") (pintype "passive"))
      (node (ref "U1921") (pin "6") (pinfunction "6_6") (pintype "passive"))
      (node (ref "U1922") (pin "6") (pinfunction "6_6") (pintype "passive"))
    )
    (net (code "25") (name "ADC_VIN2P") (class "Default")
      (node (ref "C0723") (pin "1") (pinfunction "1_1") (pintype "passive"))
      (node (ref "R1903") (pin "2") (pinfunction "2_2") (pintype "passive"))
      (node (ref "R1906") (pin "1") (pinfunction "1_1") (pintype "passive"))
      (node (ref "U0711") (pin "5") (pinfunction "VIN2P_5") (pintype "passive"))
      (node (ref "U1921") (pin "2") (pinfunction "2_2") (pintype "passive"))
      (node (ref "U1922") (pin "2") (pinfunction "2_2") (pintype "passive"))
    )
    (net (code "26") (name "ANT_LORA") (class "Default")
      (node (ref "C1083") (pin "2") (pinfunction "2_2") (pintype "passive"))
      (node (ref "L1082") (pin "1") (pinfunction "1_1") (pintype "passive"))
      (node (ref "X1081") (pin "ANT1") (pinfunction "SIGNAL_ANT1") (pintype "bidirectional"))
      (node (ref "X1081") (pin "ANT2") (pinfunction "SIGNAL_ANT2") (pintype "bidirectional"))
      (node (ref "X1081") (pin "ANT3") (pinfunction "SIGNAL_ANT3") (pintype "bidirectional"))
    )
    (net (code "27") (name "BNO_CAP") (class "Default")
      (node (ref "C0903") (pin "1") (pinfunction "1_1") (pintype "passive"))
      (node (ref "U0911") (pin "9") (pinfunction "CAP_9") (pintype "passive"))
    )
    (net (code "28") (name "BNO_ENV_SCL") (class "Default")
      (node (ref "R0932") (pin "1") (pinfunction "1_1") (pintype "passive"))
      (node (ref "U0911") (pin "15") (pinfunction "ENV_SCL_15") (pintype "bidirectional"))
    )
    (net (code "29") (name "BNO_ENV_SDA") (class "Default")
      (node (ref "R0931") (pin "1") (pinfunction "1_1") (pintype "passive"))
      (node (ref "U0911") (pin "16") (pinfunction "ENV_SDA_16") (pintype "bidirectional"))
    )
    (net (code "30") (name "BNO_H_CSN") (class "Default")
      (node (ref "R0904") (pin "2") (pinfunction "2_2") (pintype "passive"))
      (node (ref "U0911") (pin "18") (pinfunction "H_CSN_18") (pintype "input"))
    )
    (net (code "31") (name "BNO_INTN") (class "Default")
      (node (ref "R0902") (pin "2") (pinfunction "2_2") (pintype "passive"))
      (node (ref "U0911") (pin "14") (pinfunction "H_INTN_14") (pintype "output"))
    )
    (net (code "32") (name "BNO_MISO") (class "Default")
      (node (ref "R0901") (pin "2") (pinfunction "2_2") (pintype "passive"))
      (node (ref "U0911") (pin "20") (pinfunction "H_SDA/MISO/TX_20") (pintype "bidirectional"))
    )
    (net (code "33") (name "BNO_PS0_WAKE") (class "Default")
      (node (ref "R0903") (pin "2") (pinfunction "2_2") (pintype "passive"))
      (node (ref "U0911") (pin "6") (pinfunction "PS0/WAKE_6") (pintype "input"))
    )
    (net (code "34") (name "BRIDGE_N1") (class "Default")
      (node (ref "R1961") (pin "2") (pinfunction "2_2") (pintype "passive"))
      (node (ref "X2111") (pin "3") (pinfunction "3_3") (pintype "passive"))
    )
    (net (code "35") (name "BRIDGE_N2") (class "Default")
      (node (ref "R1971") (pin "1") (pinfunction "1_1") (pintype "passive"))
      (node (ref "X2111") (pin "7") (pinfunction "7_7") (pintype "passive"))
    )
    (net (code "36") (name "BRIDGE_N3") (class "Default")
      (node (ref "R1962") (pin "2") (pinfunction "2_2") (pintype "passive"))
      (node (ref "X2112") (pin "3") (pinfunction "3_3") (pintype "passive"))
    )
    (net (code "37") (name "BRIDGE_N4") (class "Default")
      (node (ref "R1972") (pin "1") (pinfunction "1_1") (pintype "passive"))
      (node (ref "X2112") (pin "7") (pinfunction "7_7") (pintype "passive"))
    )
    (net (code "38") (name "BRIDGE_P1") (class "Default")
      (node (ref "R1911") (pin "2") (pinfunction "2_2") (pintype "passive"))
      (node (ref "X2111") (pin "2") (pinfunction "2_2") (pintype "passive"))
    )
    (net (code "39") (name "BRIDGE_P2") (class "Default")
      (node (ref "R1921") (pin "1") (pinfunction "1_1") (pintype "passive"))
      (node (ref "X2111") (pin "6") (pinfunction "6_6") (pintype "passive"))
    )
    (net (code "40") (name "BRIDGE_P3") (class "Default")
      (node (ref "R1912") (pin "2") (pinfunction "2_2") (pintype "passive"))
      (node (ref "X2112") (pin "2") (pinfunction "2_2") (pintype "passive"))
    )
    (net (code "41") (name "BRIDGE_P4") (class "Default")
      (node (ref "R1922") (pin "1") (pinfunction "1_1") (pintype "passive"))
      (node (ref "X2112") (pin "6") (pinfunction "6_6") (pintype "passive"))
    )
    (net (code "42") (name "BUZZER") (class "Default")
      (node (ref "BUZZER+") (pin "1") (pinfunction "P_1") (pintype "passive"))
      (node (ref "R2021") (pin "1") (pinfunction "1_1") (pintype "passive"))
    )
    (net (code "43") (name "ESP_CTS") (class "Default")
      (node (ref "R1257") (pin "1") (pinfunction "1_1") (pintype "passive"))
      (node (ref "U1211") (pin "7") (pinfunction "GPIO13_UART0_CTS_7") (pintype "bidirectional"))
    )
    (net (code "44") (name "ESP_RTS") (class "Default")
      (node (ref "R1266") (pin "1") (pinfunction "1_1") (pintype "passive"))
      (node (ref "U1211") (pin "16") (pinfunction "GPIO15_UART0_RTS_16") (pintype "bidirectional"))
    )
    (net (code "45") (name "ESP_RX") (class "Default")
      (node (ref "R1271") (pin "1") (pinfunction "1_1") (pintype "passive"))
      (node (ref "U1211") (pin "21") (pinfunction "RXD_21") (pintype "input"))
    )
    (net (code "46") (name "ESP_TX") (class "Default")
      (node (ref "R1272") (pin "1") (pinfunction "1_1") (pintype "passive"))
      (node (ref "U1211") (pin "22") (pinfunction "TXD_22") (pintype "output"))
    )
    (net (code "47") (name "EXTI9_I2C1_ADC_DRDY") (class "Default")
      (node (ref "R0731") (pin "2") (pinfunction "2_2") (pintype "passive"))
      (node (ref "U0711") (pin "12") (pinfunction "DRDY_12") (pintype "output"))
    )
    (net (code "48") (name "GND") (class "Default")
      (node (ref "BUZZER-") (pin "1") (pinfunction "P_1") (pintype "passive"))
      (node (ref "C0213") (pin "2") (pinfunction "2_2") (pintype "passive"))
      (node (ref "C0311") (pin "2") (pinfunction "2_2") (pintype "passive"))
      (node (ref "C0331") (pin "+") (pinfunction "A_+") (pintype "passive"))
      (node (ref "C0332") (pin "2") (pinfunction "2_2") (pintype "passive"))
      (node (ref "C0401") (pin "2") (pinfunction "2_2") (pintype "passive"))
      (node (ref "C0402") (pin "2") (pinfunction "2_2") (pintype "passive"))
      (node (ref "C0403") (pin "2") (pinfunction "2_2") (pintype "passive"))
      (node (ref "C0410") (pin "1") (pinfunction "1_1") (pintype "passive"))
      (node (ref "C0412") (pin "2") (pinfunction "2_2") (pintype "passive"))
      (node (ref "C0413") (pin "2") (pinfunction "2_2") (pintype "passive"))
      (node (ref "C0451") (pin "2") (pinfunction "2_2") (pintype "passive"))
      (node (ref "C0461") (pin "2") (pinfunction "2_2") (pintype "passive"))
      (node (ref "C0601") (pin "1") (pinfunction "1_1") (pintype "passive"))
      (node (ref "C0701") (pin "2") (pinfunction "2_2") (pintype "passive"))
      (node (ref "C0702") (pin "2") (pinfunction "2_2") (pintype "passive"))
      (node (ref "C0711") (pin "2") (pinfunction "2_2") (pintype "passive"))
      (node (ref "C0721") (pin "2") (pinfunction "2_2") (pintype "passive"))
      (node (ref "C0722") (pin "2") (pinfunction "2_2") (pintype "passive"))
      (node (ref "C0723") (pin "2") (pinfunction "2_2") (pintype "passive"))
      (node (ref "C0724") (pin "2") (pinfunction "2_2") (pintype "passive"))
      (node (ref "C0751") (pin "2") (pinfunction "2_2") (pintype "passive"))
      (node (ref "C0752") (pin "2") (pinfunction "2_2") (pintype "passive"))
      (node (ref "C0801") (pin "2") (pinfunction "2_2") (pintype "passive"))
      (node (ref "C0901") (pin "2") (pinfunction "2_2") (pintype "passive"))
      (node (ref "C0902") (pin "2") (pinfunction "2_2") (pintype "passive"))
      (node (ref "C0903") (pin "2") (pinfunction "2_2") (pintype "passive"))
      (node (ref "C0921") (pin "2") (pinfunction "2_2") (pintype "passive"))
      (node (ref "C0922") (pin "2") (pinfunction "2_2") (pintype "passive"))
      (node (ref "C1001") (pin "2") (pinfunction "2_2") (pintype "passive"))
      (node (ref "C1002") (pin "2") (pinfunction "2_2") (pintype "passive"))
      (node (ref "C1003") (pin "2") (pinfunction "2_2") (pintype "passive"))
      (node (ref "C1004") (pin "2") (pinfunction "2_2") (pintype "passive"))
      (node (ref "C1005") (pin "2") (pinfunction "2_2") (pintype "passive"))
      (node (ref "C1065") (pin "1") (pinfunction "1_1") (pintype "passive"))
      (node (ref "C1066") (pin "2") (pinfunction "2_2") (pintype "passive"))
      (node (ref "C1067") (pin "2") (pinfunction "2_2") (pintype "passive"))
      (node (ref "C1071") (pin "2") (pinfunction "2_2") (pintype "passive"))
      (node (ref "C1072") (pin "2") (pinfunction "2_2") (pintype "passive"))
      (node (ref "C1082") (pin "1") (pinfunction "1_1") (pintype "passive"))
      (node (ref "C1083") (pin "1") (pinfunction "1_1") (pintype "passive"))
      (node (ref "C1091") (pin "1") (pinfunction "1_1") (pintype "passive"))
      (node (ref "C1093") (pin "1") (pinfunction "1_1") (pintype "passive"))
      (node (ref "C1113") (pin "2") (pinfunction "2_2") (pintype "passive"))
      (node (ref "C1201") (pin "2") (pinfunction "2_2") (pintype "passive"))
      (node (ref "C1202") (pin "2") (pinfunction "2_2") (pintype "passive"))
      (node (ref "C1301") (pin "2") (pinfunction "2_2") (pintype "passive"))
      (node (ref "C1321") (pin "2") (pinfunction "2_2") (pintype "passive"))
      (node (ref "C1401") (pin "2") (pinfunction "2_2") (pintype "passive"))
      (node (ref "C1421") (pin "2") (pinfunction "2_2") (pintype "passive"))
      (node (ref "C1501") (pin "2") (pinfunction "2_2") (pintype "passive"))
      (node (ref "C1502") (pin "2") (pinfunction "2_2") (pintype "passive"))
      (node (ref "C1521") (pin "2") (pinfunction "2_2") (pintype "passive"))
      (node (ref "C1591") (pin "1") (pinfunction "1_1") (pintype "passive"))
      (node (ref "C1592") (pin "2") (pinfunction "2_2") (pintype "passive"))
      (node (ref "C1601") (pin "2") (pinfunction "2_2") (pintype "passive"))
      (node (ref "C1701") (pin "2") (pinfunction "2_2") (pintype "passive"))
      (node (ref "C1801") (pin "2") (pinfunction "2_2") (pintype "passive"))
      (node (ref "C1802") (pin "2") (pinfunction "2_2") (pintype "passive"))
      (node (ref "C1901") (pin "2") (pinfunction "2_2") (pintype "passive"))
      (node (ref "C1911") (pin "2") (pinfunction "2_2") (pintype "passive"))
      (node (ref "C1912") (pin "2") (pinfunction "2_2") (pintype "passive"))
      (node (ref "C1921") (pin "2") (pinfunction "2_2") (pintype "passive"))
      (node (ref "C1922") (pin "2") (pinfunction "2_2") (pintype "passive"))
      (node (ref "C1961") (pin "2") (pinfunction "2_2") (pintype "passive"))
      (node (ref "C1962") (pin "2") (pinfunction "2_2") (pintype "passive"))
      (node (ref "C1971") (pin "2") (pinfunction "2_2") (pintype "passive"))
      (node (ref "C1972") (pin "2") (pinfunction "2_2") (pintype "passive"))
      (node (ref "C2011") (pin "2") (pinfunction "2_2") (pintype "passive"))
      (node (ref "C2021") (pin "2") (pinfunction "2_2") (pintype "passive"))
      (node (ref "C2032") (pin "2") (pinfunction "2_2") (pintype "passive"))
      (node (ref "H2211") (pin "B2,8") (pinfunction "MOUNT_B2,8") (pintype "passive"))
      (node (ref "H2221") (pin "B2,8") (pinfunction "MOUNT_B2,8") (pintype "passive"))
      (node (ref "H2231") (pin "B2,8") (pinfunction "MOUNT_B2,8") (pintype "passive"))
      (node (ref "H2241") (pin "B2,8") (pinfunction "MOUNT_B2,8") (pintype "passive"))
      (node (ref "Q1011") (pin "2") (pinfunction "3_2") (pintype "passive"))
      (node (ref "Q1011") (pin "4") (pinfunction "3_4") (pintype "passive"))
      (node (ref "R0202") (pin "1") (pinfunction "1_1") (pintype "passive"))
      (node (ref "R0221") (pin "1") (pinfunction "1_1") (pintype "passive"))
      (node (ref "R0441") (pin "1") (pinfunction "1_1") (pintype "passive"))
      (node (ref "R0461") (pin "1") (pinfunction "1_1") (pintype "passive"))
      (node (ref "S0212") (pin "1") (pinfunction "P_1") (pintype "passive"))
      (node (ref "S2031") (pin "2") (pinfunction "2_2") (pintype "passive"))
      (node (ref "U0101") (pin "18") (pinfunction "VSS_18") (pintype "passive"))
      (node (ref "U0101") (pin "31") (pinfunction "VSS_31") (pintype "passive"))
      (node (ref "U0101") (pin "47") (pinfunction "VSS_47") (pintype "passive"))
      (node (ref "U0101") (pin "63") (pinfunction "VSS_63") (pintype "passive"))
      (node (ref "U0611") (pin "1") (pinfunction "A0_1") (pintype "input"))
      (node (ref "U0611") (pin "2") (pinfunction "A1_2") (pintype "input"))
      (node (ref "U0611") (pin "3") (pinfunction "A2_3") (pintype "input"))
      (node (ref "U0611") (pin "4") (pinfunction "VSS_4") (pintype "power_in"))
      (node (ref "U0611") (pin "7") (pinfunction "WP_7") (pintype "input"))
      (node (ref "U0711") (pin "7") (pinfunction "REFN_7") (pintype "passive"))
      (node (ref "U0711") (pin "8") (pinfunction "AVSS_8") (pintype "passive"))
      (node (ref "U0711") (pin "9") (pinfunction "DVSS_9") (pintype "passive"))
      (node (ref "U0751") (pin "2") (pinfunction "GND_2") (pintype "passive"))
      (node (ref "U0811") (pin "12") (pinfunction "VSS_12") (pintype "passive"))
      (node (ref "U0811") (pin "21") (pinfunction "ADDR_21") (pintype "input"))
      (node (ref "U0911") (pin "10") (pinfunction "CLKSEL0_10") (pintype "input"))
      (node (ref "U0911") (pin "2") (pinfunction "VSS_2") (pintype "passive"))
      (node (ref "U0911") (pin "25") (pinfunction "VSSIO_25") (pintype "passive"))
      (node (ref "U1001") (pin "2") (pinfunction "VSS_2") (pintype "passive"))
      (node (ref "U1001") (pin "20") (pinfunction "VSS_20") (pintype "passive"))
      (node (ref "U1001") (pin "25") (pinfunction "VSS_25") (pintype "passive"))
      (node (ref "U1001") (pin "5") (pinfunction "VSS_5") (pintype "passive"))
      (node (ref "U1001") (pin "8") (pinfunction "VSS_8") (pintype "passive"))
      (node (ref "U1071") (pin "2") (pinfunction "GND_2") (pintype "power_in"))
      (node (ref "U1111") (pin "12") (pinfunction "VSS_12") (pintype "passive"))
      (node (ref "U1211") (pin "15") (pinfunction "VSS_15") (pintype "passive"))
      (node (ref "U1211") (pin "2") (pinfunction "ADC_2") (pintype "passive"))
      (node (ref "U1311") (pin "13") (pinfunction "VSS_13") (pintype "passive"))
      (node (ref "U1311") (pin "14") (pinfunction "VSS_14") (pintype "passive"))
      (node (ref "U1311") (pin "3") (pinfunction "VSS_3") (pintype "passive"))
      (node (ref "U1311") (pin "4") (pinfunction "EN_VIN_SW_4") (pintype "input"))
      (node (ref "U1311") (pin "G1") (pinfunction "VSS_G1") (pintype "passive"))
      (node (ref "U1311") (pin "G2") (pinfunction "VSS_G2") (pintype "passive"))
      (node (ref "U1311") (pin "G3") (pinfunction "VSS_G3") (pintype "passive"))
      (node (ref "U1411") (pin "1C") (pinfunction "VSEL1_1C") (pintype "input"))
      (node (ref "U1411") (pin "1D") (pinfunction "VSEL2_1D") (pintype "input"))
      (node (ref "U1411") (pin "2B") (pinfunction "VSS_2B") (pintype "passive"))
      (node (ref "U1411") (pin "2D") (pinfunction "VSEL3_2D") (pintype "input"))
      (node (ref "U1511") (pin "4") (pinfunction "4_4") (pintype "passive"))
      (node (ref "U1601") (pin "4") (pinfunction "4_4") (pintype "passive"))
      (node (ref "U1701") (pin "4") (pinfunction "4_4") (pintype "passive"))
      (node (ref "U1801") (pin "4") (pinfunction "4_4") (pintype "passive"))
      (node (ref "U1911") (pin "4") (pinfunction "4_4") (pintype "passive"))
      (node (ref "U1912") (pin "4") (pinfunction "4_4") (pintype "passive"))
      (node (ref "U1921") (pin "4") (pinfunction "4_4") (pintype "passive"))
      (node (ref "U1922") (pin "4") (pinfunction "4_4") (pintype "passive"))
      (node (ref "VIN-") (pin "1") (pinfunction "P_1") (pintype "passive"))
      (node (ref "X0201") (pin "3") (pinfunction "3_3") (pintype "passive"))
      (node (ref "X0201") (pin "5") (pinfunction "5_5") (pintype "passive"))
      (node (ref "X0201") (pin "9") (pinfunction "9_9") (pintype "passive"))
      (node (ref "X1081") (pin "GND1") (pinfunction "GND_GND1") (pintype "bidirectional"))
      (node (ref "X1081") (pin "GND2") (pinfunction "GND_GND2") (pintype "bidirectional"))
      (node (ref "X1081") (pin "GND3") (pinfunction "GND_GND3") (pintype "bidirectional"))
      (node (ref "X1081") (pin "GND4") (pinfunction "GND_GND4") (pintype "bidirectional"))
      (node (ref "X2111") (pin "4") (pinfunction "4_4") (pintype "passive"))
      (node (ref "X2111") (pin "8") (pinfunction "8_8") (pintype "passive"))
      (node (ref "X2112") (pin "4") (pinfunction "4_4") (pintype "passive"))
      (node (ref "X2112") (pin "8") (pinfunction "8_8") (pintype "passive"))
      (node (ref "X2151") (pin "10") (pinfunction "10_10") (pintype "passive"))
      (node (ref "X2152") (pin "10") (pinfunction "10_10") (pintype "passive"))
      (node (ref "X2153") (pin "10") (pinfunction "10_10") (pintype "passive"))
    )
    (net (code "49") (name "MCU_NRST") (class "Default")
      (node (ref "C0213") (pin "1") (pinfunction "1_1") (pintype "passive"))
      (node (ref "S0212") (pin "2") (pinfunction "S_2") (pintype "passive"))
      (node (ref "U0101") (pin "7") (pinfunction "NRST_7") (pintype "bidirectional"))
      (node (ref "X0201") (pin "10") (pinfunction "10_10") (pintype "passive"))
    )
    (net (code "50") (name "MCU_VBAT") (class "Default")
      (node (ref "C0451") (pin "1") (pinfunction "1_1") (pintype "passive"))
      (node (ref "TP_VBAT") (pin "TP") (pinfunction "TP_TP") (pintype "input"))
      (node (ref "U0101") (pin "1") (pinfunction "VBAT_1") (pintype "power_in"))
    )
    (net (code "51") (name "MCU_VDD") (class "Default")
      (node (ref "C0401") (pin "1") (pinfunction "1_1") (pintype "passive"))
      (node (ref "C0402") (pin "1") (pinfunction "1_1") (pintype "passive"))
      (node (ref "C0403") (pin "1") (pinfunction "1_1") (pintype "passive"))
      (node (ref "C0410") (pin "2") (pinfunction "2_2") (pintype "passive"))
      (node (ref "L0411") (pin "1") (pinfunction "1_1") (pintype "passive"))
      (node (ref "R0401") (pin "2") (pinfunction "2_2") (pintype "passive"))
      (node (ref "U0101") (pin "19") (pinfunction "VDD_19") (pintype "power_in"))
      (node (ref "U0101") (pin "32") (pinfunction "VDD_32") (pintype "power_in"))
      (node (ref "U0101") (pin "64") (pinfunction "VDD_64") (pintype "power_in"))
    )
    (net (code "52") (name "MCU_VDD12") (class "Default")
      (node (ref "C1591") (pin "2") (pinfunction "2_2") (pintype "passive"))
      (node (ref "C1592") (pin "1") (pinfunction "1_1") (pintype "passive"))
      (node (ref "TP_+1V2_MCU") (pin "TP") (pinfunction "TP_TP") (pintype "input"))
      (node (ref "U0101") (pin "30") (pinfunction "VDD12_30") (pintype "power_in"))
      (node (ref "U0101") (pin "62") (pinfunction "VDD12_62") (pintype "power_in"))
      (node (ref "U1511") (pin "6") (pinfunction "6_6") (pintype "passive"))
    )
    (net (code "53") (name "MCU_VDDA") (class "Default")
      (node (ref "C0412") (pin "1") (pinfunction "1_1") (pintype "passive"))
      (node (ref "C0413") (pin "1") (pinfunction "1_1") (pintype "passive"))
      (node (ref "L0411") (pin "2") (pinfunction "2_2") (pintype "passive"))
      (node (ref "U0101") (pin "13") (pinfunction "VDDA_VREF_P_13") (pintype "power_in"))
    )
    (net (code "54") (name "MCU_VREF_M") (class "Default")
      (node (ref "R0441") (pin "2") (pinfunction "2_2") (pintype "passive"))
      (node (ref "U0101") (pin "12") (pinfunction "VSSA_VREF_M_12") (pintype "passive"))
    )
    (net (code "55") (name "Net-(C1063-Pad2)") (class "Default")
      (node (ref "C1063") (pin "2") (pinfunction "2_2") (pintype "passive"))
      (node (ref "C1064") (pin "1") (pinfunction "1_1") (pintype "passive"))
      (node (ref "C1066") (pin "1") (pinfunction "1_1") (pintype "passive"))
      (node (ref "L1063") (pin "1") (pinfunction "1_1") (pintype "passive"))
    )
    (net (code "56") (name "Net-(C1064-Pad2)") (class "Default")
      (node (ref "C1064") (pin "2") (pinfunction "2_2") (pintype "passive"))
      (node (ref "L1064") (pin "2") (pinfunction "2_2") (pintype "passive"))
    )
    (net (code "57") (name "Net-(C1081-Pad2)") (class "Default")
      (node (ref "C1081") (pin "2") (pinfunction "2_2") (pintype "passive"))
      (node (ref "C1082") (pin "2") (pinfunction "2_2") (pintype "passive"))
      (node (ref "L1082") (pin "2") (pinfunction "2_2") (pintype "passive"))
    )
    (net (code "58") (name "Net-(C1911-Pad1)") (class "Default")
      (node (ref "C1911") (pin "1") (pinfunction "1_1") (pintype "passive"))
      (node (ref "L1911") (pin "1") (pinfunction "1_1") (pintype "passive"))
      (node (ref "R1901") (pin "2") (pinfunction "2_2") (pintype "passive"))
      (node (ref "U1911") (pin "1") (pinfunction "1_1") (pintype "passive"))
    )
    (net (code "59") (name "Net-(C1912-Pad1)") (class "Default")
      (node (ref "C1912") (pin "1") (pinfunction "1_1") (pintype "passive"))
      (node (ref "L1912") (pin "1") (pinfunction "1_1") (pintype "passive"))
      (node (ref "U1912") (pin "1") (pinfunction "1_1") (pintype "passive"))
    )
    (net (code "60") (name "Net-(C1921-Pad1)") (class "Default")
      (node (ref "C1921") (pin "1") (pinfunction "1_1") (pintype "passive"))
      (node (ref "L1921") (pin "2") (pinfunction "2_2") (pintype "passive"))
      (node (ref "R1903") (pin "1") (pinfunction "1_1") (pintype "passive"))
      (node (ref "U1921") (pin "1") (pinfunction "1_1") (pintype "passive"))
    )
    (net (code "61") (name "Net-(C1922-Pad1)") (class "Default")
      (node (ref "C1922") (pin "1") (pinfunction "1_1") (pintype "passive"))
      (node (ref "L1922") (pin "2") (pinfunction "2_2") (pintype "passive"))
      (node (ref "U1922") (pin "1") (pinfunction "1_1") (pintype "passive"))
    )
    (net (code "62") (name "Net-(C1961-Pad1)") (class "Default")
      (node (ref "C1961") (pin "1") (pinfunction "1_1") (pintype "passive"))
      (node (ref "L1961") (pin "1") (pinfunction "1_1") (pintype "passive"))
      (node (ref "R1902") (pin "2") (pinfunction "2_2") (pintype "passive"))
      (node (ref "U1911") (pin "5") (pinfunction "5_5") (pintype "passive"))
    )
    (net (code "63") (name "Net-(C1962-Pad1)") (class "Default")
      (node (ref "C1962") (pin "1") (pinfunction "1_1") (pintype "passive"))
      (node (ref "L1962") (pin "1") (pinfunction "1_1") (pintype "passive"))
      (node (ref "U1912") (pin "5") (pinfunction "5_5") (pintype "passive"))
    )
    (net (code "64") (name "Net-(C1971-Pad1)") (class "Default")
      (node (ref "C1971") (pin "1") (pinfunction "1_1") (pintype "passive"))
      (node (ref "L1971") (pin "2") (pinfunction "2_2") (pintype "passive"))
      (node (ref "R1904") (pin "1") (pinfunction "1_1") (pintype "passive"))
      (node (ref "U1921") (pin "5") (pinfunction "5_5") (pintype "passive"))
    )
    (net (code "65") (name "Net-(C1972-Pad1)") (class "Default")
      (node (ref "C1972") (pin "1") (pinfunction "1_1") (pintype "passive"))
      (node (ref "L1972") (pin "2") (pinfunction "2_2") (pintype "passive"))
      (node (ref "U1922") (pin "5") (pinfunction "5_5") (pintype "passive"))
    )
    (net (code "66") (name "Net-(D0901-PadA)") (class "Default")
      (node (ref "D0901") (pin "A") (pinfunction "A_A") (pintype "passive"))
      (node (ref "R0903") (pin "1") (pinfunction "1_1") (pintype "passive"))
    )
    (net (code "67") (name "Net-(L1911-Pad2)") (class "Default")
      (node (ref "L1911") (pin "2") (pinfunction "2_2") (pintype "passive"))
      (node (ref "R1911") (pin "1") (pinfunction "1_1") (pintype "passive"))
    )
    (net (code "68") (name "Net-(L1912-Pad2)") (class "Default")
      (node (ref "L1912") (pin "2") (pinfunction "2_2") (pintype "passive"))
      (node (ref "R1912") (pin "1") (pinfunction "1_1") (pintype "passive"))
    )
    (net (code "69") (name "Net-(L1921-Pad1)") (class "Default")
      (node (ref "L1921") (pin "1") (pinfunction "1_1") (pintype "passive"))
      (node (ref "R1921") (pin "2") (pinfunction "2_2") (pintype "passive"))
    )
    (net (code "70") (name "Net-(L1922-Pad1)") (class "Default")
      (node (ref "L1922") (pin "1") (pinfunction "1_1") (pintype "passive"))
      (node (ref "R1922") (pin "2") (pinfunction "2_2") (pintype "passive"))
    )
    (net (code "71") (name "Net-(L1961-Pad2)") (class "Default")
      (node (ref "L1961") (pin "2") (pinfunction "2_2") (pintype "passive"))
      (node (ref "R1961") (pin "1") (pinfunction "1_1") (pintype "passive"))
    )
    (net (code "72") (name "Net-(L1962-Pad2)") (class "Default")
      (node (ref "L1962") (pin "2") (pinfunction "2_2") (pintype "passive"))
      (node (ref "R1962") (pin "1") (pinfunction "1_1") (pintype "passive"))
    )
    (net (code "73") (name "Net-(L1971-Pad1)") (class "Default")
      (node (ref "L1971") (pin "1") (pinfunction "1_1") (pintype "passive"))
      (node (ref "R1971") (pin "2") (pinfunction "2_2") (pintype "passive"))
    )
    (net (code "74") (name "Net-(L1972-Pad1)") (class "Default")
      (node (ref "L1972") (pin "1") (pinfunction "1_1") (pintype "passive"))
      (node (ref "R1972") (pin "2") (pinfunction "2_2") (pintype "passive"))
    )
    (net (code "75") (name "Net-(Q1011-2)") (class "Default")
      (node (ref "Q1011") (pin "3") (pinfunction "2_3") (pintype "passive"))
      (node (ref "U1001") (pin "4") (pinfunction "XTB_4") (pintype "passive"))
    )
    (net (code "76") (name "Net-(R1990-Pad2)") (class "Default")
      (node (ref "R1990") (pin "2") (pinfunction "2_2") (pintype "passive"))
      (node (ref "U1911") (pin "3") (pinfunction "3_3") (pintype "input"))
      (node (ref "U1911") (pin "7") (pinfunction "7_7") (pintype "input"))
      (node (ref "U1921") (pin "3") (pinfunction "3_3") (pintype "input"))
      (node (ref "U1921") (pin "7") (pinfunction "7_7") (pintype "input"))
    )
    (net (code "77") (name "Net-(R1991-Pad2)") (class "Default")
      (node (ref "R1991") (pin "2") (pinfunction "2_2") (pintype "passive"))
      (node (ref "U1912") (pin "3") (pinfunction "3_3") (pintype "input"))
      (node (ref "U1912") (pin "7") (pinfunction "7_7") (pintype "input"))
      (node (ref "U1922") (pin "3") (pinfunction "3_3") (pintype "input"))
      (node (ref "U1922") (pin "7") (pinfunction "7_7") (pintype "input"))
    )
    (net (code "78") (name "Net-(U0711-VBG)") (class "Default")
      (node (ref "C0711") (pin "1") (pinfunction "1_1") (pintype "passive"))
      (node (ref "U0711") (pin "6") (pinfunction "VBG_6") (pintype "passive"))
    )
    (net (code "79") (name "Net-(U0811-~{INT})") (class "Default")
      (node (ref "R0811") (pin "2") (pinfunction "2_2") (pintype "passive"))
      (node (ref "U0811") (pin "1") (pinfunction "~{INT}_1") (pintype "output"))
    )
    (net (code "80") (name "Net-(U0811-~{RESET})") (class "Default")
      (node (ref "R0802") (pin "1") (pinfunction "1_1") (pintype "passive"))
      (node (ref "U0811") (pin "3") (pinfunction "~{RESET}_3") (pintype "input"))
    )
    (net (code "81") (name "Net-(U0911-CLKSEL1{slash}XOUT32)") (class "Default")
      (node (ref "C0922") (pin "1") (pinfunction "1_1") (pintype "passive"))
      (node (ref "Q0921") (pin "1") (pinfunction "1_1") (pintype "passive"))
      (node (ref "U0911") (pin "26") (pinfunction "CLKSEL1/XOUT32_26") (pintype "output"))
    )
    (net (code "82") (name "Net-(U0911-XIN32)") (class "Default")
      (node (ref "C0921") (pin "1") (pinfunction "1_1") (pintype "passive"))
      (node (ref "Q0921") (pin "2") (pinfunction "2_2") (pintype "passive"))
      (node (ref "U0911") (pin "27") (pinfunction "XIN32_27") (pintype "input"))
    )
    (net (code "83") (name "Net-(U1001-BUSY)") (class "Default")
      (node (ref "R1011") (pin "2") (pinfunction "2_2") (pintype "passive"))
      (node (ref "U1001") (pin "14") (pinfunction "BUSY_14") (pintype "bidirectional"))
    )
    (net (code "84") (name "Net-(U1001-DCC_SW)") (class "Default")
      (node (ref "L1001") (pin "1") (pinfunction "1_1") (pintype "passive"))
      (node (ref "U1001") (pin "9") (pinfunction "DCC_SW_9") (pintype "passive"))
    )
    (net (code "85") (name "Net-(U1001-DIO1)") (class "Default")
      (node (ref "R1053") (pin "1") (pinfunction "1_1") (pintype "passive"))
      (node (ref "TP_SX_DIO1") (pin "TP") (pinfunction "TP_TP") (pintype "input"))
      (node (ref "U1001") (pin "13") (pinfunction "DIO1_13") (pintype "bidirectional"))
    )
    (net (code "86") (name "Net-(U1001-DIO2)") (class "Default")
      (node (ref "R1052") (pin "1") (pinfunction "1_1") (pintype "passive"))
      (node (ref "TP_SX_DIO2") (pin "TP") (pinfunction "TP_TP") (pintype "input"))
      (node (ref "U1001") (pin "12") (pinfunction "DIO2_12") (pintype "bidirectional"))
    )
    (net (code "87") (name "Net-(U1001-DIO3)") (class "Default")
      (node (ref "R1051") (pin "1") (pinfunction "1_1") (pintype "passive"))
      (node (ref "TP_SX_DIO3") (pin "TP") (pinfunction "TP_TP") (pintype "input"))
      (node (ref "U1001") (pin "6") (pinfunction "DIO3_6") (pintype "bidirectional"))
    )
    (net (code "88") (name "Net-(U1001-MISO)") (class "Default")
      (node (ref "R1024") (pin "2") (pinfunction "2_2") (pintype "passive"))
      (node (ref "U1001") (pin "16") (pinfunction "MISO_16") (pintype "output"))
    )
    (net (code "89") (name "Net-(U1001-NSS)") (class "Default")
      (node (ref "R1021") (pin "2") (pinfunction "2_2") (pintype "passive"))
      (node (ref "U1001") (pin "19") (pinfunction "NSS_19") (pintype "input"))
    )
    (net (code "90") (name "Net-(U1001-RFI_N)") (class "Default")
      (node (ref "C1092") (pin "1") (pinfunction "1_1") (pintype "passive"))
      (node (ref "L1091") (pin "1") (pinfunction "1_1") (pintype "passive"))
      (node (ref "U1001") (pin "22") (pinfunction "RFI_N_22") (pintype "passive"))
    )
    (net (code "91") (name "Net-(U1001-RFI_P)") (class "Default")
      (node (ref "C1091") (pin "2") (pinfunction "2_2") (pintype "passive"))
      (node (ref "L1091") (pin "2") (pinfunction "2_2") (pintype "passive"))
      (node (ref "U1001") (pin "21") (pinfunction "RFI_P_21") (pintype "passive"))
    )
    (net (code "92") (name "Net-(U1001-RFO)") (class "Default")
      (node (ref "C1063") (pin "1") (pinfunction "1_1") (pintype "passive"))
      (node (ref "C1065") (pin "2") (pinfunction "2_2") (pintype "passive"))
      (node (ref "L1062") (pin "1") (pinfunction "1_1") (pintype "passive"))
      (node (ref "L1063") (pin "2") (pinfunction "2_2") (pintype "passive"))
      (node (ref "U1001") (pin "23") (pinfunction "RFO_23") (pintype "passive"))
    )
    (net (code "93") (name "Net-(U1001-VDD_IN)") (class "Default")
      (node (ref "L1002") (pin "1") (pinfunction "1_1") (pintype "passive"))
      (node (ref "U1001") (pin "1") (pinfunction "VDD_IN_1") (pintype "power_in"))
    )
    (net (code "94") (name "Net-(U1001-VREG)") (class "Default")
      (node (ref "C1003") (pin "1") (pinfunction "1_1") (pintype "passive"))
      (node (ref "L1001") (pin "2") (pinfunction "2_2") (pintype "passive"))
      (node (ref "L1002") (pin "2") (pinfunction "2_2") (pintype "passive"))
      (node (ref "U1001") (pin "7") (pinfunction "VREG_7") (pintype "power_in"))
    )
    (net (code "95") (name "Net-(U1001-VR_PA)") (class "Default")
      (node (ref "C1004") (pin "1") (pinfunction "1_1") (pintype "passive"))
      (node (ref "C1005") (pin "1") (pinfunction "1_1") (pintype "passive"))
      (node (ref "L1062") (pin "2") (pinfunction "2_2") (pintype "passive"))
      (node (ref "U1001") (pin "24") (pinfunction "VR_PA_24") (pintype "power_in"))
    )
    (net (code "96") (name "Net-(U1001-XTA)") (class "Default")
      (node (ref "Q1011") (pin "1") (pinfunction "1_1") (pintype "passive"))
      (node (ref "U1001") (pin "3") (pinfunction "XTA_3") (pintype "passive"))
    )
    (net (code "97") (name "Net-(U1071-RF1)") (class "Default")
      (node (ref "C1067") (pin "1") (pinfunction "1_1") (pintype "passive"))
      (node (ref "L1064") (pin "1") (pinfunction "1_1") (pintype "passive"))
      (node (ref "U1071") (pin "1") (pinfunction "RF1_1") (pintype "passive"))
    )
    (net (code "98") (name "Net-(U1071-RF2)") (class "Default")
      (node (ref "C1092") (pin "2") (pinfunction "2_2") (pintype "passive"))
      (node (ref "C1093") (pin "2") (pinfunction "2_2") (pintype "passive"))
      (node (ref "U1071") (pin "3") (pinfunction "RF2_3") (pintype "passive"))
    )
    (net (code "99") (name "Net-(U1071-RFC)") (class "Default")
      (node (ref "C1081") (pin "1") (pinfunction "1_1") (pintype "passive"))
      (node (ref "U1071") (pin "5") (pinfunction "RFC_5") (pintype "passive"))
    )
    (net (code "100") (name "Net-(U1071-VDD_~{CTRL})") (class "Default")
      (node (ref "C1071") (pin "1") (pinfunction "1_1") (pintype "passive"))
      (node (ref "R1071") (pin "1") (pinfunction "1_1") (pintype "passive"))
      (node (ref "U1071") (pin "6") (pinfunction "VDD_~{CTRL}_6") (pintype "passive"))
    )
    (net (code "101") (name "Net-(U1111-~{INT})") (class "Default")
      (node (ref "R1111") (pin "2") (pinfunction "2_2") (pintype "passive"))
      (node (ref "U1111") (pin "1") (pinfunction "~{INT}_1") (pintype "output"))
    )
    (net (code "102") (name "Net-(U1111-~{RESET})") (class "Default")
      (node (ref "R1112") (pin "1") (pinfunction "1_1") (pintype "passive"))
      (node (ref "U1111") (pin "3") (pinfunction "~{RESET}_3") (pintype "input"))
    )
    (net (code "103") (name "Net-(U1311-SW)") (class "Default")
      (node (ref "L1311") (pin "2") (pinfunction "2_2") (pintype "passive"))
      (node (ref "U1311") (pin "2") (pinfunction "SW_2") (pintype "passive"))
    )
    (net (code "104") (name "Net-(U1411-SW)") (class "Default")
      (node (ref "L1411") (pin "2") (pinfunction "2_2") (pintype "passive"))
      (node (ref "U1411") (pin "1A") (pinfunction "SW_1A") (pintype "passive"))
    )
    (net (code "105") (name "PA0") (class "Default")
      (node (ref "C2032") (pin "1") (pinfunction "1_1") (pintype "passive"))
      (node (ref "S2031") (pin "1") (pinfunction "1_1") (pintype "passive"))
      (node (ref "U0101") (pin "14") (pinfunction "PA0_WKUP_14") (pintype "bidirectional"))
    )
    (net (code "106") (name "PA1") (class "Default")
      (node (ref "U0101") (pin "15") (pinfunction "PA1_15") (pintype "bidirectional"))
      (node (ref "X2153") (pin "8") (pinfunction "8_8") (pintype "passive"))
    )
    (net (code "107") (name "PA2") (class "Default")
      (node (ref "U0101") (pin "16") (pinfunction "PA2_WKUP_16") (pintype "bidirectional"))
      (node (ref "X2153") (pin "9") (pinfunction "9_9") (pintype "passive"))
    )
    (net (code "108") (name "PA4") (class "Default")
      (node (ref "C0461") (pin "1") (pinfunction "1_1") (pintype "passive"))
      (node (ref "R0461") (pin "2") (pinfunction "2_2") (pintype "passive"))
      (node (ref "R0462") (pin "1") (pinfunction "1_1") (pintype "passive"))
      (node (ref "U0101") (pin "20") (pinfunction "PA4_20") (pintype "bidirectional"))
    )
    (net (code "109") (name "PA5") (class "Default")
      (node (ref "U0101") (pin "21") (pinfunction "PA5_21") (pintype "bidirectional"))
      (node (ref "X2152") (pin "9") (pinfunction "9_9") (pintype "passive"))
    )
    (net (code "110") (name "PA6") (class "Default")
      (node (ref "U0101") (pin "22") (pinfunction "PA6_22") (pintype "bidirectional"))
      (node (ref "X2152") (pin "8") (pinfunction "8_8") (pintype "passive"))
      (node (ref "X2153") (pin "7") (pinfunction "7_7") (pintype "passive"))
    )
    (net (code "111") (name "PA7") (class "Default")
      (node (ref "U0101") (pin "23") (pinfunction "PA7_23") (pintype "bidirectional"))
      (node (ref "X2152") (pin "7") (pinfunction "7_7") (pintype "passive"))
    )
    (net (code "112") (name "PA8") (class "Default")
      (node (ref "U0101") (pin "41") (pinfunction "PA8_41") (pintype "bidirectional"))
      (node (ref "U1511") (pin "7") (pinfunction "7_7") (pintype "input"))
    )
    (net (code "113") (name "PA9") (class "Default")
      (node (ref "R0512") (pin "1") (pinfunction "1_1") (pintype "passive"))
      (node (ref "U0101") (pin "42") (pinfunction "PA9_42") (pintype "bidirectional"))
      (node (ref "U0611") (pin "6") (pinfunction "SCL_6") (pintype "input"))
      (node (ref "U0711") (pin "13") (pinfunction "SCLK_13") (pintype "input"))
      (node (ref "U0811") (pin "22") (pinfunction "SCL_22") (pintype "input"))
      (node (ref "U1111") (pin "22") (pinfunction "SCL_22") (pintype "input"))
      (node (ref "X2152") (pin "2") (pinfunction "2_2") (pintype "passive"))
    )
    (net (code "114") (name "PA10") (class "Default")
      (node (ref "R0511") (pin "1") (pinfunction "1_1") (pintype "passive"))
      (node (ref "U0101") (pin "43") (pinfunction "PA10_43") (pintype "bidirectional"))
      (node (ref "U0611") (pin "5") (pinfunction "SDA_5") (pintype "bidirectional"))
      (node (ref "U0711") (pin "14") (pinfunction "SDIO_14") (pintype "bidirectional"))
      (node (ref "U0811") (pin "23") (pinfunction "SDA_23") (pintype "bidirectional"))
      (node (ref "U1111") (pin "23") (pinfunction "SDA_23") (pintype "bidirectional"))
      (node (ref "X2152") (pin "1") (pinfunction "1_1") (pintype "passive"))
    )
    (net (code "115") (name "PA11") (class "Default")
      (node (ref "R1257") (pin "2") (pinfunction "2_2") (pintype "passive"))
      (node (ref "U0101") (pin "44") (pinfunction "PA11_44") (pintype "bidirectional"))
    )
    (net (code "116") (name "PA12") (class "Default")
      (node (ref "R1266") (pin "2") (pinfunction "2_2") (pintype "passive"))
      (node (ref "U0101") (pin "45") (pinfunction "PA12_45") (pintype "bidirectional"))
    )
    (net (code "117") (name "PA13") (class "Default")
      (node (ref "R0201") (pin "1") (pinfunction "1_1") (pintype "passive"))
      (node (ref "U0101") (pin "46") (pinfunction "PA13_JTMS_SWDIO_46") (pintype "bidirectional"))
      (node (ref "X0201") (pin "2") (pinfunction "2_2") (pintype "passive"))
    )
    (net (code "118") (name "PA14") (class "Default")
      (node (ref "R0202") (pin "2") (pinfunction "2_2") (pintype "passive"))
      (node (ref "U0101") (pin "49") (pinfunction "PA14_JTCK_SWCLK_49") (pintype "bidirectional"))
      (node (ref "X0201") (pin "4") (pinfunction "4_4") (pintype "passive"))
    )
    (net (code "119") (name "PB0") (class "Default")
      (node (ref "U0101") (pin "25") (pinfunction "PB0_25") (pintype "bidirectional"))
      (node (ref "U1801") (pin "7") (pinfunction "7_7") (pintype "input"))
    )
    (net (code "120") (name "PB1") (class "Default")
      (node (ref "U0101") (pin "26") (pinfunction "PB1_26") (pintype "bidirectional"))
      (node (ref "X2153") (pin "5") (pinfunction "5_5") (pintype "passive"))
    )
    (net (code "121") (name "PB5") (class "Default")
      (node (ref "U0101") (pin "56") (pinfunction "PB5_56") (pintype "bidirectional"))
      (node (ref "U1601") (pin "3") (pinfunction "3_3") (pintype "input"))
      (node (ref "U1601") (pin "7") (pinfunction "7_7") (pintype "input"))
    )
    (net (code "122") (name "PB6") (class "Default")
      (node (ref "R1271") (pin "2") (pinfunction "2_2") (pintype "passive"))
      (node (ref "U0101") (pin "57") (pinfunction "PB6_57") (pintype "bidirectional"))
    )
    (net (code "123") (name "PB7") (class "Default")
      (node (ref "R1272") (pin "2") (pinfunction "2_2") (pintype "passive"))
      (node (ref "U0101") (pin "58") (pinfunction "PB7_58") (pintype "bidirectional"))
    )
    (net (code "124") (name "PB8") (class "Default")
      (node (ref "C2021") (pin "1") (pinfunction "1_1") (pintype "passive"))
      (node (ref "R2021") (pin "2") (pinfunction "2_2") (pintype "passive"))
      (node (ref "U0101") (pin "60") (pinfunction "PB8_60") (pintype "bidirectional"))
    )
    (net (code "125") (name "PB10") (class "Default")
      (node (ref "U0101") (pin "28") (pinfunction "PB10_28") (pintype "bidirectional"))
      (node (ref "X2153") (pin "1") (pinfunction "1_1") (pintype "passive"))
    )
    (net (code "126") (name "PB11") (class "Default")
      (node (ref "U0101") (pin "29") (pinfunction "PB11_29") (pintype "bidirectional"))
      (node (ref "X2153") (pin "2") (pinfunction "2_2") (pintype "passive"))
    )
    (net (code "127") (name "PB12") (class "Default")
      (node (ref "U0101") (pin "33") (pinfunction "PB12_33") (pintype "bidirectional"))
      (node (ref "U1701") (pin "3") (pinfunction "3_3") (pintype "input"))
      (node (ref "U1701") (pin "7") (pinfunction "7_7") (pintype "input"))
    )
    (net (code "128") (name "PB13") (class "Default")
      (node (ref "U0101") (pin "34") (pinfunction "PB13_34") (pintype "bidirectional"))
      (node (ref "X2153") (pin "6") (pinfunction "6_6") (pintype "passive"))
    )
    (net (code "129") (name "PB14") (class "Default")
      (node (ref "U0101") (pin "35") (pinfunction "PB14_35") (pintype "bidirectional"))
      (node (ref "U1411") (pin "1B") (pinfunction "EN_1B") (pintype "input"))
    )
    (net (code "130") (name "PB15") (class "Default")
      (node (ref "U0101") (pin "36") (pinfunction "PB15_36") (pintype "bidirectional"))
      (node (ref "U1511") (pin "3") (pinfunction "3_3") (pintype "input"))
    )
    (net (code "131") (name "PC0") (class "Default")
      (node (ref "U0101") (pin "8") (pinfunction "PC0_8") (pintype "bidirectional"))
      (node (ref "X2153") (pin "4") (pinfunction "4_4") (pintype "passive"))
    )
    (net (code "132") (name "PC1") (class "Default")
      (node (ref "U0101") (pin "9") (pinfunction "PC1_9") (pintype "bidirectional"))
      (node (ref "X2153") (pin "3") (pinfunction "3_3") (pintype "passive"))
    )
    (net (code "133") (name "PC2") (class "Default")
      (node (ref "U0101") (pin "10") (pinfunction "PC2_10") (pintype "bidirectional"))
      (node (ref "X2152") (pin "3") (pinfunction "3_3") (pintype "passive"))
    )
    (net (code "134") (name "PC3") (class "Default")
      (node (ref "U0101") (pin "11") (pinfunction "PC3_11") (pintype "bidirectional"))
      (node (ref "X2152") (pin "4") (pinfunction "4_4") (pintype "passive"))
    )
    (net (code "135") (name "PC4") (class "Default")
      (node (ref "U0101") (pin "24") (pinfunction "PC4_24") (pintype "bidirectional"))
      (node (ref "U1801") (pin "3") (pinfunction "3_3") (pintype "input"))
      (node (ref "X2152") (pin "5") (pinfunction "5_5") (pintype "passive"))
    )
    (net (code "136") (name "PC7") (class "Default")
      (node (ref "R1111") (pin "1") (pinfunction "1_1") (pintype "passive"))
      (node (ref "U0101") (pin "38") (pinfunction "PC7_38") (pintype "bidirectional"))
    )
    (net (code "137") (name "PC8") (class "Default")
      (node (ref "R0811") (pin "1") (pinfunction "1_1") (pintype "passive"))
      (node (ref "U0101") (pin "39") (pinfunction "PC8_39") (pintype "bidirectional"))
    )
    (net (code "138") (name "PC9") (class "Default")
      (node (ref "R0731") (pin "1") (pinfunction "1_1") (pintype "passive"))
      (node (ref "U0101") (pin "40") (pinfunction "PC9_40") (pintype "bidirectional"))
    )
    (net (code "139") (name "PC10") (class "Default")
      (node (ref "U0101") (pin "51") (pinfunction "PC10_51") (pintype "bidirectional"))
      (node (ref "U0911") (pin "19") (pinfunction "H_SCL/SCL/RX_19") (pintype "bidirectional"))
      (node (ref "U1001") (pin "18") (pinfunction "SCLK_18") (pintype "input"))
    )
    (net (code "140") (name "PC11") (class "Default")
      (node (ref "R0901") (pin "1") (pinfunction "1_1") (pintype "passive"))
      (node (ref "R1024") (pin "1") (pinfunction "1_1") (pintype "passive"))
      (node (ref "U0101") (pin "52") (pinfunction "PC11_52") (pintype "bidirectional"))
    )
    (net (code "141") (name "PC12") (class "Default")
      (node (ref "U0101") (pin "53") (pinfunction "PC12_53") (pintype "bidirectional"))
      (node (ref "U0911") (pin "17") (pinfunction "SA0/H_MOSI_17") (pintype "input"))
      (node (ref "U1001") (pin "17") (pinfunction "MOSI_17") (pintype "input"))
    )
    (net (code "142") (name "PC13") (class "Default")
      (node (ref "D0901") (pin "C") (pinfunction "C_C") (pintype "passive"))
      (node (ref "U0101") (pin "2") (pinfunction "PC13_WKUP_2") (pintype "bidirectional"))
      (node (ref "X2152") (pin "6") (pinfunction "6_6") (pintype "passive"))
    )
    (net (code "143") (name "PC14_OSC32_IN") (class "Default")
      (node (ref "C0331") (pin "-") (pinfunction "E_-") (pintype "passive"))
      (node (ref "C0332") (pin "1") (pinfunction "1_1") (pintype "passive"))
      (node (ref "Q0321") (pin "2") (pinfunction "2_2") (pintype "passive"))
      (node (ref "U0101") (pin "3") (pinfunction "PC14_OSC32_IN_3") (pintype "bidirectional"))
    )
    (net (code "144") (name "PC15_OSC32_OUT") (class "Default")
      (node (ref "C0311") (pin "1") (pinfunction "1_1") (pintype "passive"))
      (node (ref "Q0321") (pin "1") (pinfunction "1_1") (pintype "passive"))
      (node (ref "U0101") (pin "4") (pinfunction "PC15_OSC32_OUT_4") (pintype "bidirectional"))
    )
    (net (code "145") (name "PEXPA_P0_0_R") (class "Default")
      (node (ref "U0811") (pin "4") (pinfunction "P0_0_4") (pintype "bidirectional"))
      (node (ref "U0911") (pin "11") (pinfunction "NRST_11") (pintype "input"))
    )
    (net (code "146") (name "PEXPA_P0_1_R") (class "Default")
      (node (ref "R0904") (pin "1") (pinfunction "1_1") (pintype "passive"))
      (node (ref "U0811") (pin "5") (pinfunction "P0_1_5") (pintype "bidirectional"))
    )
    (net (code "147") (name "PEXPA_P0_2_R") (class "Default")
      (node (ref "U0811") (pin "6") (pinfunction "P0_2_6") (pintype "bidirectional"))
      (node (ref "U0911") (pin "4") (pinfunction "BOOTN_4") (pintype "input"))
    )
    (net (code "148") (name "PEXPA_P0_3_R") (class "Default")
      (node (ref "R0902") (pin "1") (pinfunction "1_1") (pintype "passive"))
      (node (ref "U0811") (pin "7") (pinfunction "P0_3_7") (pintype "bidirectional"))
    )
    (net (code "149") (name "PEXPA_P0_4_R") (class "Default")
      (node (ref "U0811") (pin "8") (pinfunction "P0_4_8") (pintype "bidirectional"))
    )
    (net (code "150") (name "PEXPA_P0_5_R") (class "Default")
      (node (ref "U0811") (pin "9") (pinfunction "P0_5_9") (pintype "bidirectional"))
    )
    (net (code "151") (name "PEXPA_P0_6_R") (class "Default")
      (node (ref "U0811") (pin "10") (pinfunction "P0_6_10") (pintype "bidirectional"))
    )
    (net (code "152") (name "PEXPA_P0_7_R") (class "Default")
      (node (ref "U0811") (pin "11") (pinfunction "P0_7_11") (pintype "bidirectional"))
    )
    (net (code "153") (name "PEXPA_P1_0_R") (class "Default")
      (node (ref "U0811") (pin "13") (pinfunction "P1_0_13") (pintype "bidirectional"))
      (node (ref "U1001") (pin "15") (pinfunction "NRESET_15") (pintype "bidirectional"))
    )
    (net (code "154") (name "PEXPA_P1_1_R") (class "Default")
      (node (ref "R1021") (pin "1") (pinfunction "1_1") (pintype "passive"))
      (node (ref "U0811") (pin "14") (pinfunction "P1_1_14") (pintype "bidirectional"))
    )
    (net (code "155") (name "PEXPA_P1_2_R") (class "Default")
      (node (ref "R1011") (pin "1") (pinfunction "1_1") (pintype "passive"))
      (node (ref "U0811") (pin "15") (pinfunction "P1_2_15") (pintype "bidirectional"))
    )
    (net (code "156") (name "PEXPA_P1_3_R") (class "Default")
      (node (ref "R1053") (pin "2") (pinfunction "2_2") (pintype "passive"))
      (node (ref "U0811") (pin "16") (pinfunction "P1_3_16") (pintype "bidirectional"))
    )
    (net (code "157") (name "PEXPA_P1_4_R") (class "Default")
      (node (ref "C1072") (pin "1") (pinfunction "1_1") (pintype "passive"))
      (node (ref "R1052") (pin "2") (pinfunction "2_2") (pintype "passive"))
      (node (ref "U0811") (pin "17") (pinfunction "P1_4_17") (pintype "bidirectional"))
      (node (ref "U1071") (pin "4") (pinfunction "CTRL_4") (pintype "input"))
    )
    (net (code "158") (name "PEXPA_P1_5_R") (class "Default")
      (node (ref "R1051") (pin "2") (pinfunction "2_2") (pintype "passive"))
      (node (ref "U0811") (pin "18") (pinfunction "P1_5_18") (pintype "bidirectional"))
    )
    (net (code "159") (name "PEXPA_P1_6_R") (class "Default")
      (node (ref "U0811") (pin "19") (pinfunction "P1_6_19") (pintype "bidirectional"))
      (node (ref "X2151") (pin "7") (pinfunction "7_7") (pintype "passive"))
    )
    (net (code "160") (name "PEXPA_P1_7_R") (class "Default")
      (node (ref "U0811") (pin "20") (pinfunction "P1_7_20") (pintype "bidirectional"))
      (node (ref "X2151") (pin "8") (pinfunction "8_8") (pintype "passive"))
    )
    (net (code "161") (name "PEXPB_P0_0_R") (class "Default")
      (node (ref "U1111") (pin "4") (pinfunction "P0_0_4") (pintype "bidirectional"))
    )
    (net (code "162") (name "PEXPB_P0_1_R") (class "Default")
      (node (ref "U1111") (pin "5") (pinfunction "P0_1_5") (pintype "bidirectional"))
      (node (ref "U1211") (pin "1") (pinfunction "RST_1") (pintype "input"))
    )
    (net (code "163") (name "PEXPB_P0_2_R") (class "Default")
      (node (ref "U1111") (pin "6") (pinfunction "P0_2_6") (pintype "bidirectional"))
      (node (ref "U1211") (pin "3") (pinfunction "EN_3") (pintype "input"))
    )
    (net (code "164") (name "PEXPB_P0_3_R") (class "Default")
      (node (ref "U1111") (pin "7") (pinfunction "P0_3_7") (pintype "bidirectional"))
      (node (ref "U1211") (pin "4") (pinfunction "GPIO16_WKUP_4") (pintype "bidirectional"))
    )
    (net (code "165") (name "PEXPB_P0_4_R") (class "Default")
      (node (ref "U1111") (pin "8") (pinfunction "P0_4_8") (pintype "bidirectional"))
      (node (ref "U1211") (pin "5") (pinfunction "GPIO14_5") (pintype "bidirectional"))
    )
    (net (code "166") (name "PEXPB_P0_5_R") (class "Default")
      (node (ref "U1111") (pin "9") (pinfunction "P0_5_9") (pintype "bidirectional"))
      (node (ref "U1211") (pin "6") (pinfunction "GPIO12_6") (pintype "bidirectional"))
    )
    (net (code "167") (name "PEXPB_P0_6_R") (class "Default")
      (node (ref "U1111") (pin "10") (pinfunction "P0_6_10") (pintype "bidirectional"))
      (node (ref "U1211") (pin "9") (pinfunction "CS0_9") (pintype "input"))
    )
    (net (code "168") (name "PEXPB_P0_7_R") (class "Default")
      (node (ref "U1111") (pin "11") (pinfunction "P0_7_11") (pintype "bidirectional"))
      (node (ref "U1211") (pin "10") (pinfunction "MISO_10") (pintype "bidirectional"))
    )
    (net (code "169") (name "PEXPB_P1_0_R") (class "Default")
      (node (ref "U1111") (pin "13") (pinfunction "P1_0_13") (pintype "bidirectional"))
      (node (ref "U1211") (pin "11") (pinfunction "GPIO9_11") (pintype "bidirectional"))
    )
    (net (code "170") (name "PEXPB_P1_1_R") (class "Default")
      (node (ref "U1111") (pin "14") (pinfunction "P1_1_14") (pintype "bidirectional"))
      (node (ref "U1211") (pin "12") (pinfunction "GPIO10_12") (pintype "bidirectional"))
    )
    (net (code "171") (name "PEXPB_P1_2_R") (class "Default")
      (node (ref "U1111") (pin "15") (pinfunction "P1_2_15") (pintype "bidirectional"))
      (node (ref "U1211") (pin "13") (pinfunction "MOSI_13") (pintype "bidirectional"))
    )
    (net (code "172") (name "PEXPB_P1_3_R") (class "Default")
      (node (ref "U1111") (pin "16") (pinfunction "P1_3_16") (pintype "bidirectional"))
      (node (ref "U1211") (pin "14") (pinfunction "SCLK_14") (pintype "bidirectional"))
    )
    (net (code "173") (name "PEXPB_P1_4_R") (class "Default")
      (node (ref "U1111") (pin "17") (pinfunction "P1_4_17") (pintype "bidirectional"))
      (node (ref "U1211") (pin "17") (pinfunction "GPIO2_17") (pintype "bidirectional"))
    )
    (net (code "174") (name "PEXPB_P1_5_R") (class "Default")
      (node (ref "U1111") (pin "18") (pinfunction "P1_5_18") (pintype "bidirectional"))
      (node (ref "U1211") (pin "18") (pinfunction "GPIO0_18") (pintype "bidirectional"))
    )
    (net (code "175") (name "PEXPB_P1_6_R") (class "Default")
      (node (ref "U1111") (pin "19") (pinfunction "P1_6_19") (pintype "bidirectional"))
      (node (ref "U1211") (pin "19") (pinfunction "GPIO4_19") (pintype "bidirectional"))
    )
    (net (code "176") (name "PEXPB_P1_7_R") (class "Default")
      (node (ref "U1111") (pin "20") (pinfunction "P1_7_20") (pintype "bidirectional"))
      (node (ref "U1211") (pin "20") (pinfunction "GPIO5_20") (pintype "bidirectional"))
    )
    (net (code "177") (name "PH0") (class "Default")
      (node (ref "R1990") (pin "1") (pinfunction "1_1") (pintype "passive"))
      (node (ref "U0101") (pin "5") (pinfunction "PH0_OSC_IN_5") (pintype "bidirectional"))
    )
    (net (code "178") (name "PH1") (class "Default")
      (node (ref "R1991") (pin "1") (pinfunction "1_1") (pintype "passive"))
      (node (ref "U0101") (pin "6") (pinfunction "PH1_OSC_OUT_6") (pintype "bidirectional"))
    )
    (net (code "179") (name "PH3_BOOT0") (class "Default")
      (node (ref "R0221") (pin "2") (pinfunction "2_2") (pintype "passive"))
      (node (ref "U0101") (pin "59") (pinfunction "BOOT0_59") (pintype "output"))
      (node (ref "X0222") (pin "2") (pinfunction "2_2") (pintype "passive"))
    )
    (net (code "180") (name "VBAT") (class "Default")
      (node (ref "L2011") (pin "2") (pinfunction "2_2") (pintype "passive"))
      (node (ref "VIN+") (pin "1") (pinfunction "P_1") (pintype "passive"))
    )
    (net (code "181") (name "VBAT_L") (class "Default")
      (node (ref "C1301") (pin "1") (pinfunction "1_1") (pintype "passive"))
      (node (ref "C1801") (pin "1") (pinfunction "1_1") (pintype "passive"))
      (node (ref "C2011") (pin "1") (pinfunction "1_1") (pintype "passive"))
      (node (ref "L2011") (pin "1") (pinfunction "1_1") (pintype "passive"))
      (node (ref "U1311") (pin "1") (pinfunction "VIN_1") (pintype "power_in"))
      (node (ref "U1311") (pin "10") (pinfunction "VSEL2_10") (pintype "input"))
      (node (ref "U1311") (pin "11") (pinfunction "VSEL1_11") (pintype "input"))
      (node (ref "U1311") (pin "12") (pinfunction "EN_12") (pintype "input"))
      (node (ref "U1311") (pin "8") (pinfunction "VSEL4_8") (pintype "input"))
      (node (ref "U1311") (pin "9") (pinfunction "VSEL3_9") (pintype "input"))
      (node (ref "U1801") (pin "1") (pinfunction "1_1") (pintype "passive"))
      (node (ref "U1801") (pin "8") (pinfunction "8_8") (pintype "power_in"))
      (node (ref "X2151") (pin "1") (pinfunction "1_1") (pintype "passive"))
    )
    (net (code "182") (name "VDDUSB") (class "Default")
      (node (ref "R0421") (pin "2") (pinfunction "2_2") (pintype "passive"))
      (node (ref "U0101") (pin "48") (pinfunction "VDDUSB_48") (pintype "power_in"))
    )
    (net (code "183") (name "VREF_3V000") (class "Default")
      (node (ref "C0752") (pin "1") (pinfunction "1_1") (pintype "passive"))
      (node (ref "U0711") (pin "1") (pinfunction "REFP_1") (pintype "passive"))
      (node (ref "U0751") (pin "5") (pinfunction "OUT_5") (pintype "power_in"))
    )
    (net (code "184") (name "unconnected-(U0101-PA3-Pad17)") (class "Default")
      (node (ref "U0101") (pin "17") (pinfunction "PA3_17") (pintype "bidirectional"))
    )
    (net (code "185") (name "unconnected-(U0101-PA15_JTDI-Pad50)") (class "Default")
      (node (ref "U0101") (pin "50") (pinfunction "PA15_JTDI_50") (pintype "bidirectional"))
    )
    (net (code "186") (name "unconnected-(U0101-PB2-Pad27)") (class "Default")
      (node (ref "U0101") (pin "27") (pinfunction "PB2_27") (pintype "bidirectional"))
    )
    (net (code "187") (name "unconnected-(U0101-PB3_JTDO_TRACESWO-Pad54)") (class "Default")
      (node (ref "U0101") (pin "54") (pinfunction "PB3_JTDO_TRACESWO_54") (pintype "bidirectional"))
    )
    (net (code "188") (name "unconnected-(U0101-PB4_NJTRST-Pad55)") (class "Default")
      (node (ref "U0101") (pin "55") (pinfunction "PB4_NJTRST_55") (pintype "bidirectional"))
    )
    (net (code "189") (name "unconnected-(U0101-PB9-Pad61)") (class "Default")
      (node (ref "U0101") (pin "61") (pinfunction "PB9_61") (pintype "bidirectional"))
    )
    (net (code "190") (name "unconnected-(U0101-PC6-Pad37)") (class "Default")
      (node (ref "U0101") (pin "37") (pinfunction "PC6_37") (pintype "bidirectional"))
    )
    (net (code "191") (name "unconnected-(U0711-XIN-Pad10)") (class "Default")
      (node (ref "U0711") (pin "10") (pinfunction "XIN_10") (pintype "passive"))
    )
    (net (code "192") (name "unconnected-(U0711-XOUT-Pad11)") (class "Default")
      (node (ref "U0711") (pin "11") (pinfunction "XOUT_11") (pintype "output"))
    )
    (net (code "193") (name "unconnected-(U0751-NC-Pad3)") (class "Default")
      (node (ref "U0751") (pin "3") (pinfunction "NC_3") (pintype "no_connect"))
    )
    (net (code "194") (name "unconnected-(U0751-NC-Pad4)") (class "Default")
      (node (ref "U0751") (pin "4") (pinfunction "NC_4") (pintype "no_connect"))
    )
    (net (code "195") (name "unconnected-(U0911-RESV_NC-Pad1)") (class "Default")
      (node (ref "U0911") (pin "1") (pinfunction "RESV_NC_1") (pintype "no_connect"))
    )
    (net (code "196") (name "unconnected-(U0911-RESV_NC-Pad7)") (class "Default")
      (node (ref "U0911") (pin "7") (pinfunction "RESV_NC_7") (pintype "no_connect"))
    )
    (net (code "197") (name "unconnected-(U0911-RESV_NC-Pad8)") (class "Default")
      (node (ref "U0911") (pin "8") (pinfunction "RESV_NC_8") (pintype "no_connect"))
    )
    (net (code "198") (name "unconnected-(U0911-RESV_NC-Pad12)") (class "Default")
      (node (ref "U0911") (pin "12") (pinfunction "RESV_NC_12") (pintype "no_connect"))
    )
    (net (code "199") (name "unconnected-(U0911-RESV_NC-Pad13)") (class "Default")
      (node (ref "U0911") (pin "13") (pinfunction "RESV_NC_13") (pintype "no_connect"))
    )
    (net (code "200") (name "unconnected-(U0911-RESV_NC-Pad21)") (class "Default")
      (node (ref "U0911") (pin "21") (pinfunction "RESV_NC_21") (pintype "no_connect"))
    )
    (net (code "201") (name "unconnected-(U0911-RESV_NC-Pad22)") (class "Default")
      (node (ref "U0911") (pin "22") (pinfunction "RESV_NC_22") (pintype "no_connect"))
    )
    (net (code "202") (name "unconnected-(U0911-RESV_NC-Pad23)") (class "Default")
      (node (ref "U0911") (pin "23") (pinfunction "RESV_NC_23") (pintype "no_connect"))
    )
    (net (code "203") (name "unconnected-(U0911-RESV_NC-Pad24)") (class "Default")
      (node (ref "U0911") (pin "24") (pinfunction "RESV_NC_24") (pintype "no_connect"))
    )
    (net (code "204") (name "unconnected-(U1311-PG-Pad7)") (class "Default")
      (node (ref "U1311") (pin "7") (pinfunction "PG_7") (pintype "open_collector"))
    )
    (net (code "205") (name "unconnected-(U1311-VIN_SW-Pad6)") (class "Default")
      (node (ref "U1311") (pin "6") (pinfunction "VIN_SW_6") (pintype "passive"))
    )
    (net (code "206") (name "unconnected-(X0201-Pad6)") (class "Default")
      (node (ref "X0201") (pin "6") (pinfunction "6_6") (pintype "passive"))
    )
    (net (code "207") (name "unconnected-(X0201-Pad7)") (class "Default")
      (node (ref "X0201") (pin "7") (pinfunction "7_7") (pintype "passive"))
    )
    (net (code "208") (name "unconnected-(X0201-Pad8)") (class "Default")
      (node (ref "X0201") (pin "8") (pinfunction "8_8") (pintype "passive"))
    )
  )
)
